# 10MHzRefOsc_3V0.net
KiCad netlist of a schematic drawn in EAGLE
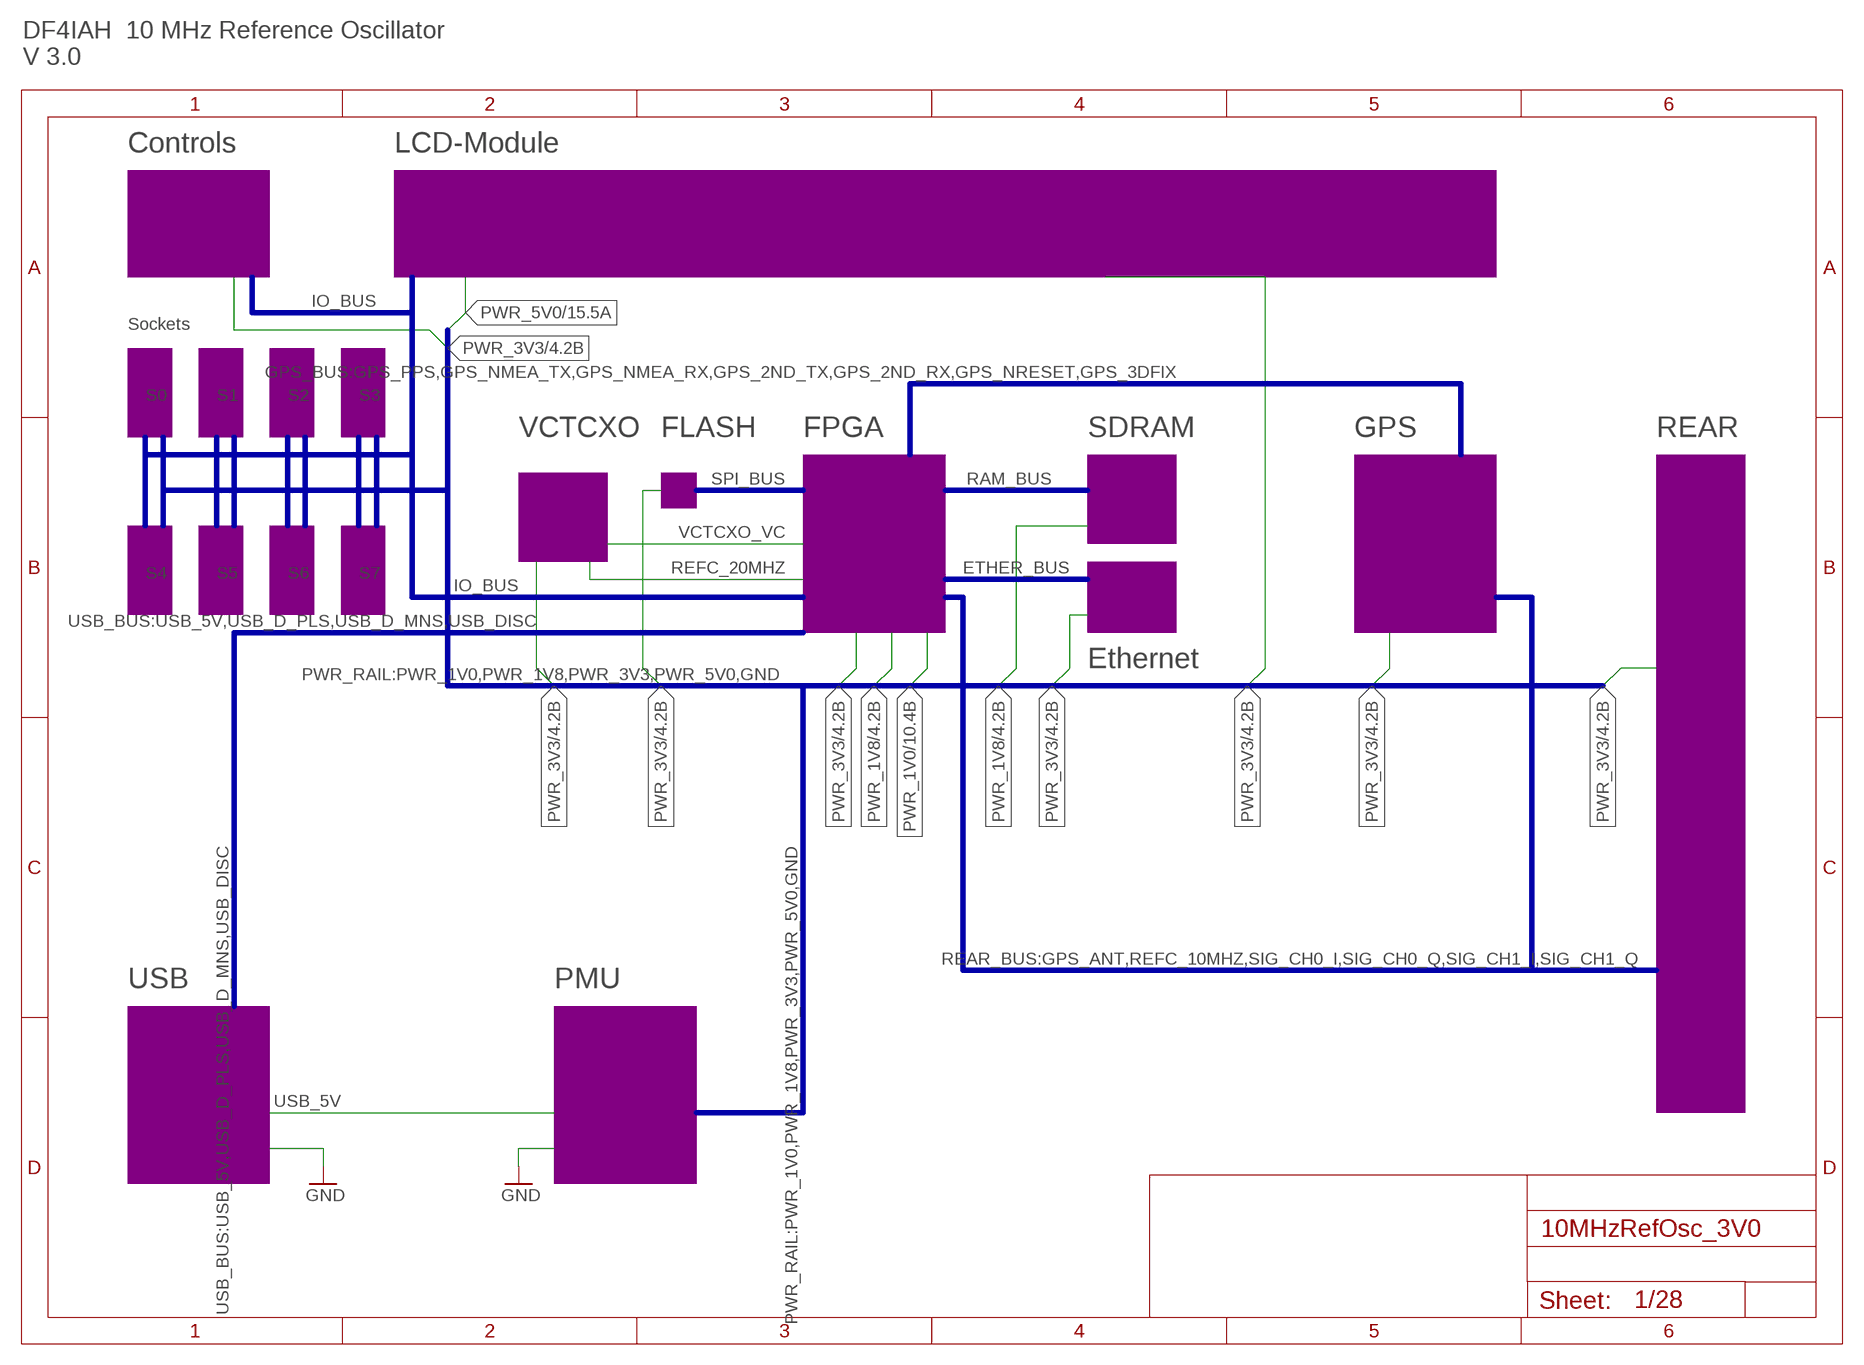
[diagram p0: schematic, sheet 1]
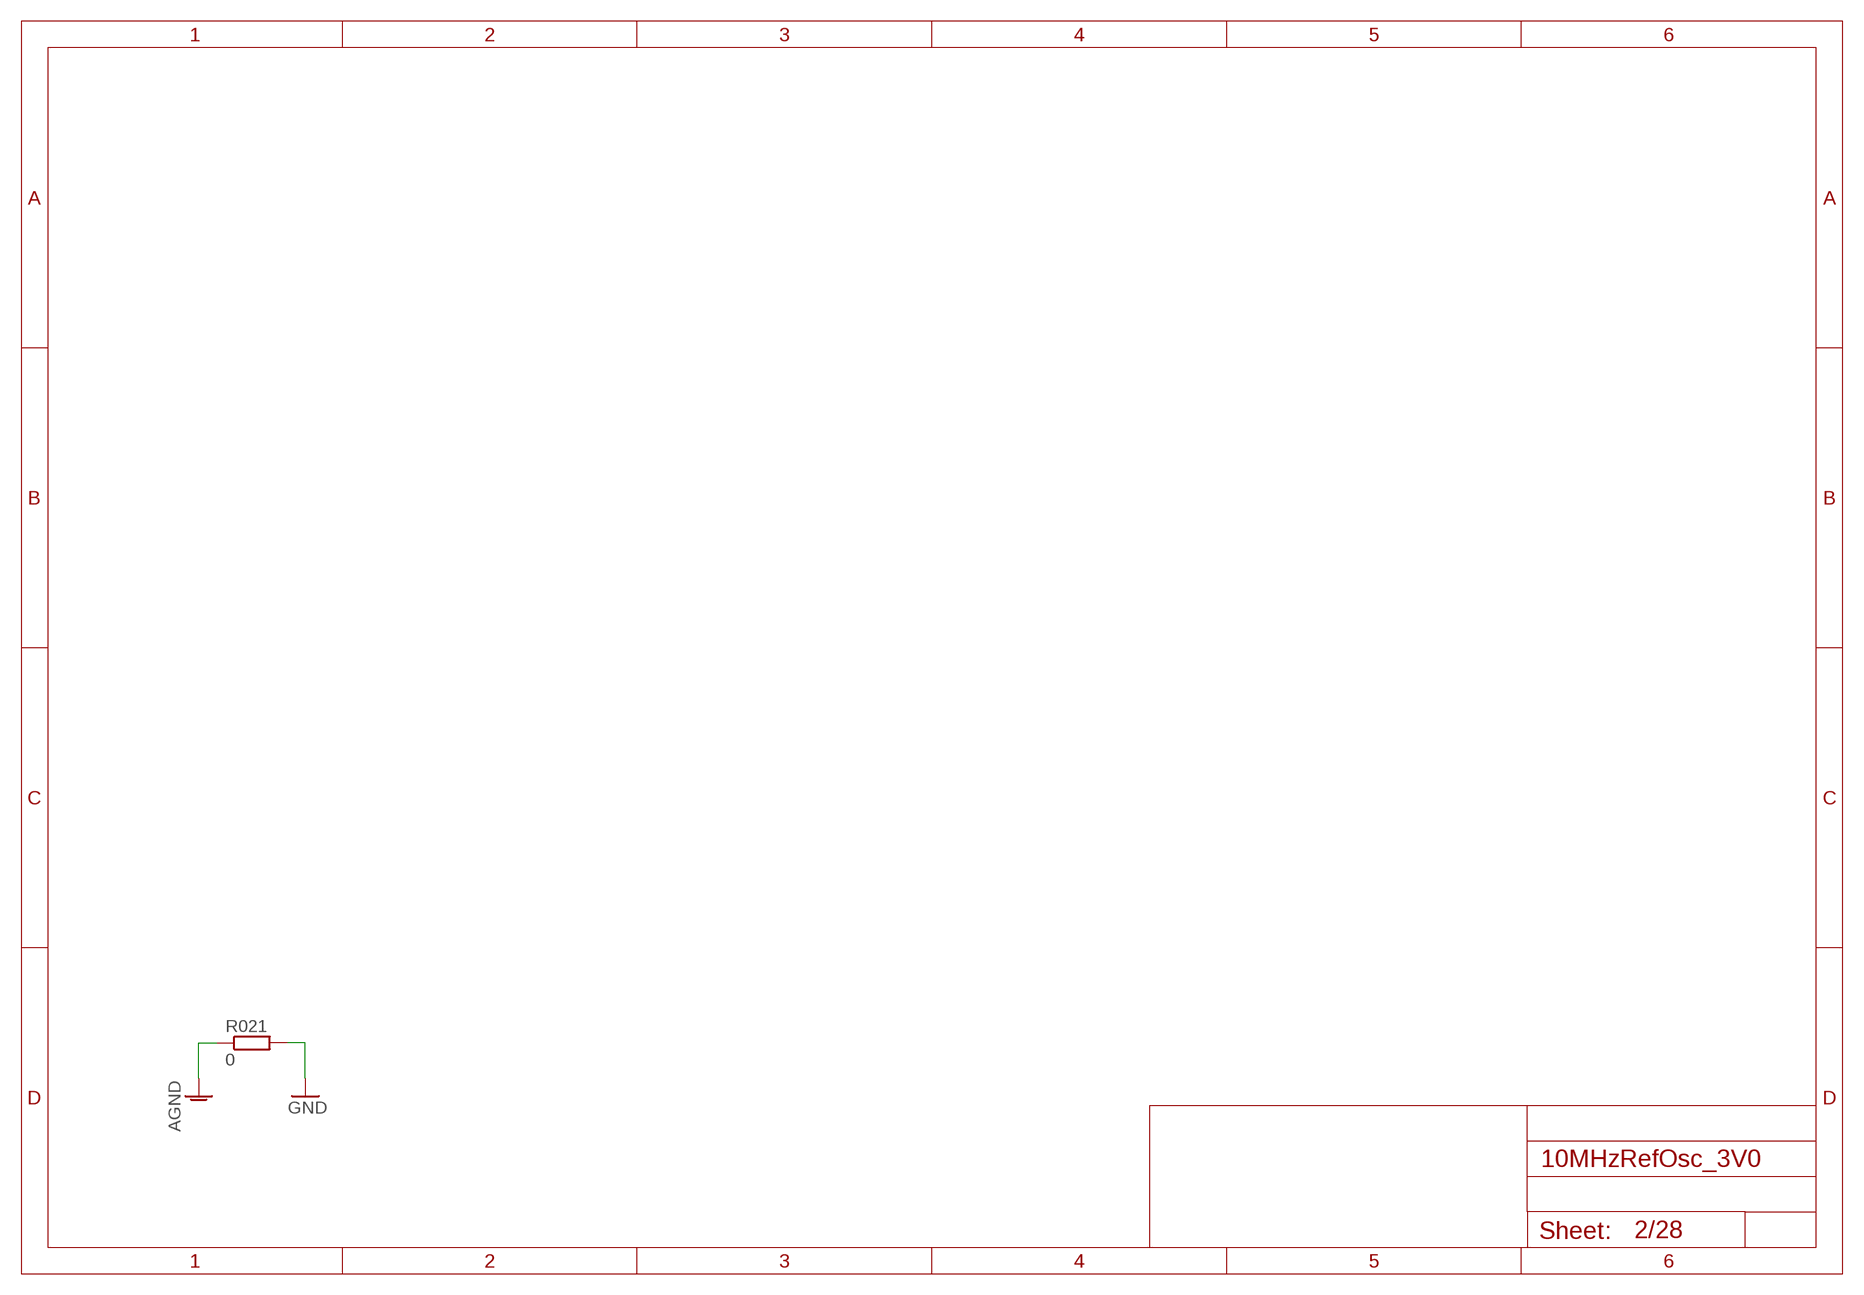
[diagram p1: schematic, sheet 2]
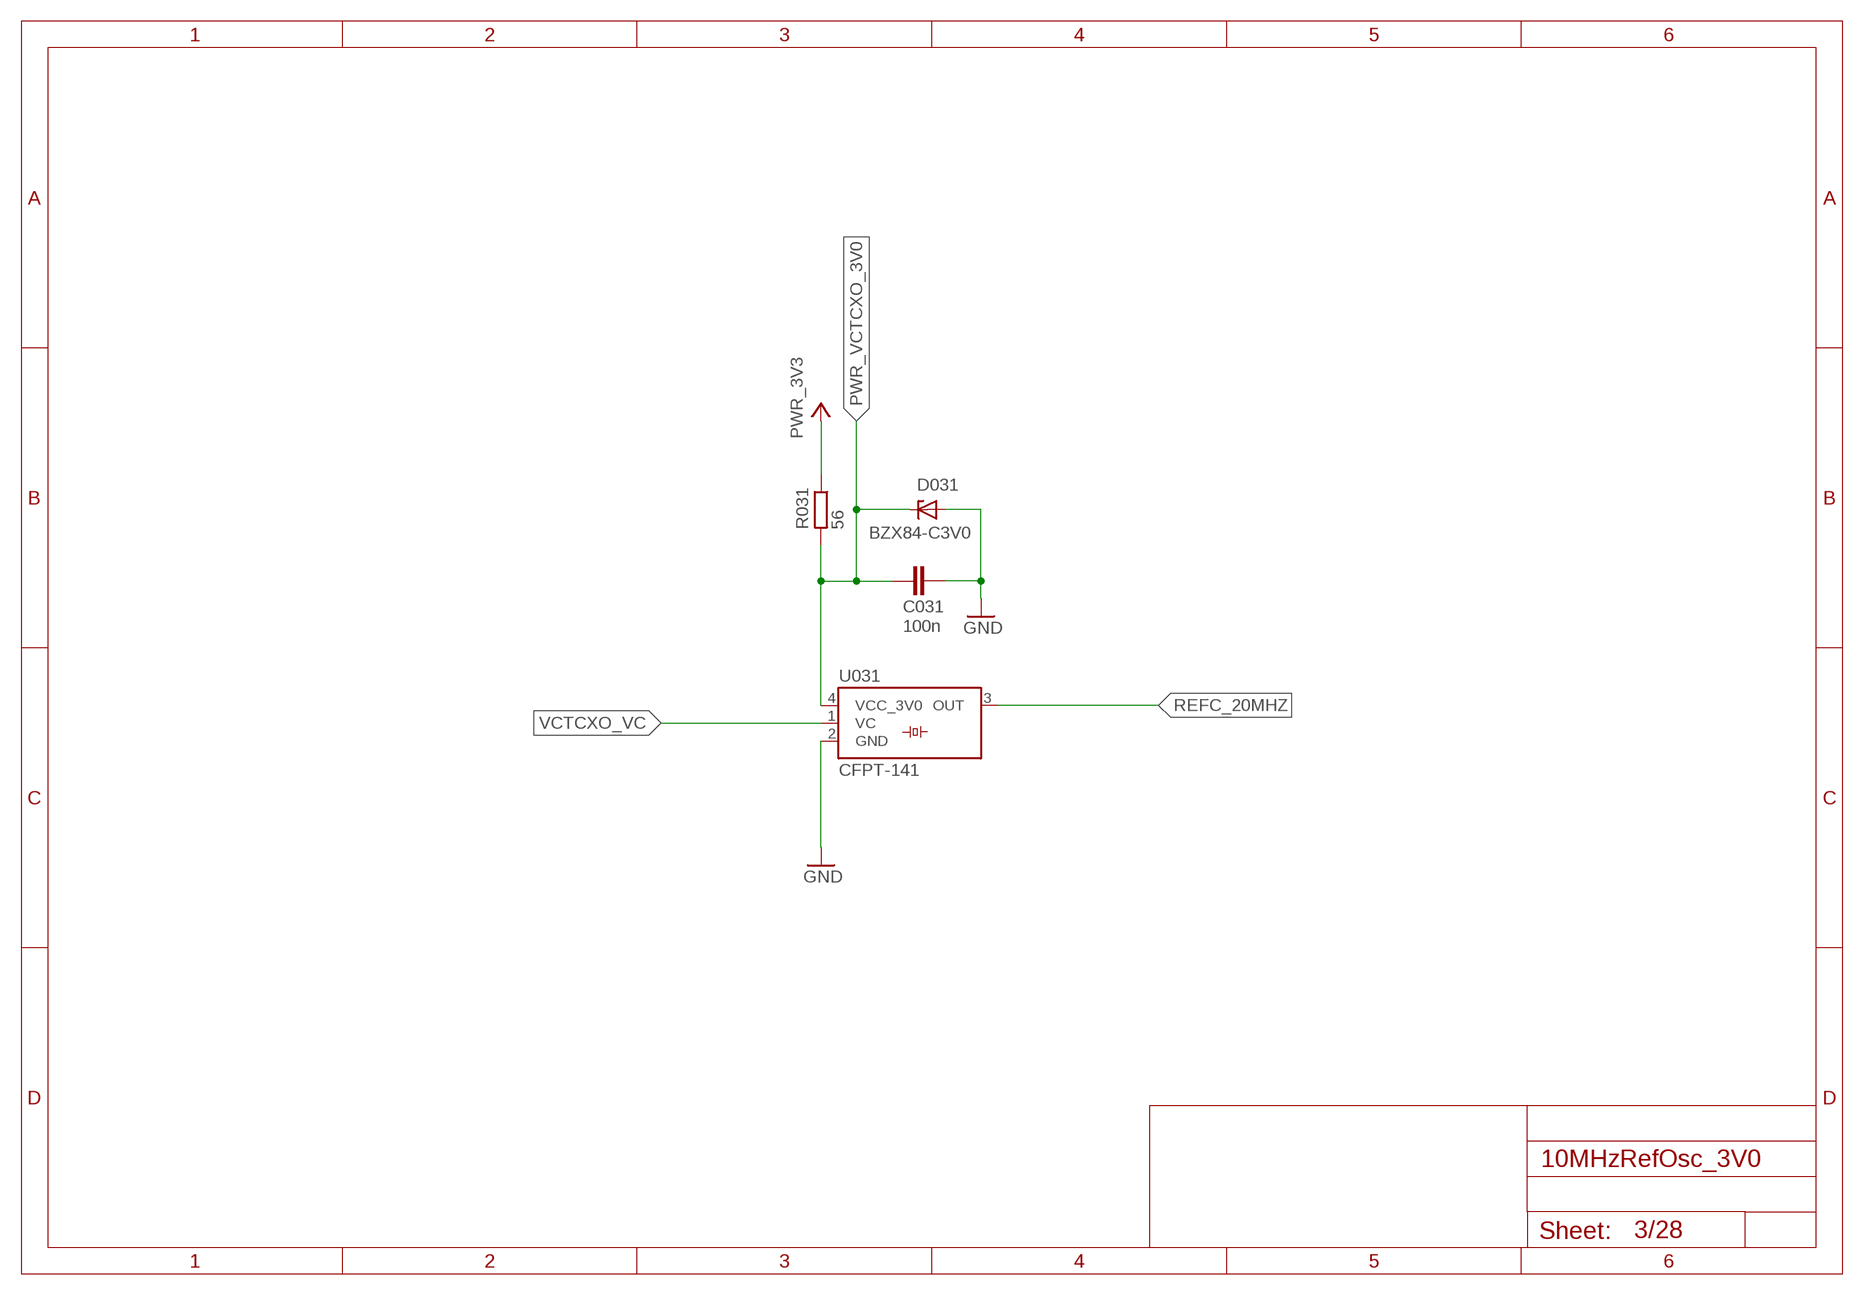
[diagram p2: schematic, sheet 3]
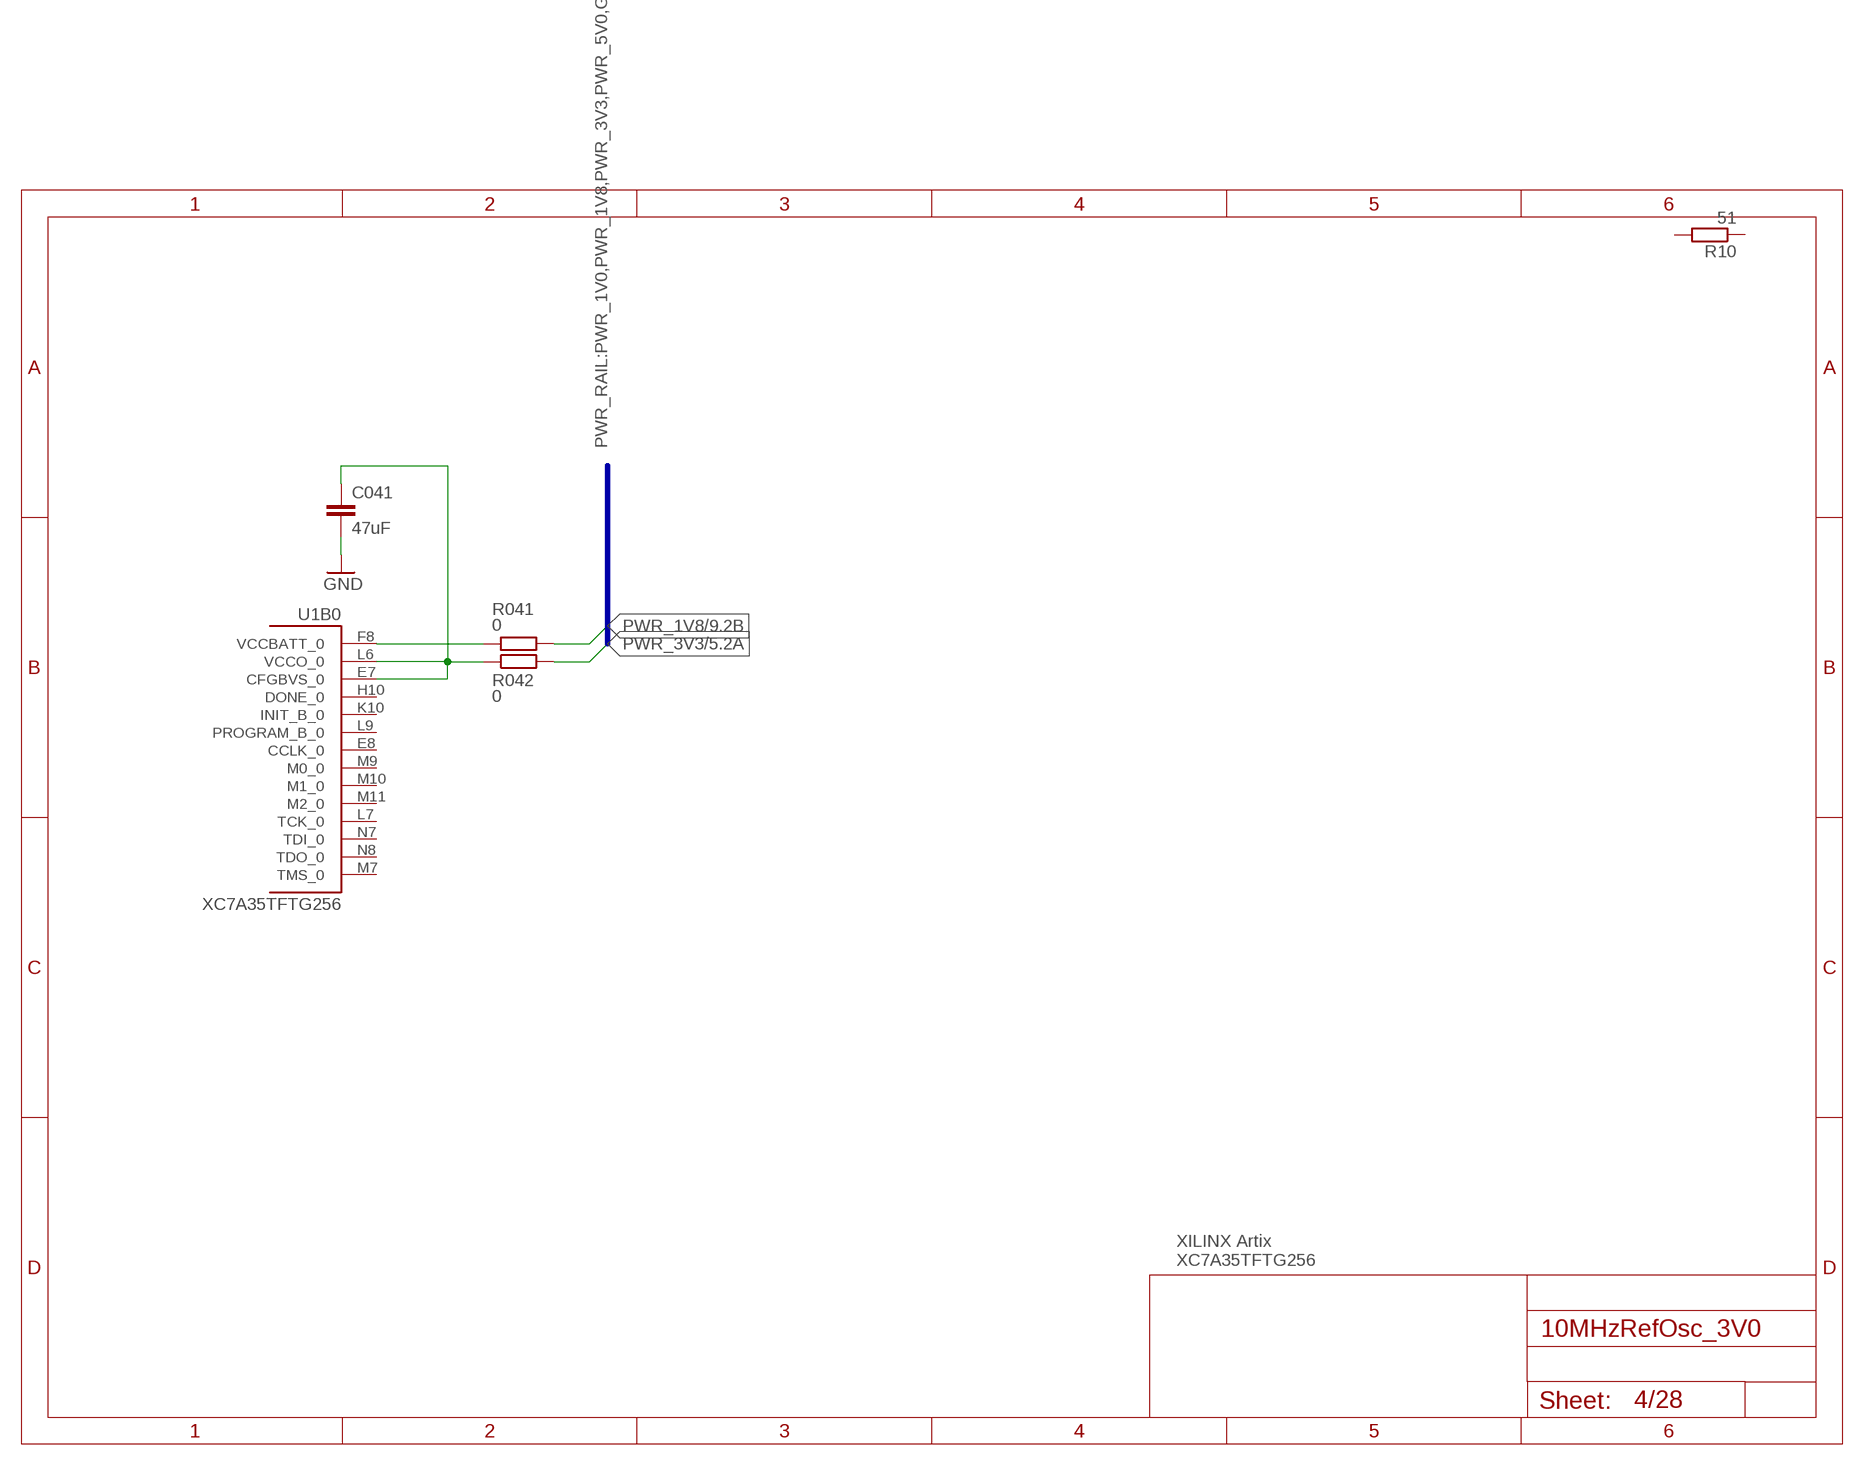
[diagram p3: schematic, sheet 4]
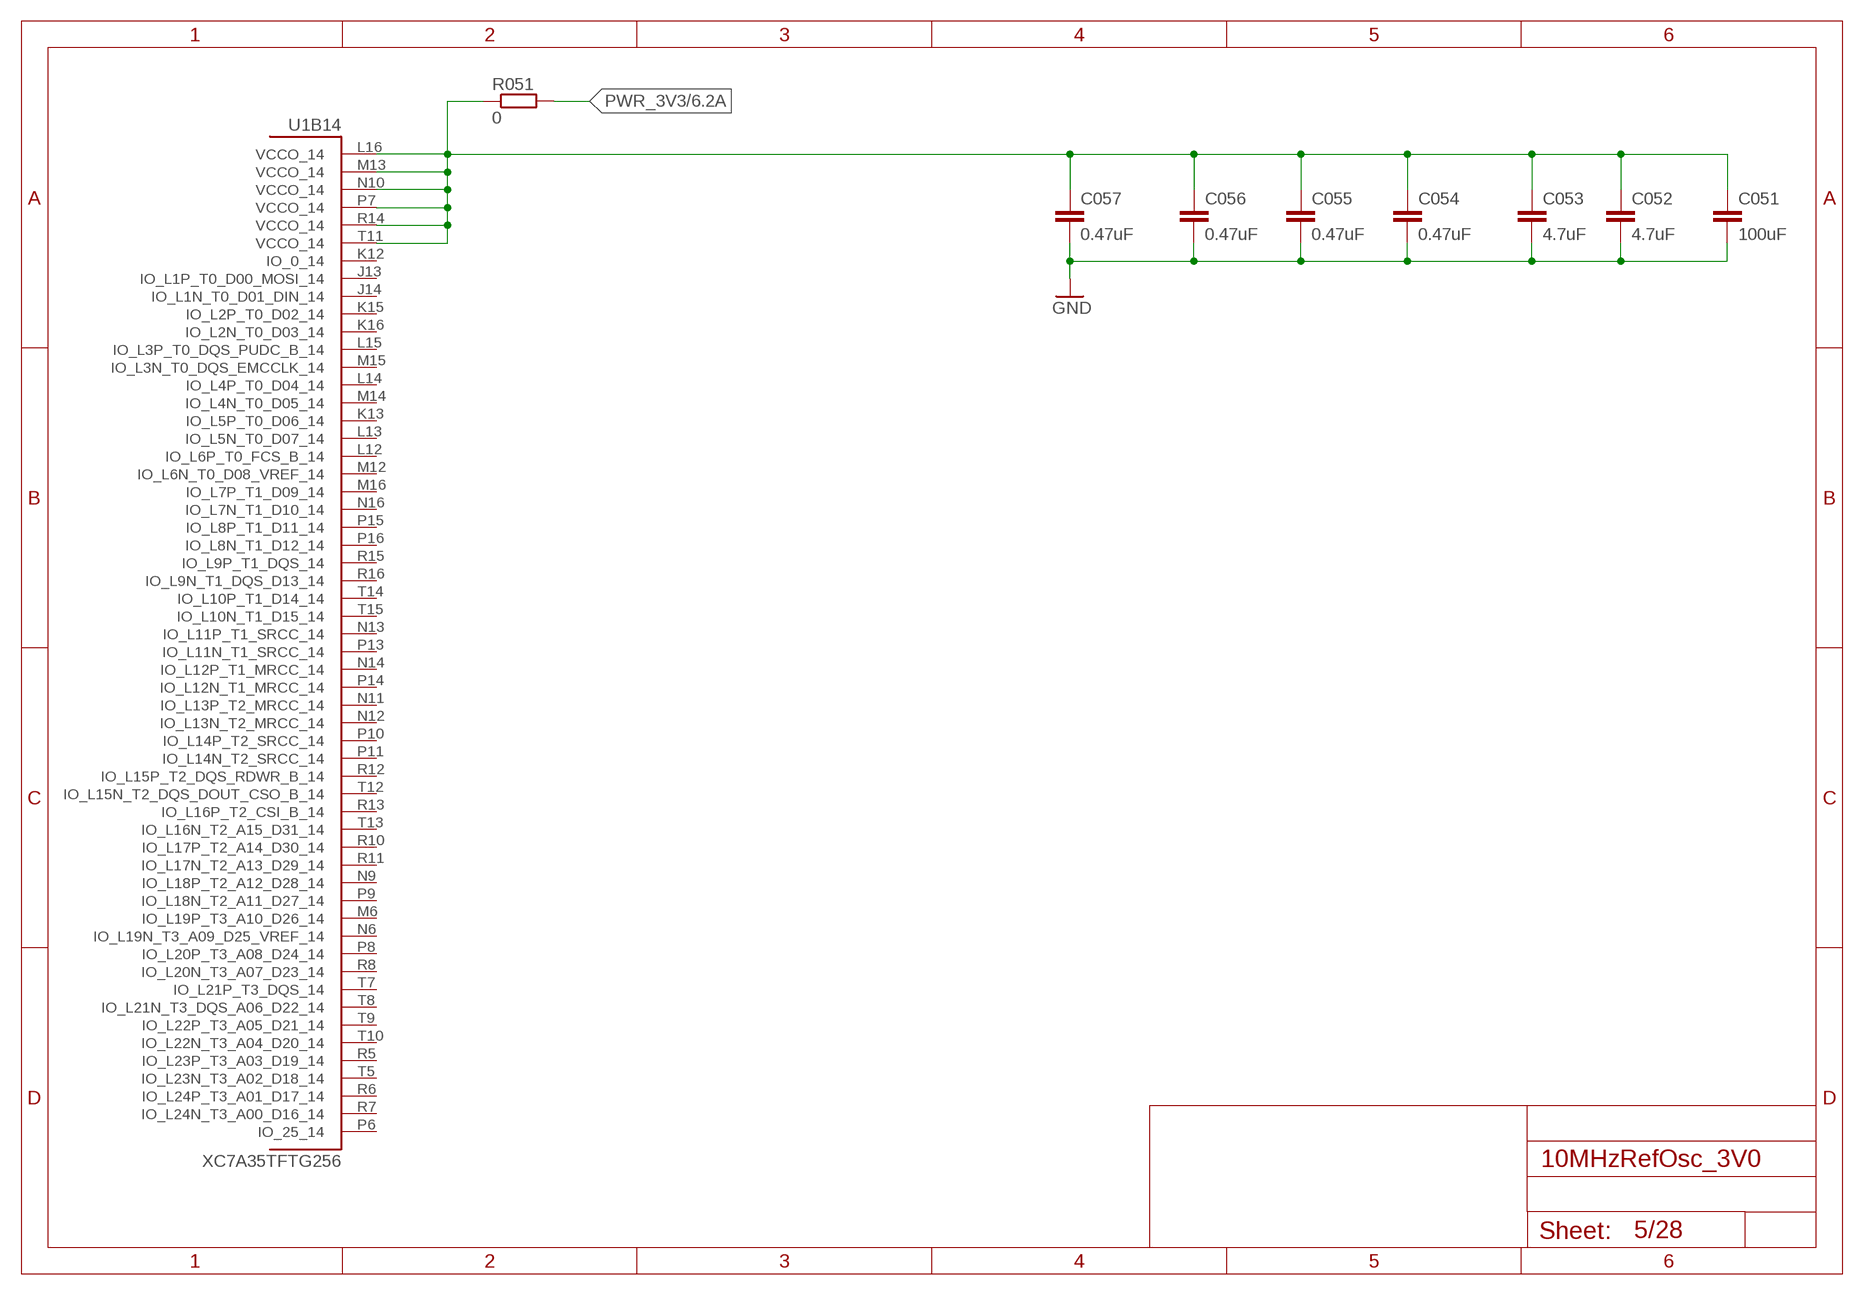
[diagram p4: schematic, sheet 5]
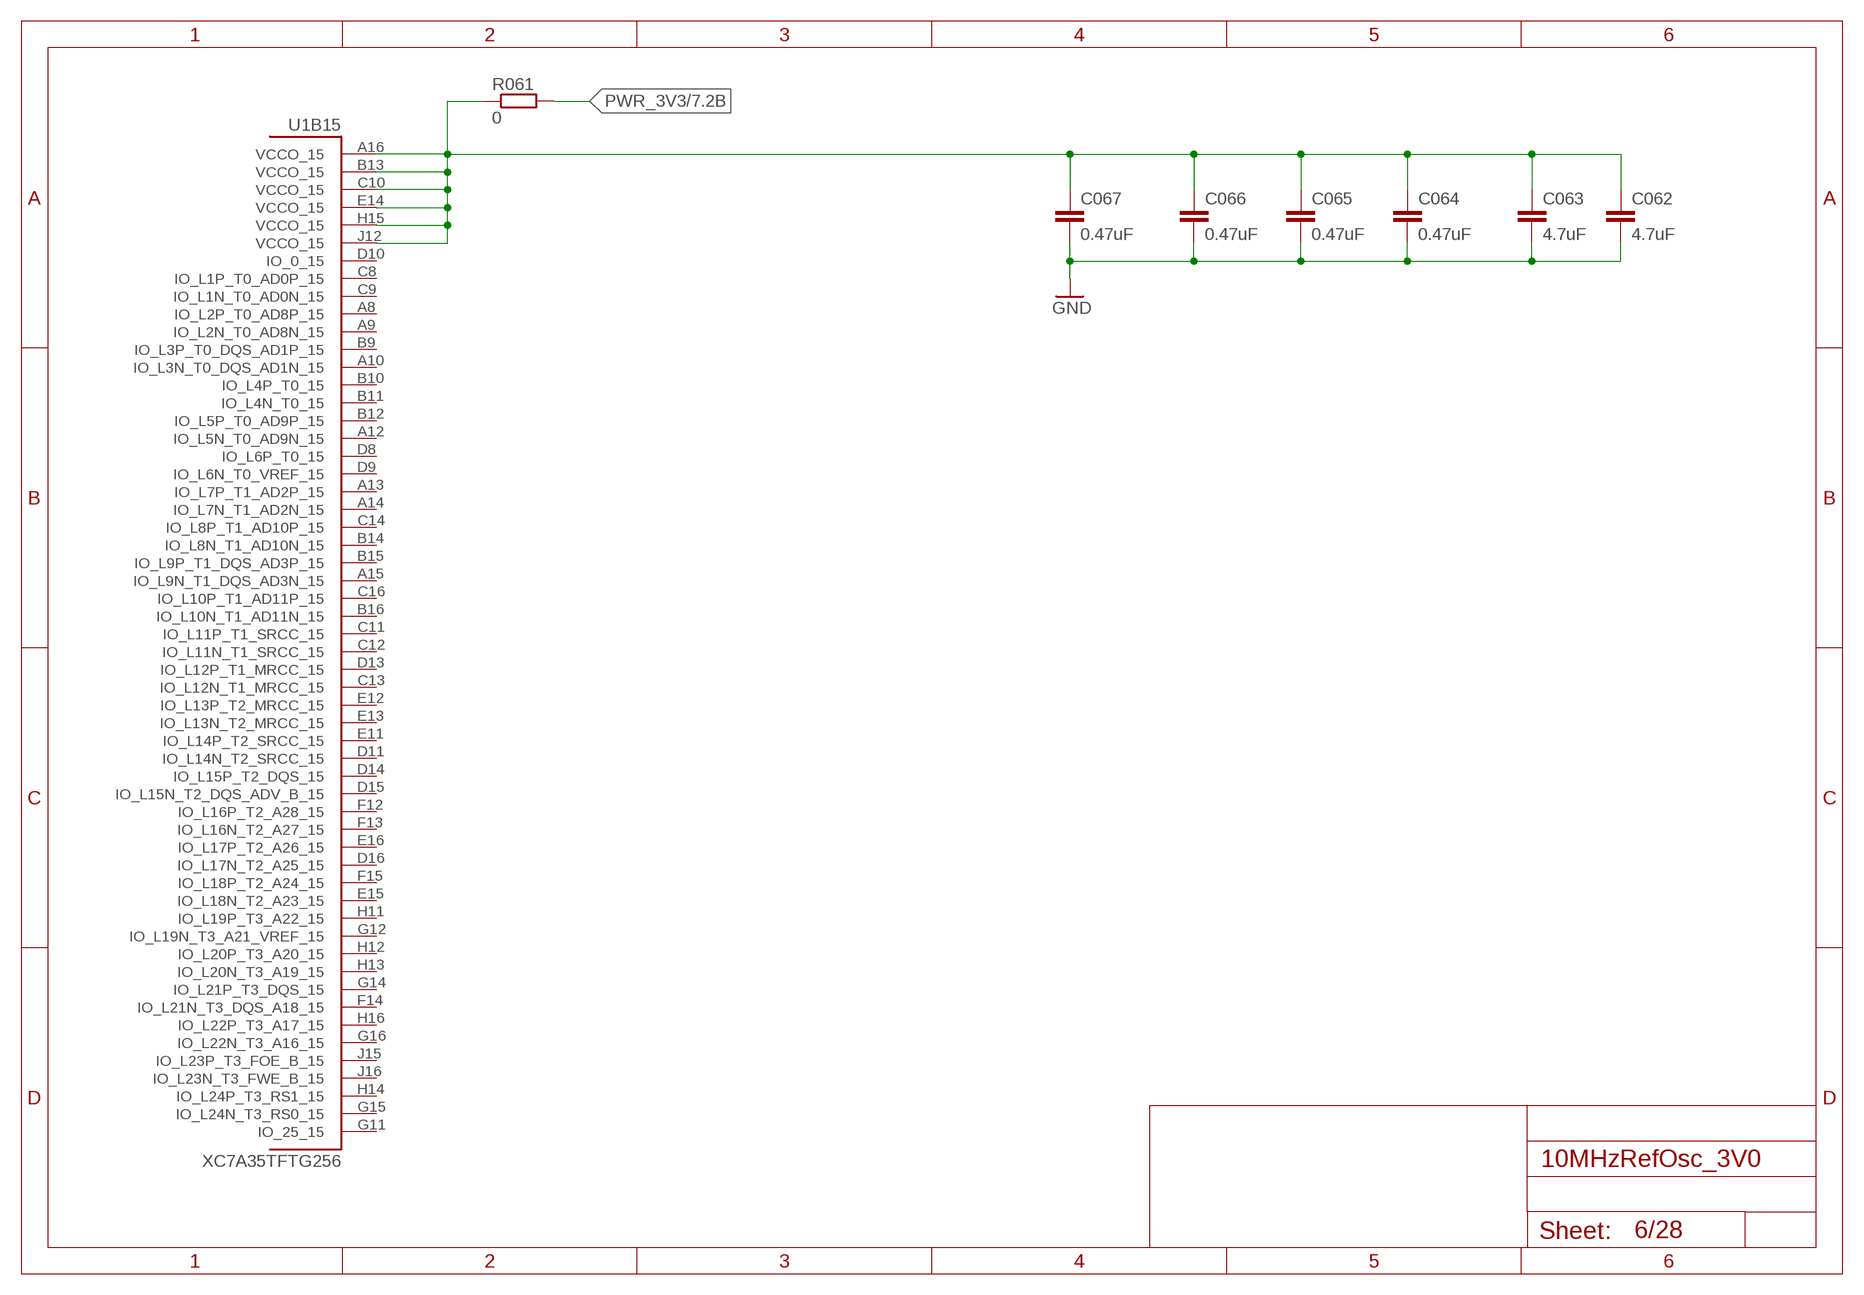
[diagram p5: schematic, sheet 6]
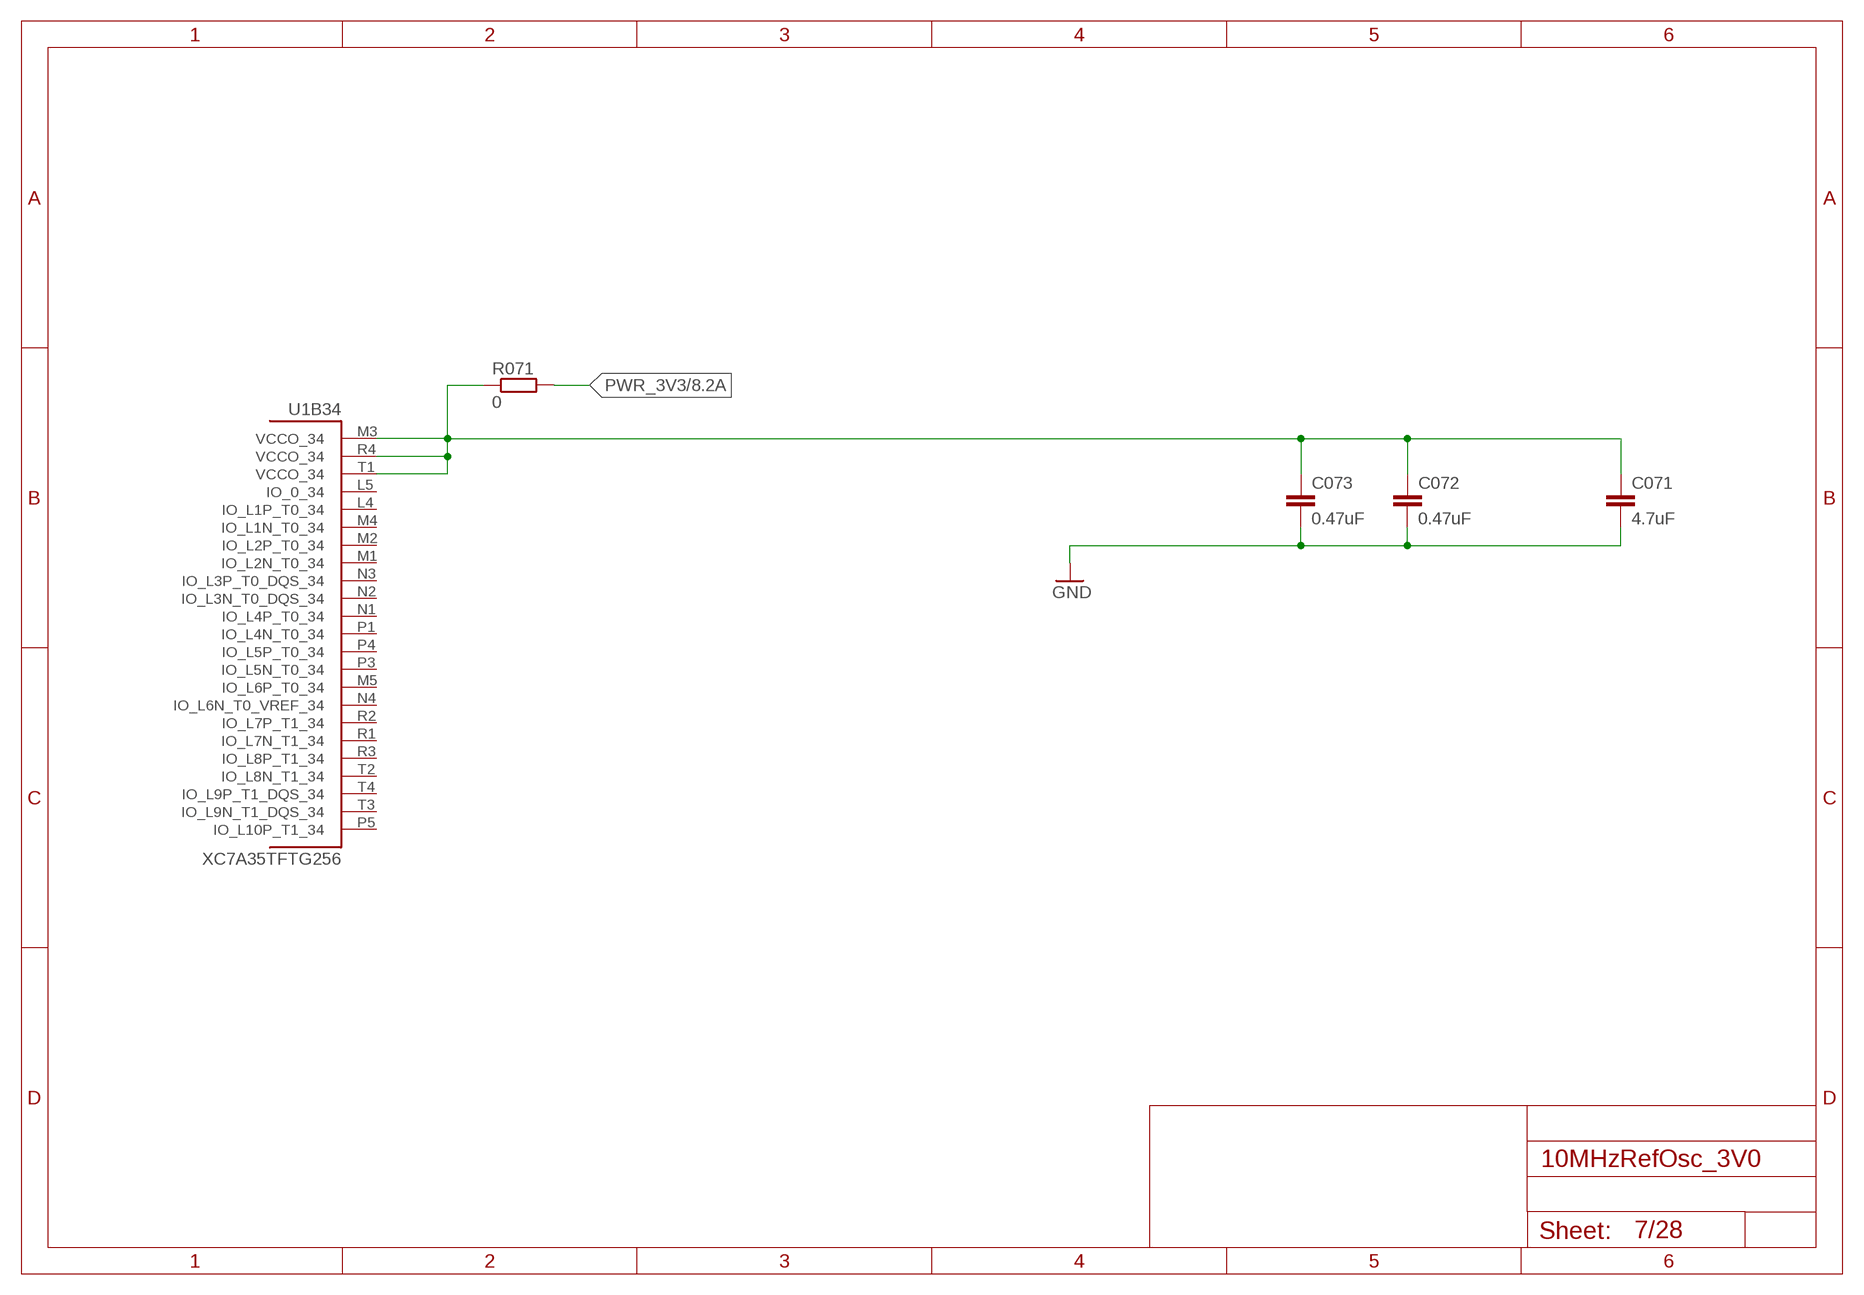
[diagram p6: schematic, sheet 7]
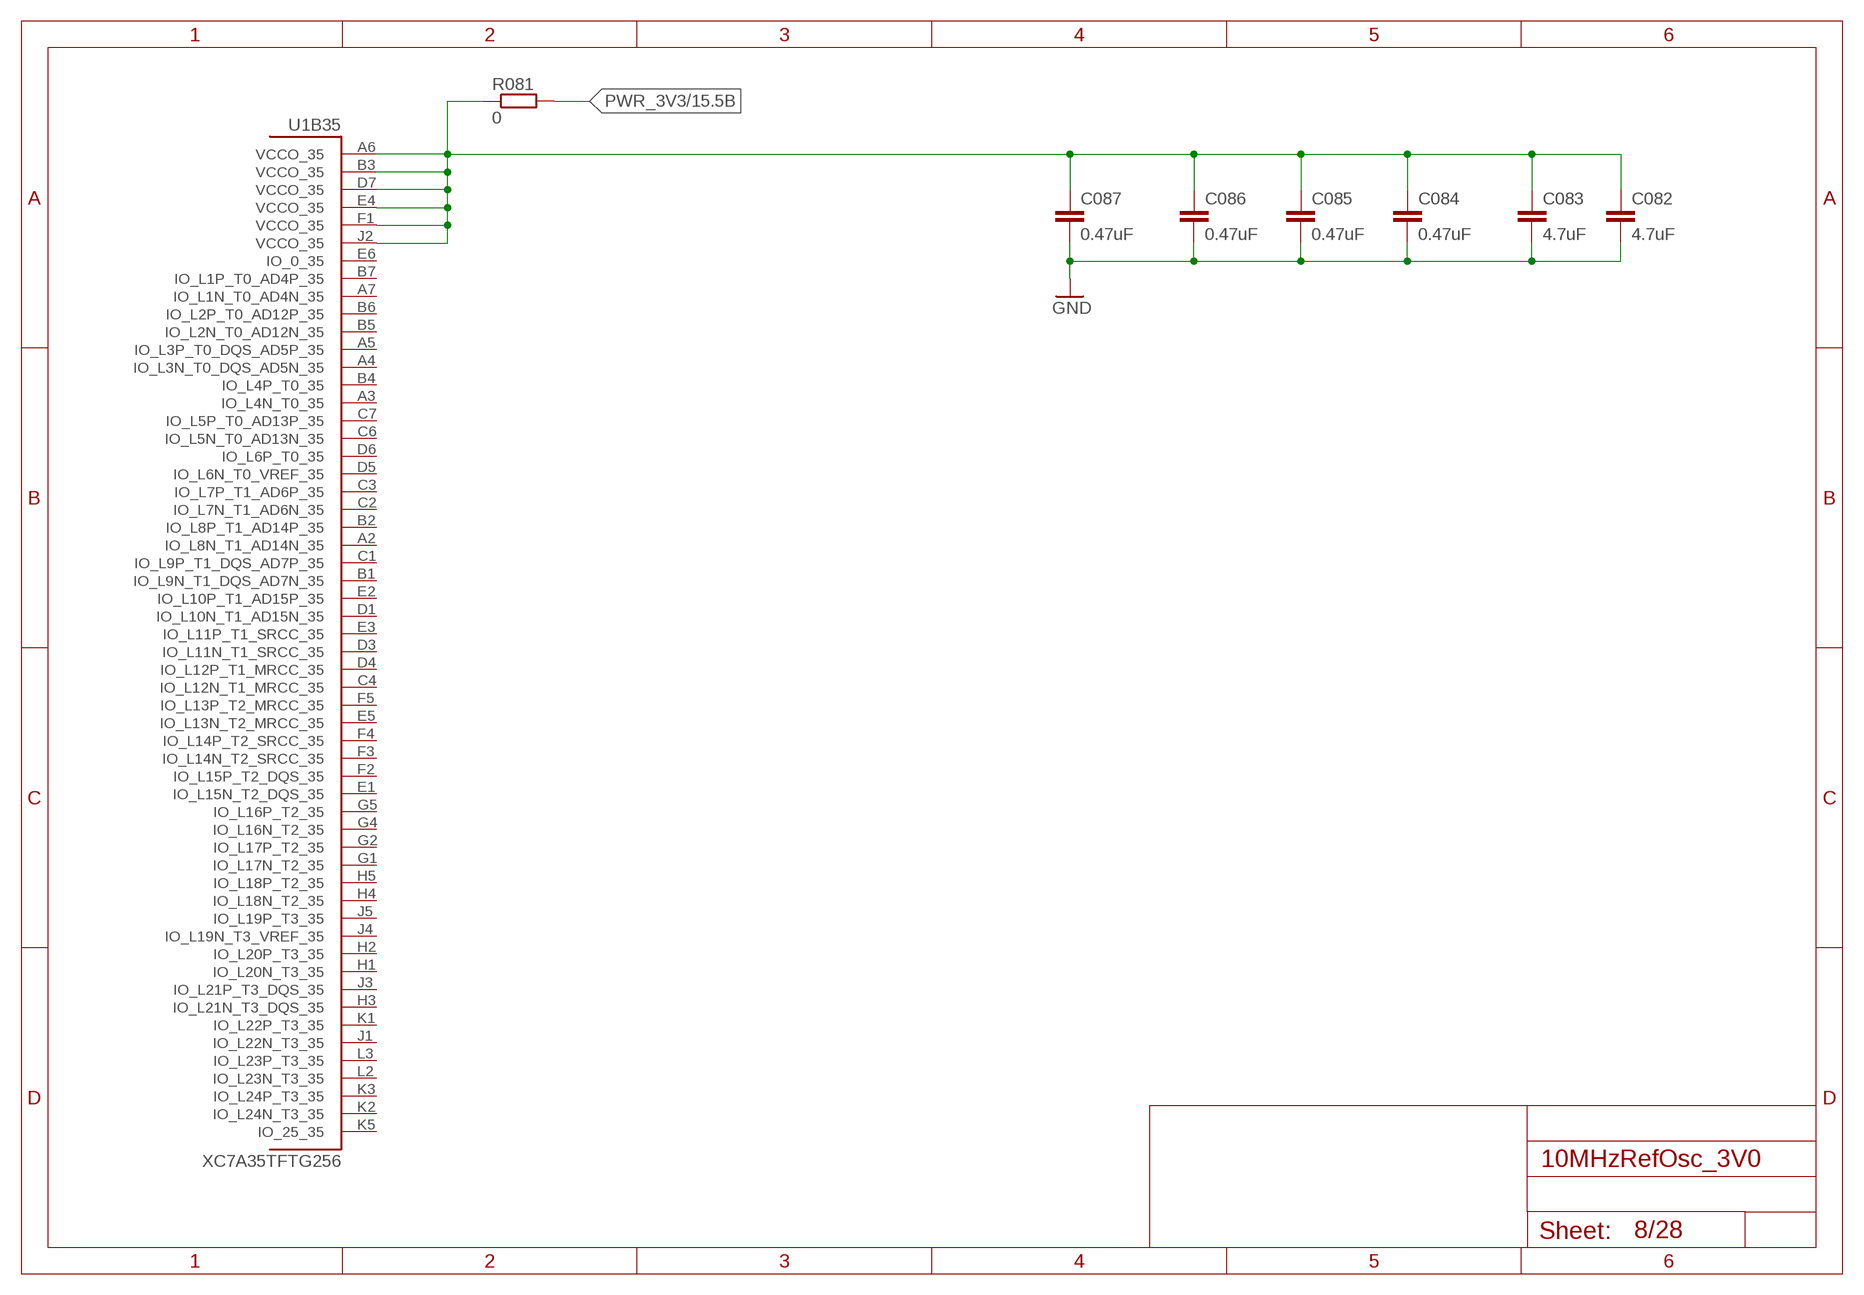
[diagram p7: schematic, sheet 8]
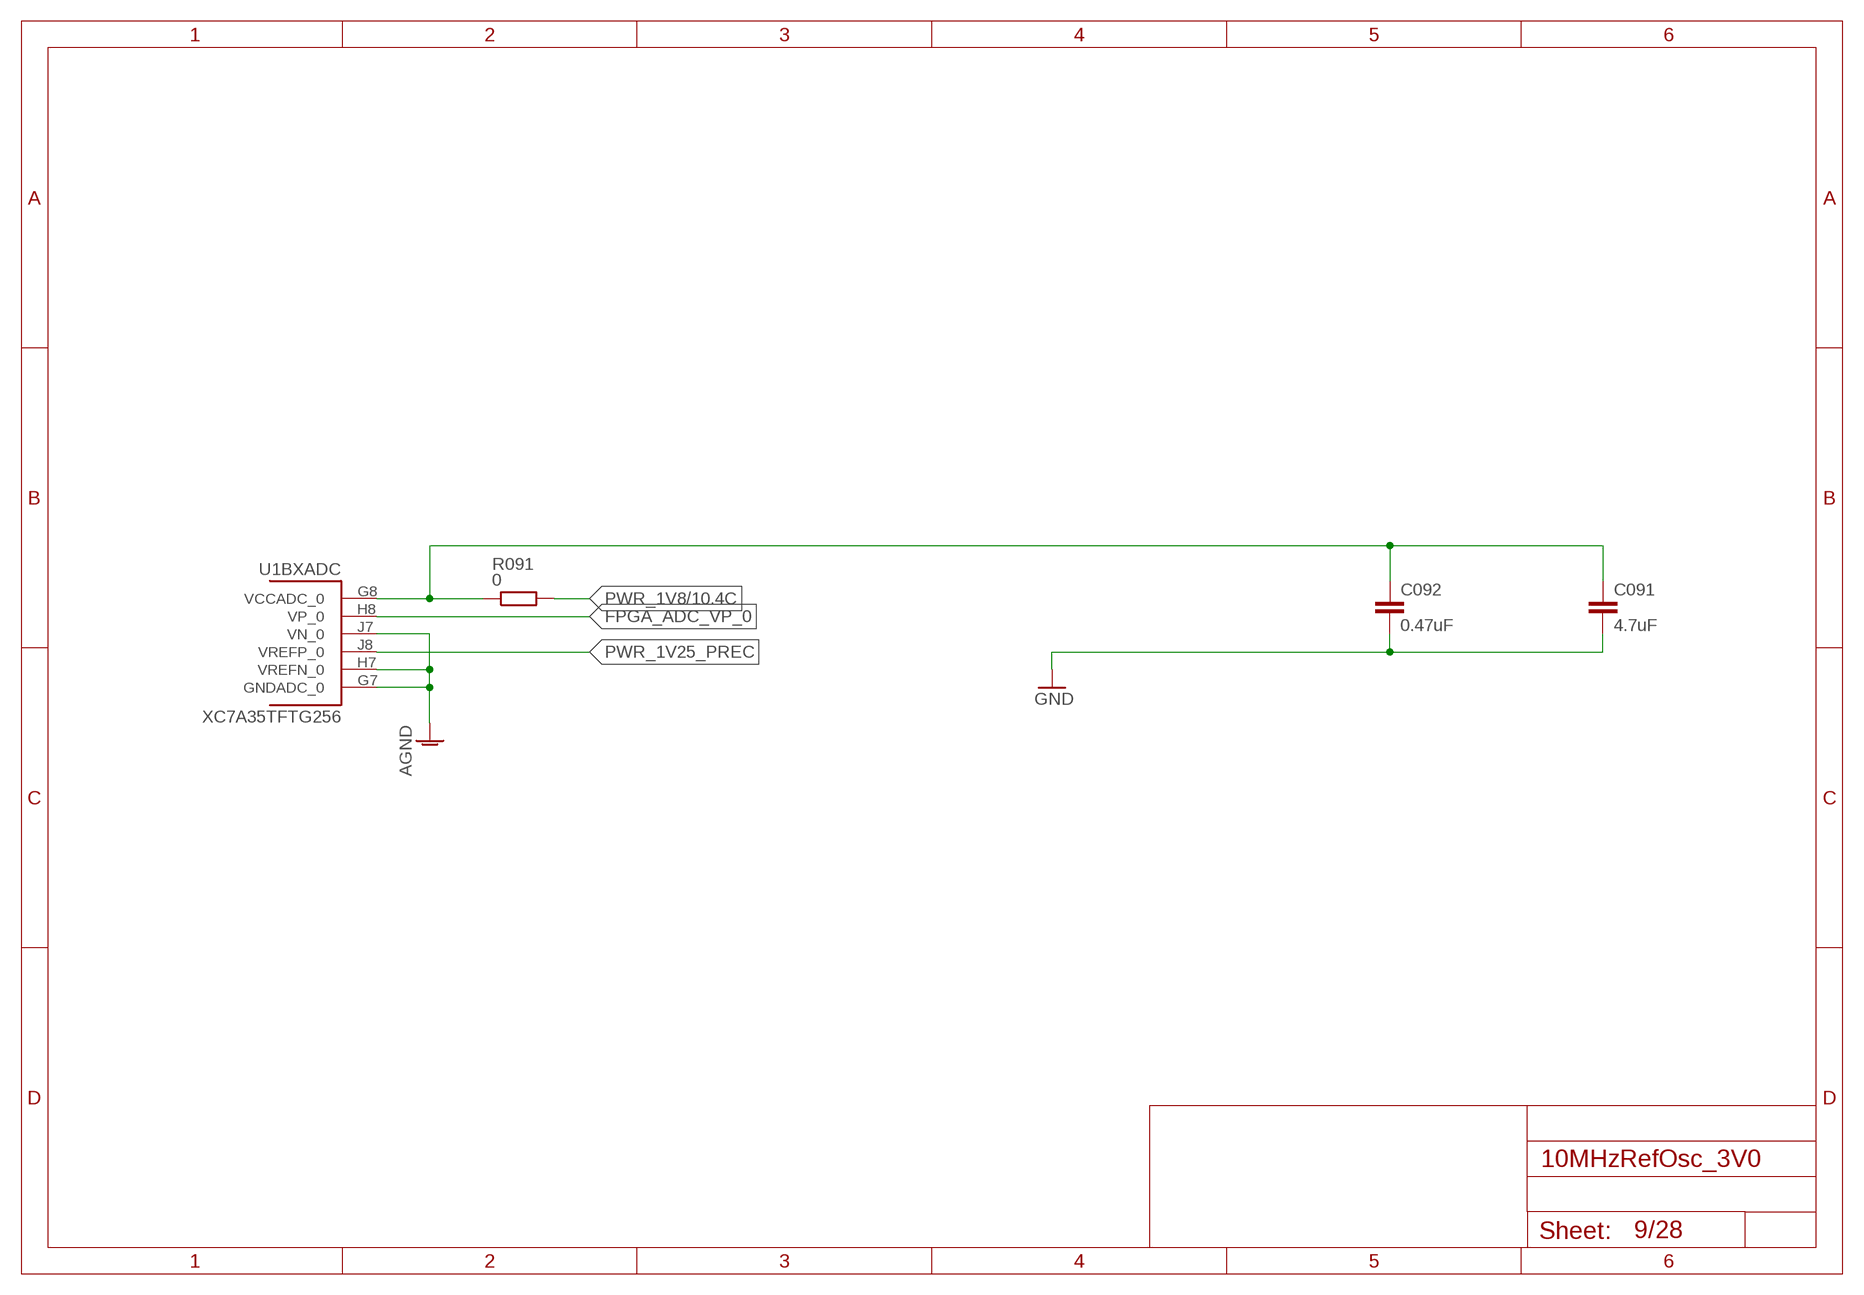
[diagram p8: schematic, sheet 9]
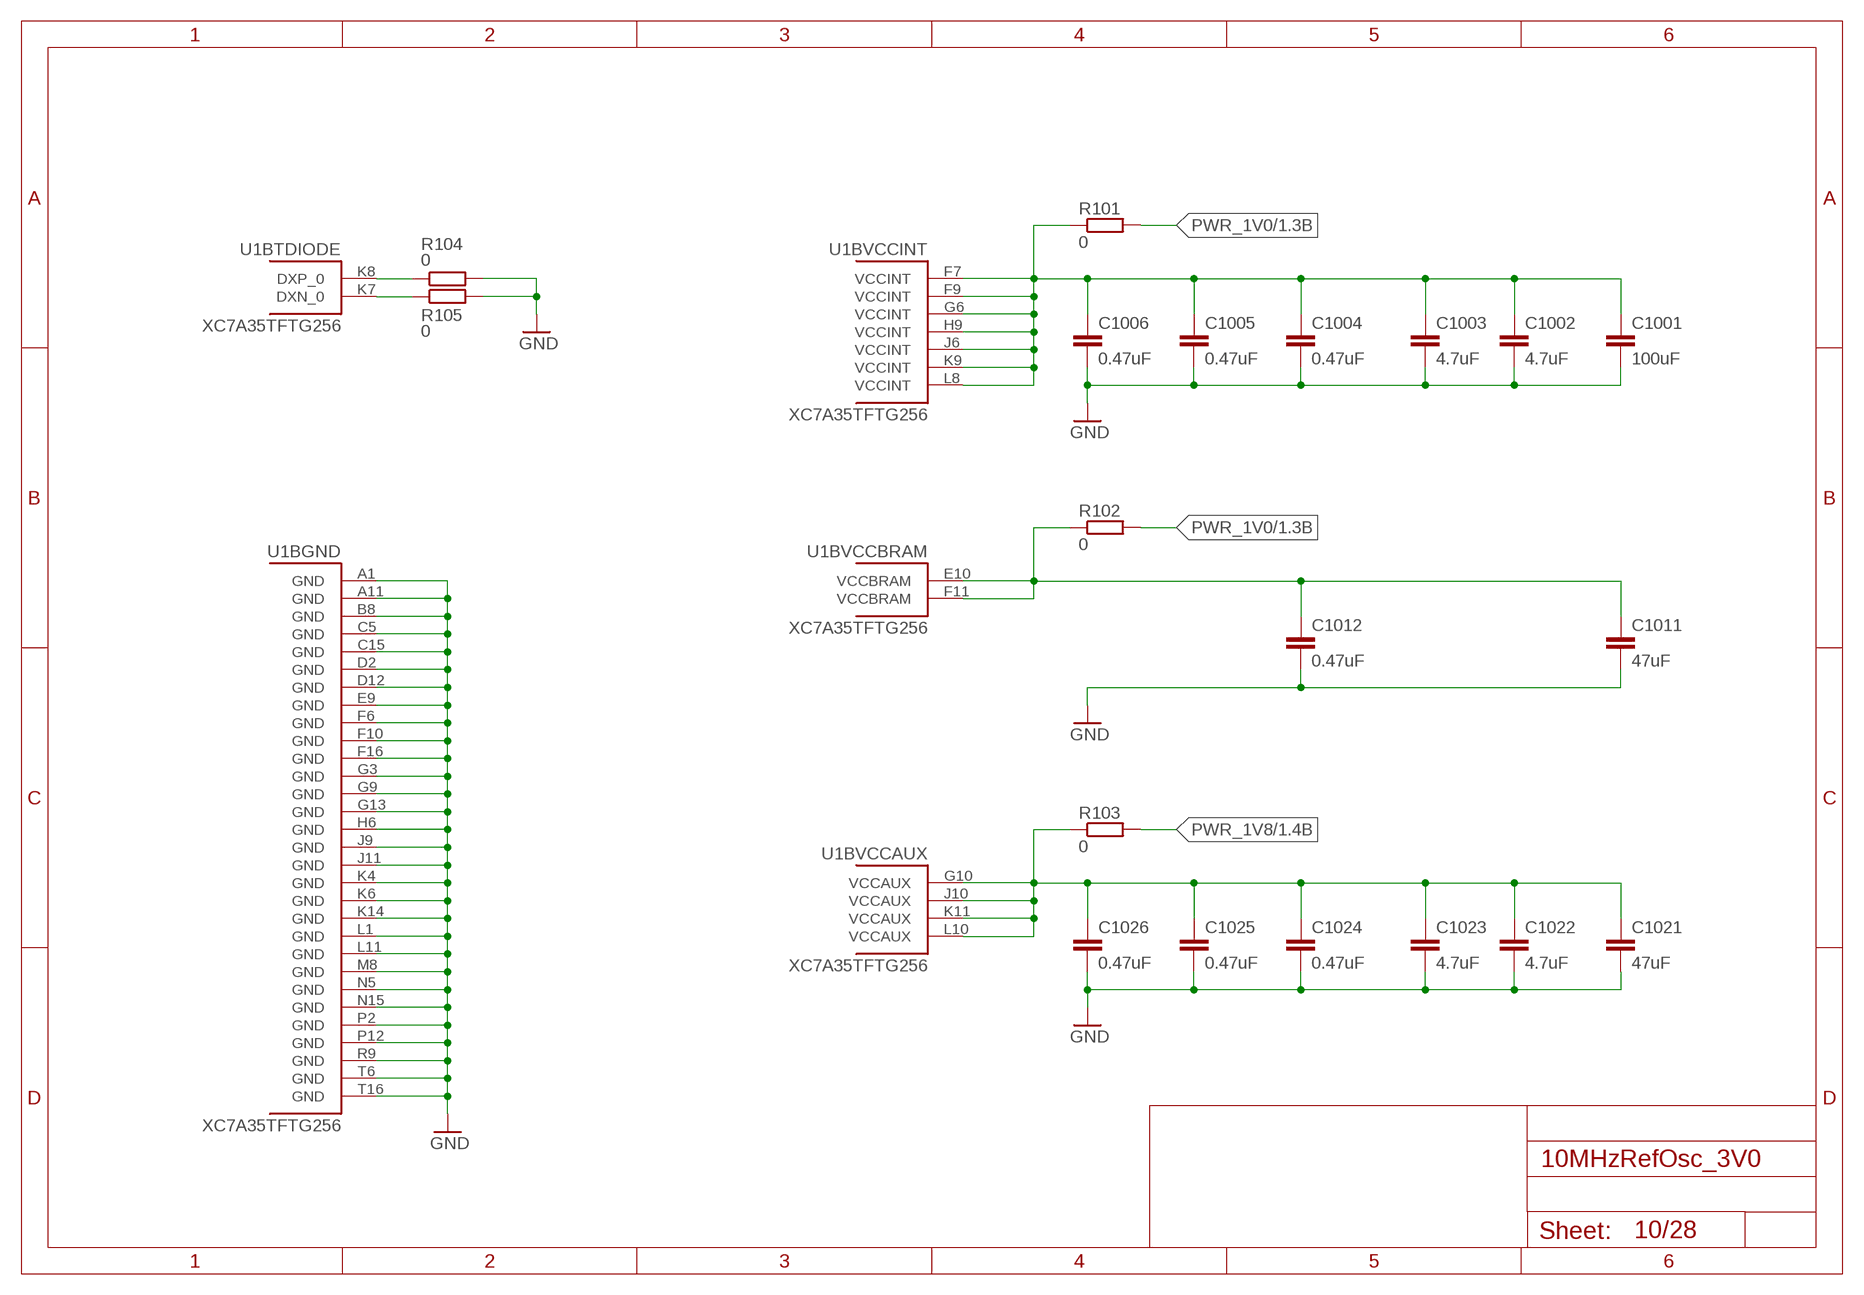
[diagram p9: schematic, sheet 10]
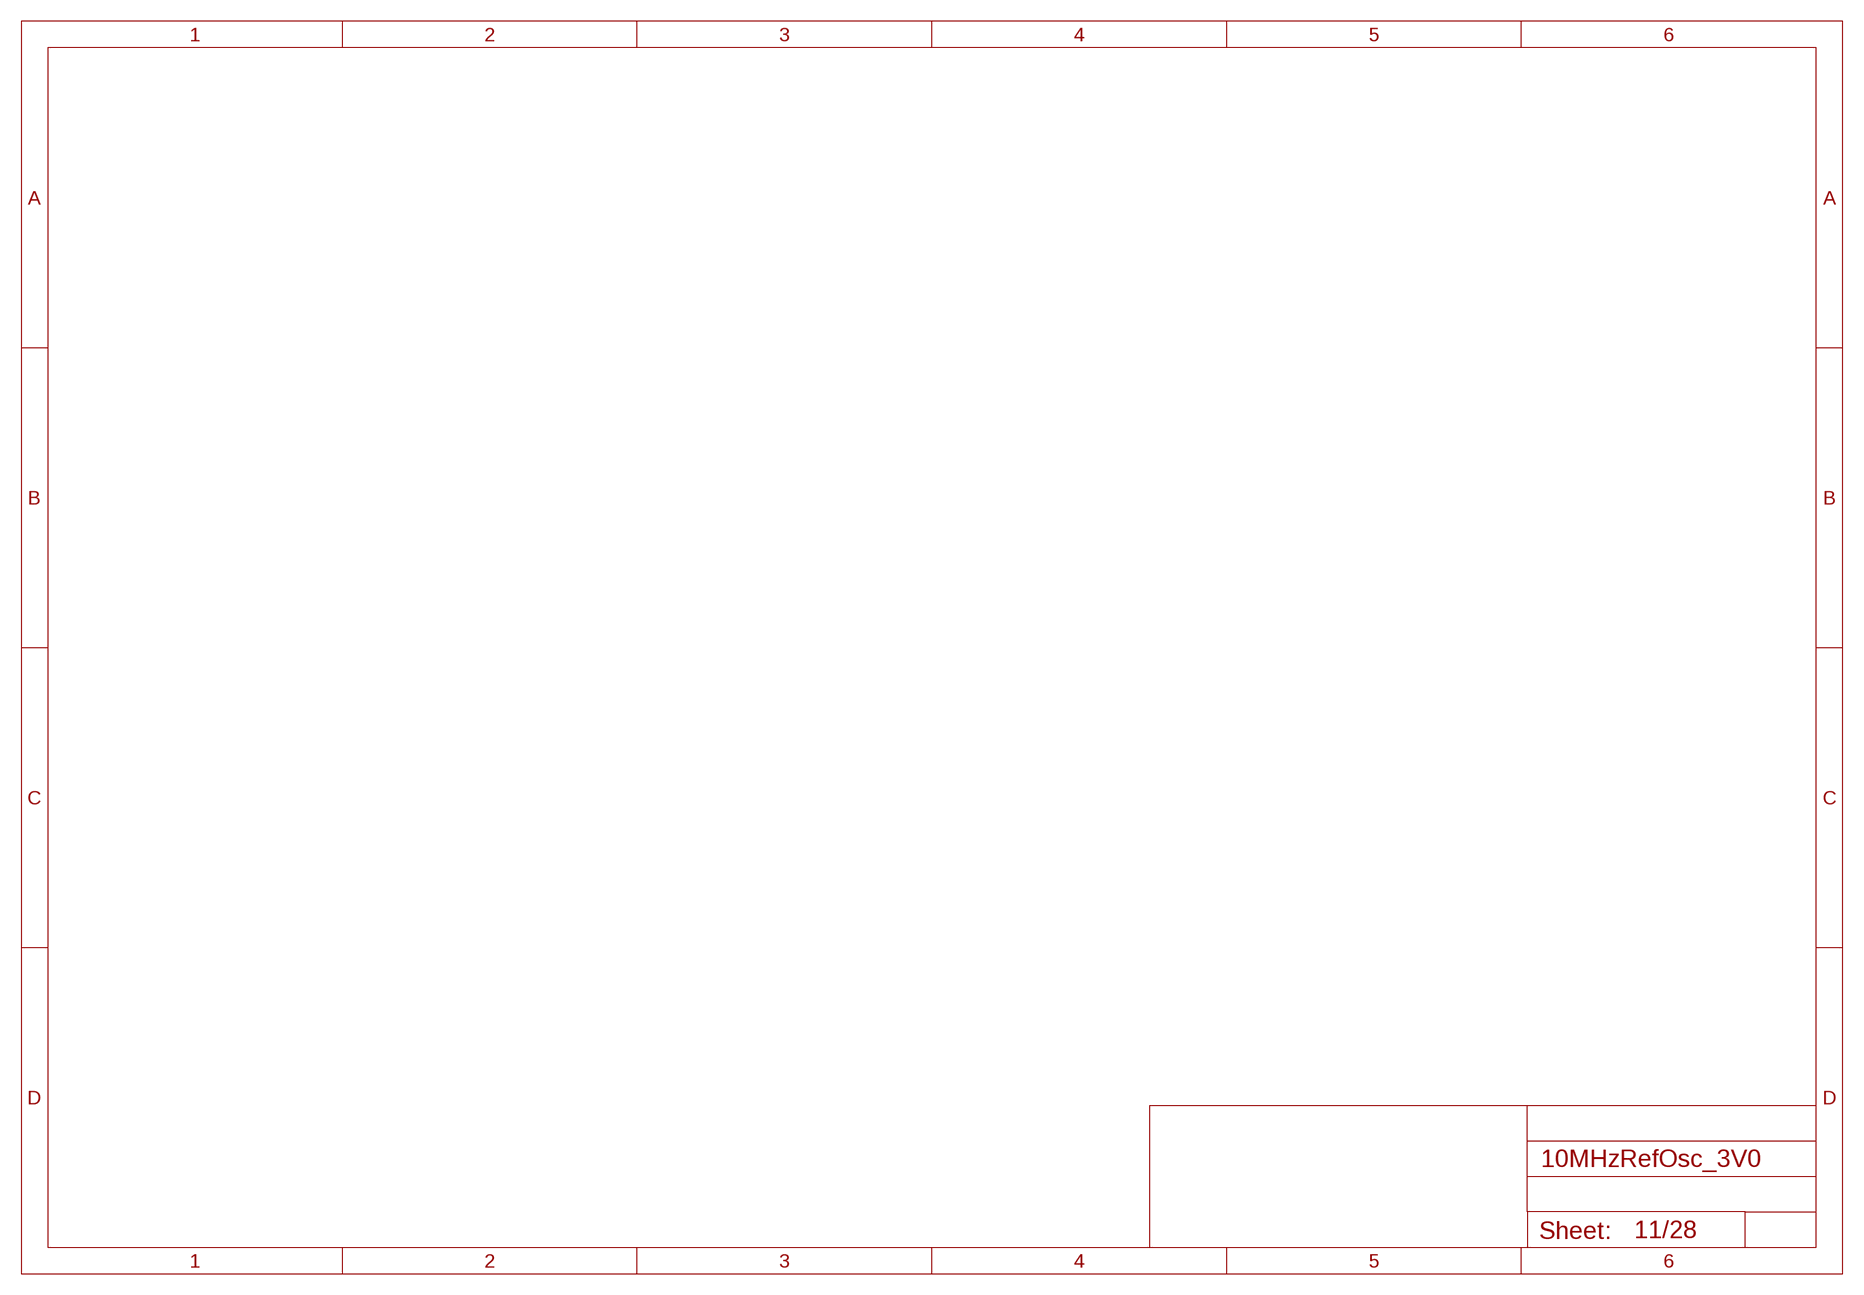
[diagram p10: schematic, sheet 11]
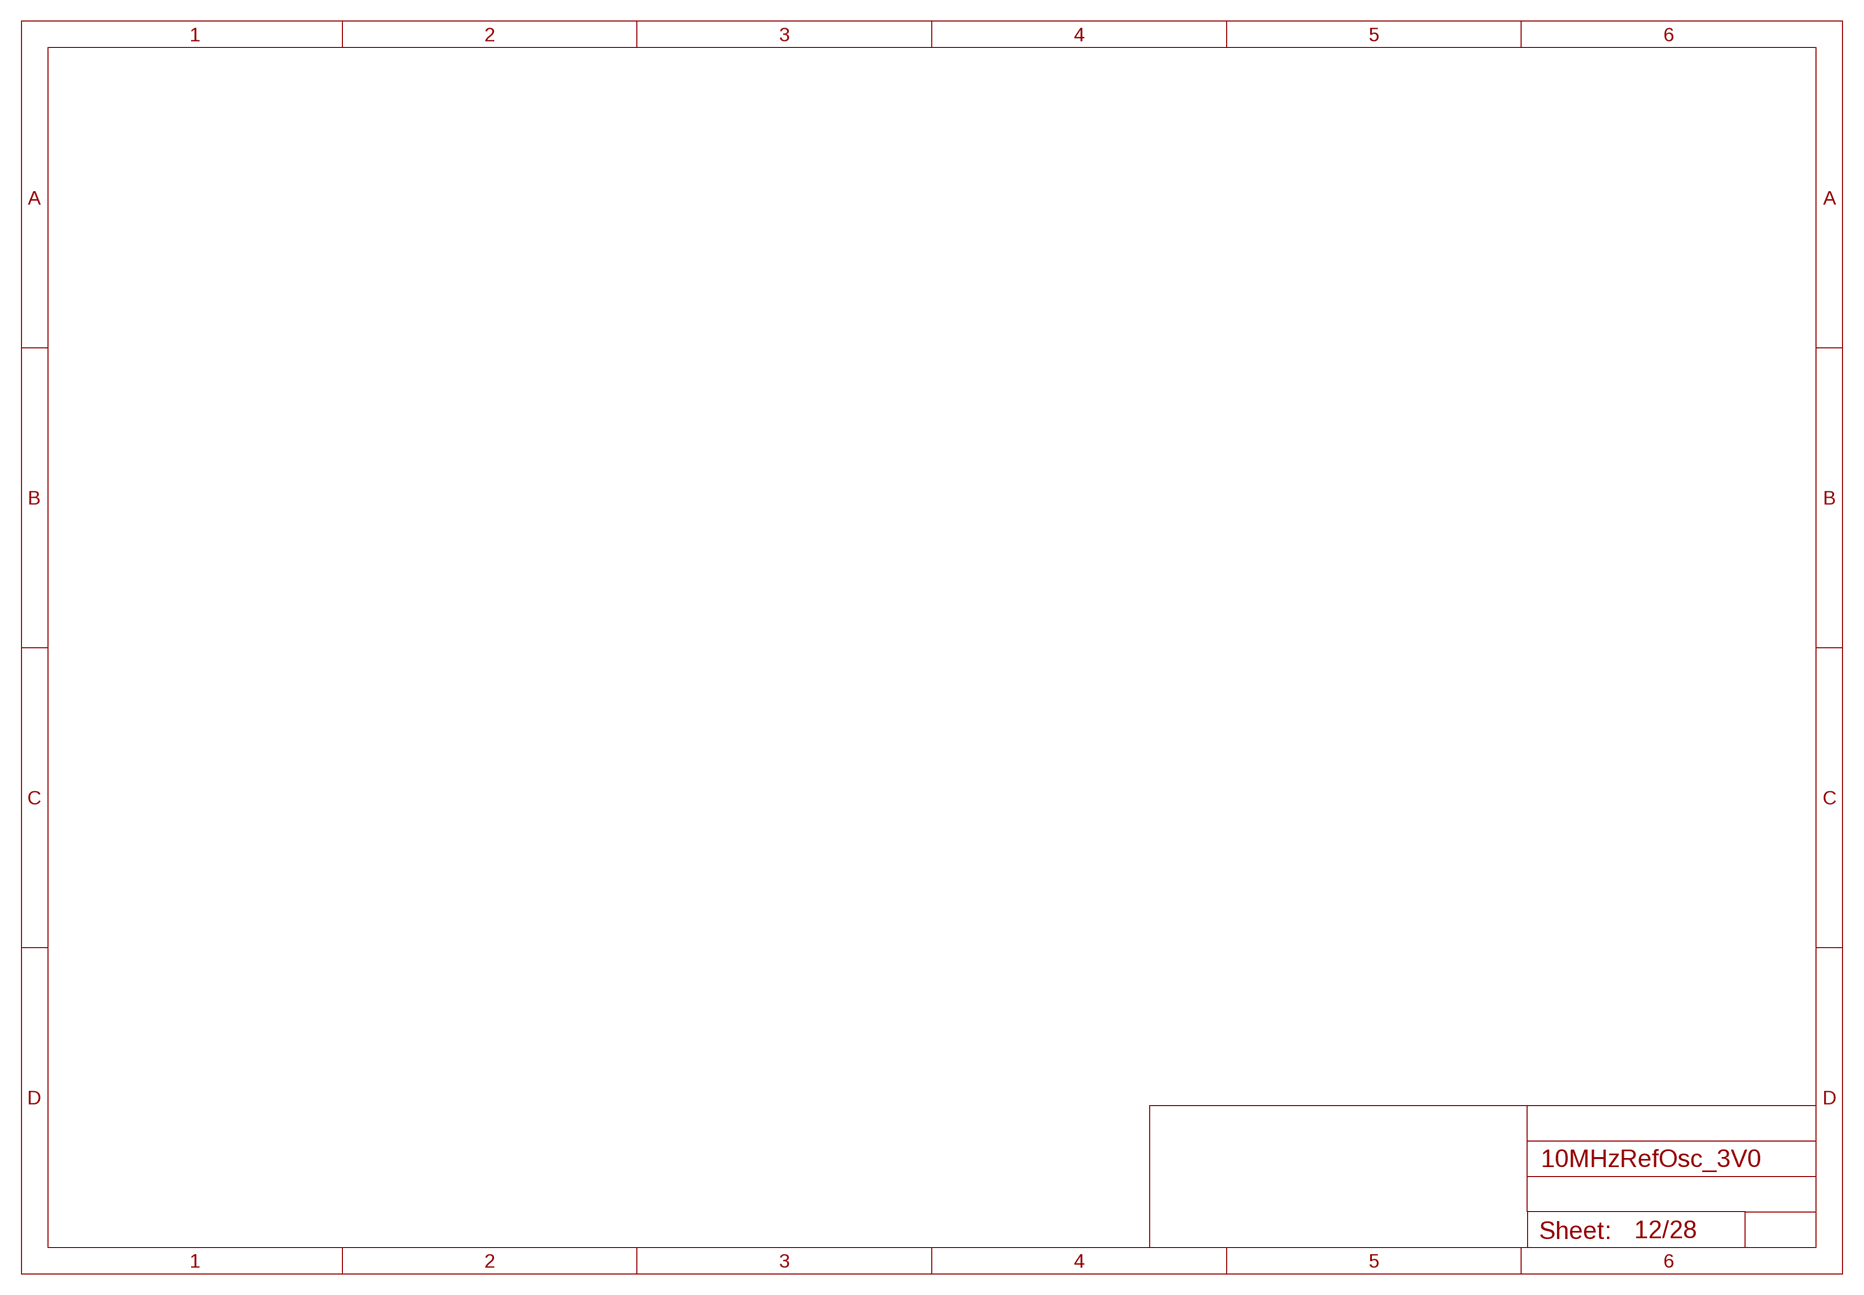
[diagram p11: schematic, sheet 12]
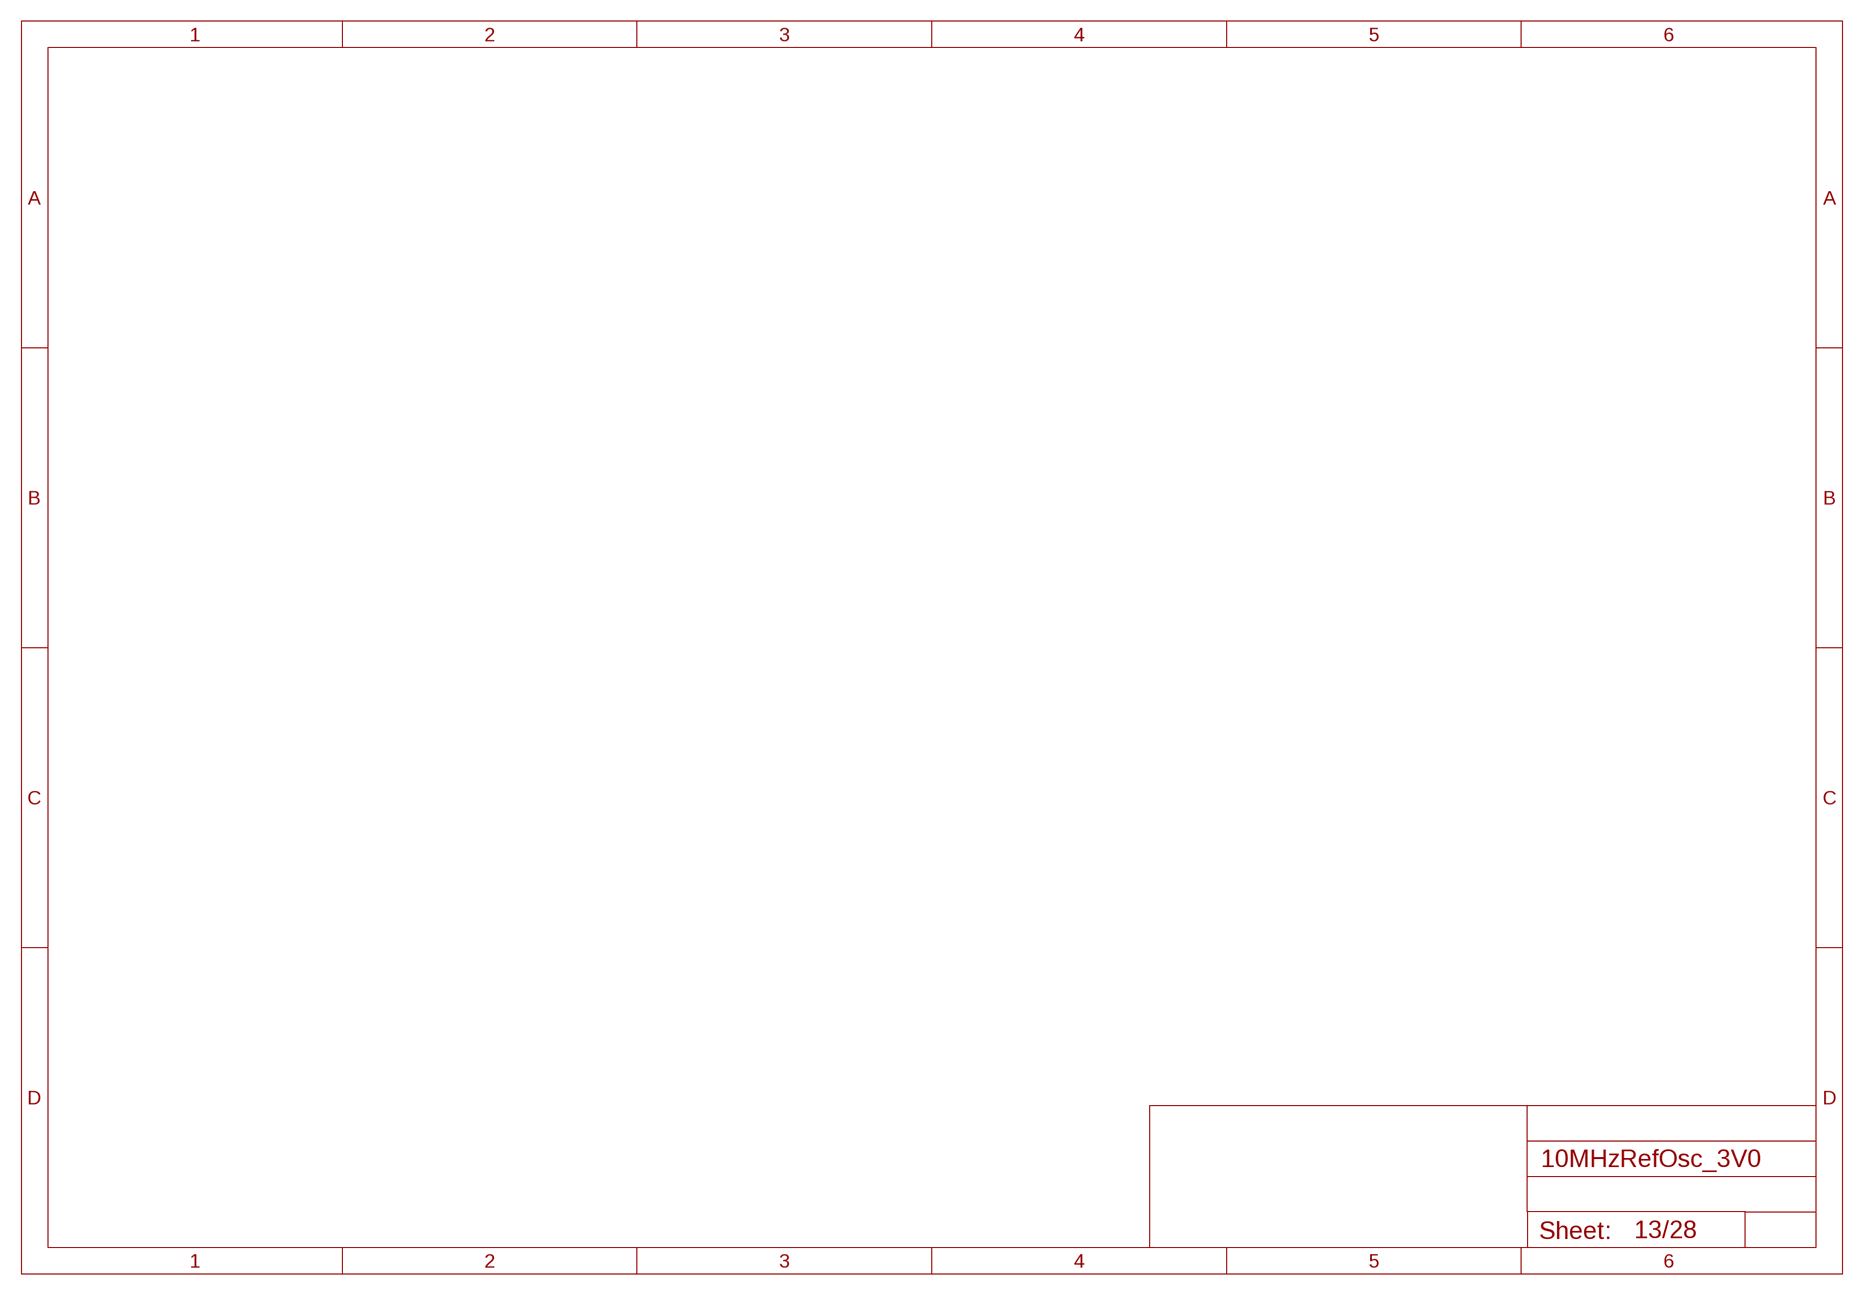
[diagram p12: schematic, sheet 13]
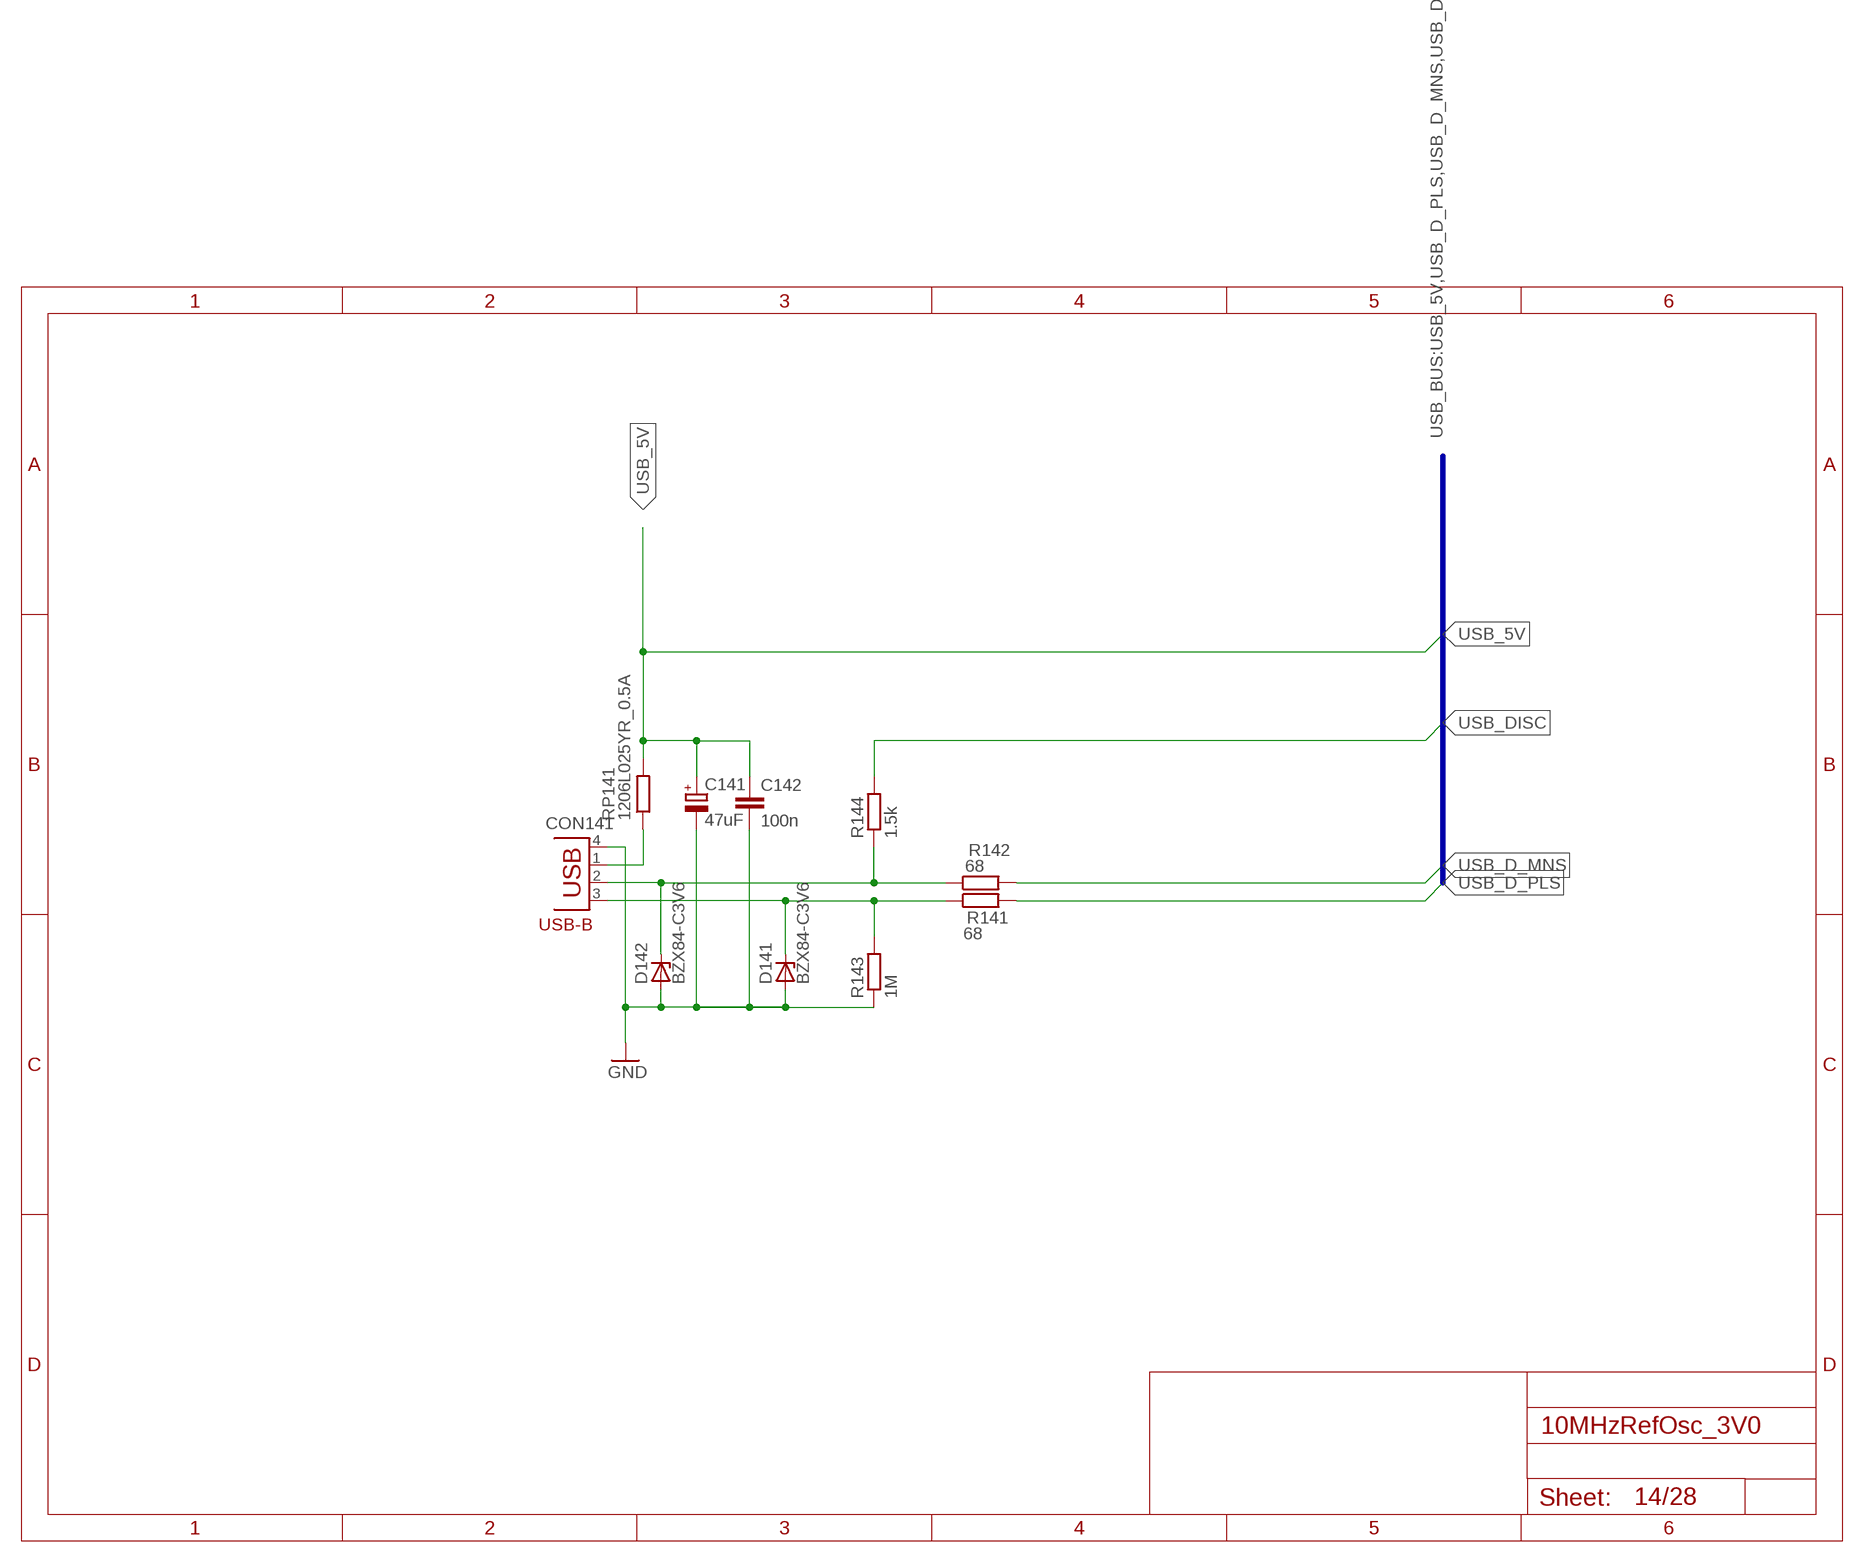
[diagram p13: schematic, sheet 14]
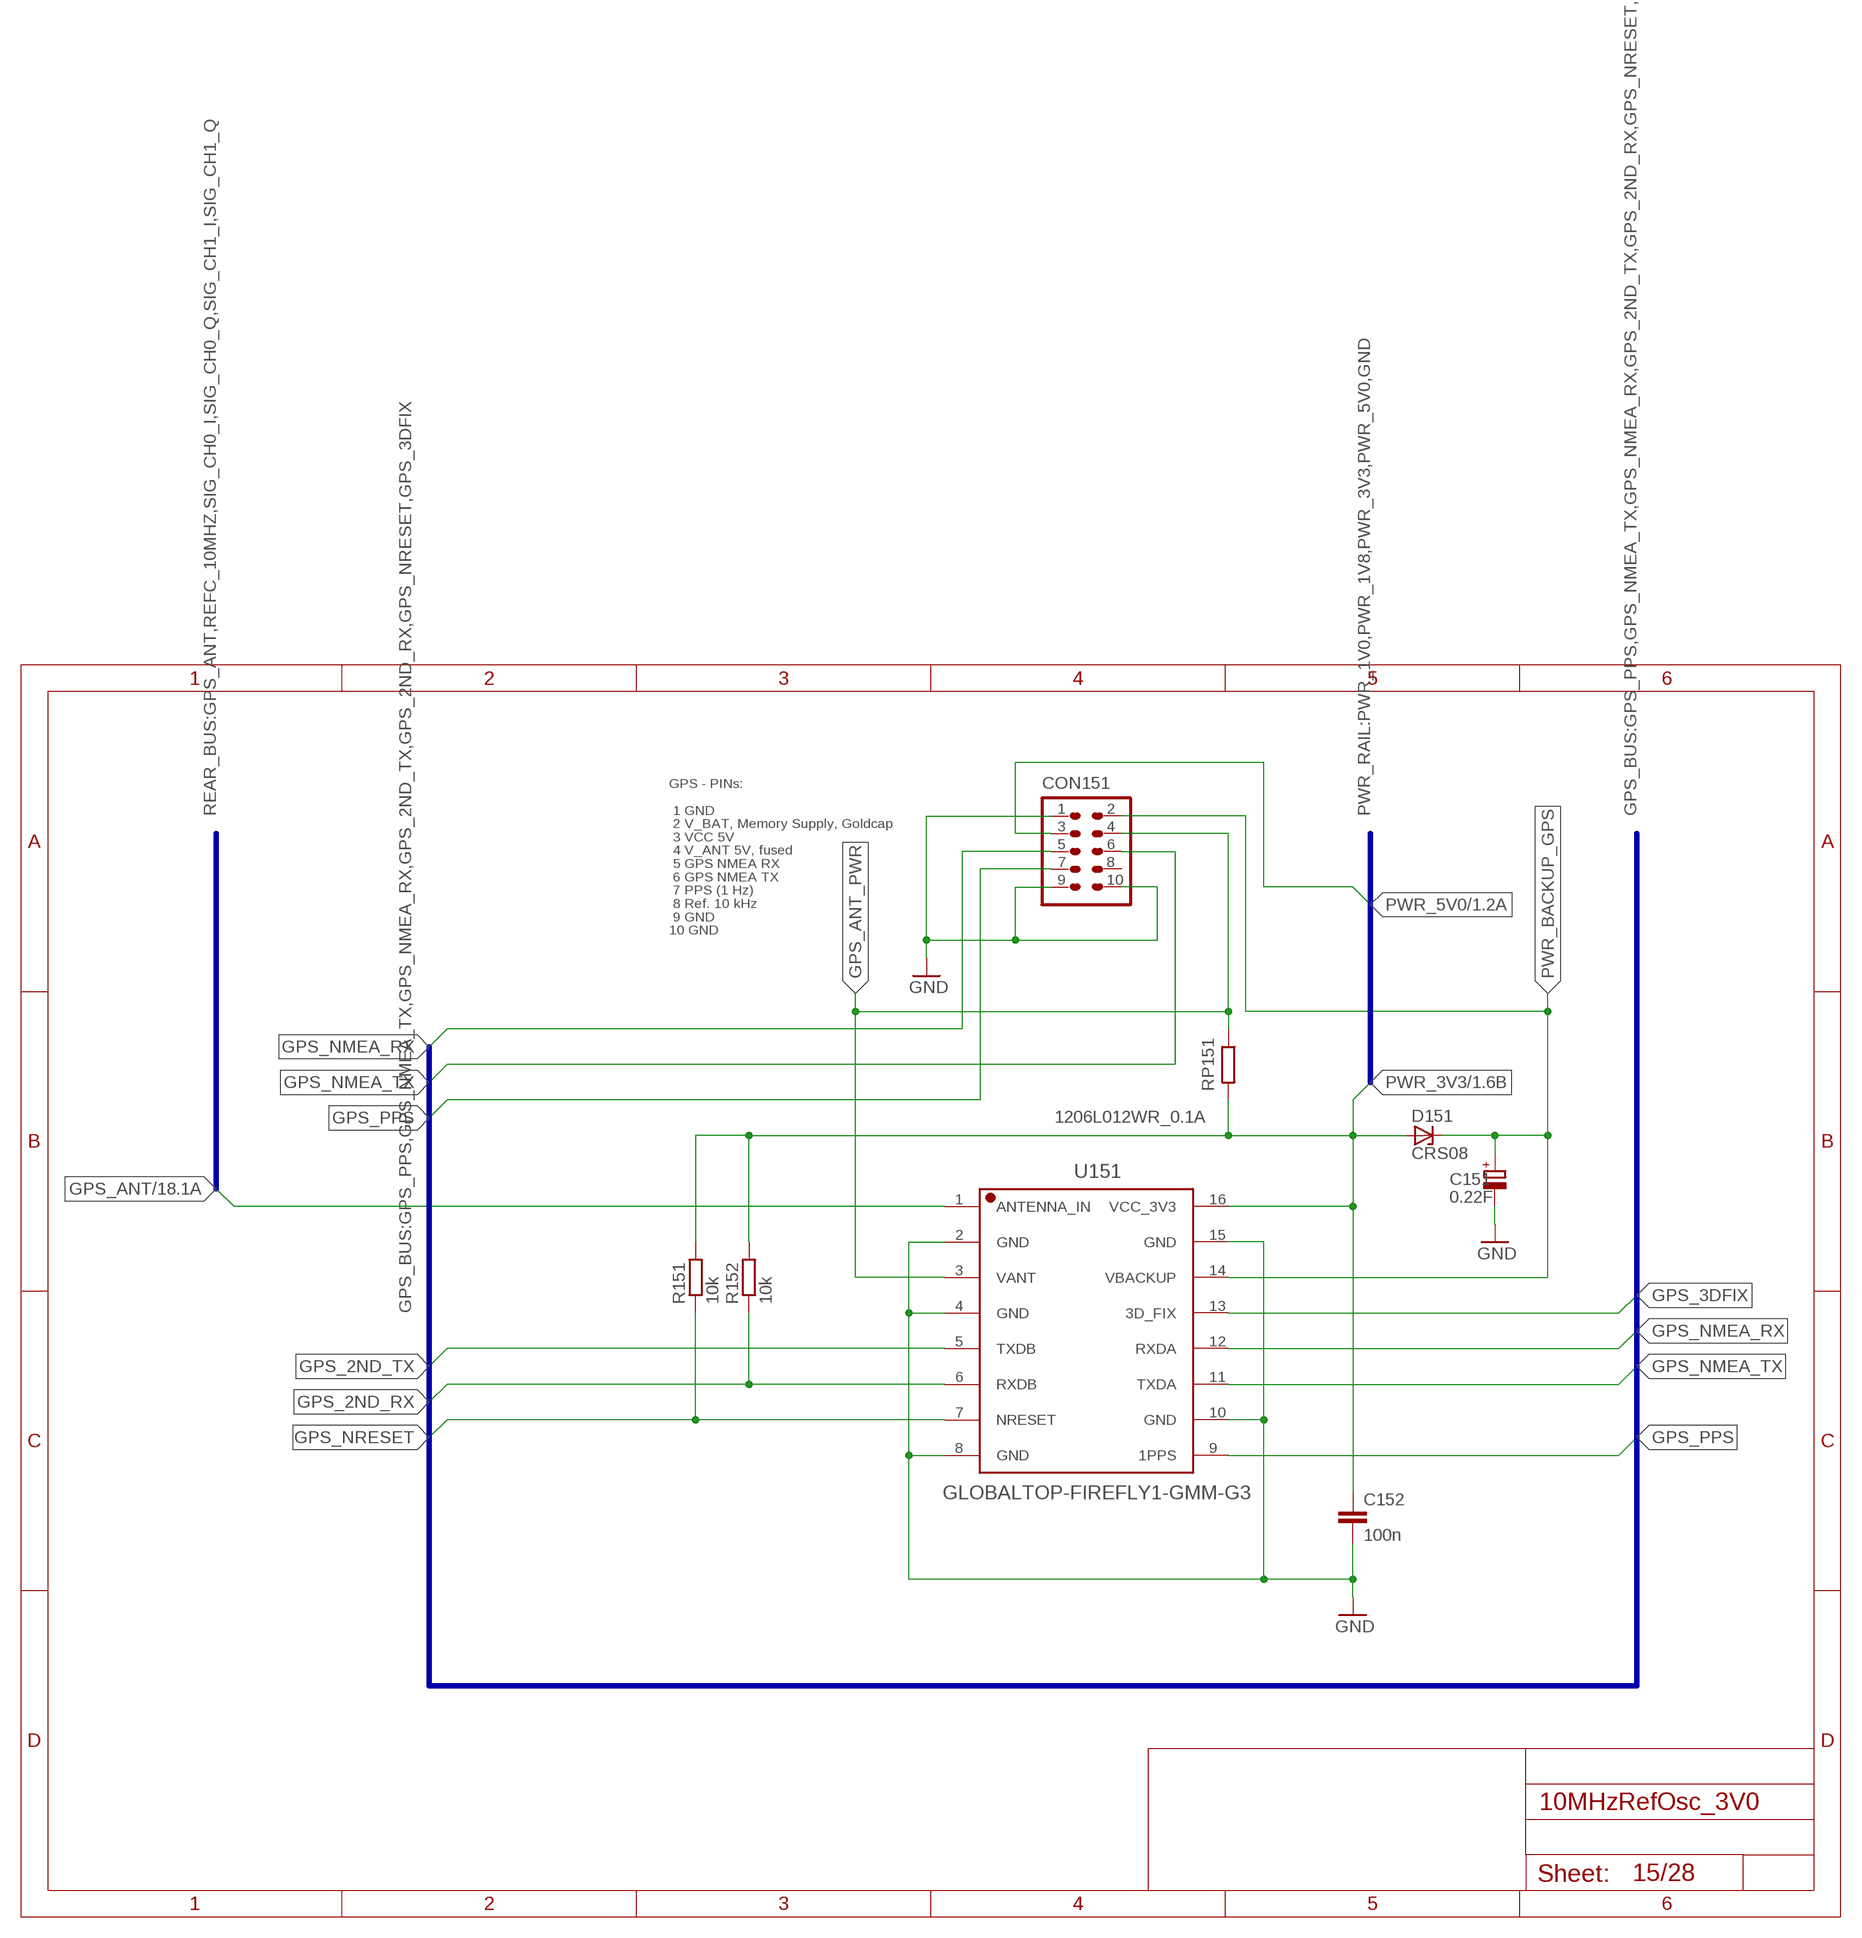
[diagram p14: schematic, sheet 15]
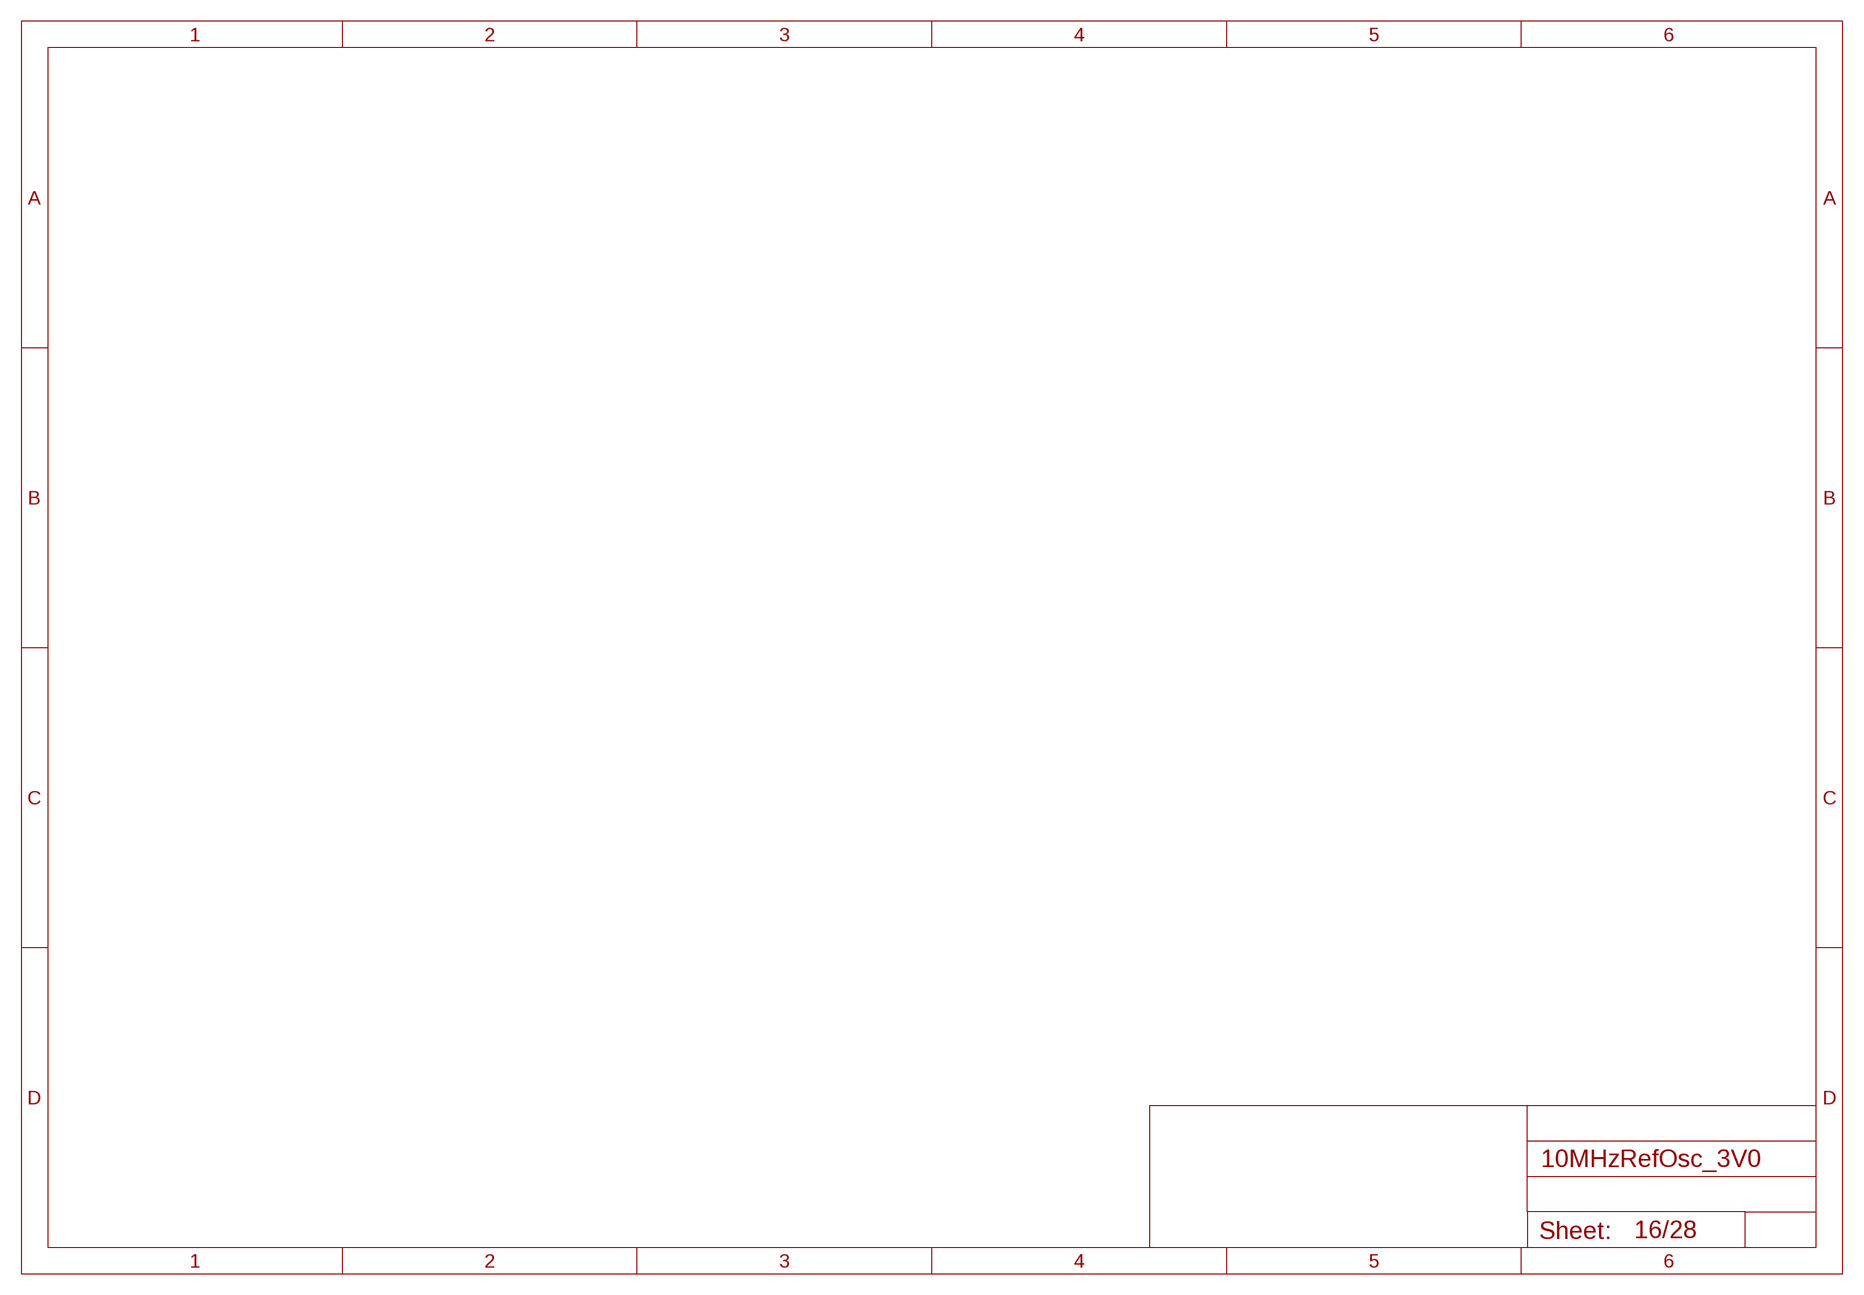
[diagram p15: schematic, sheet 16]
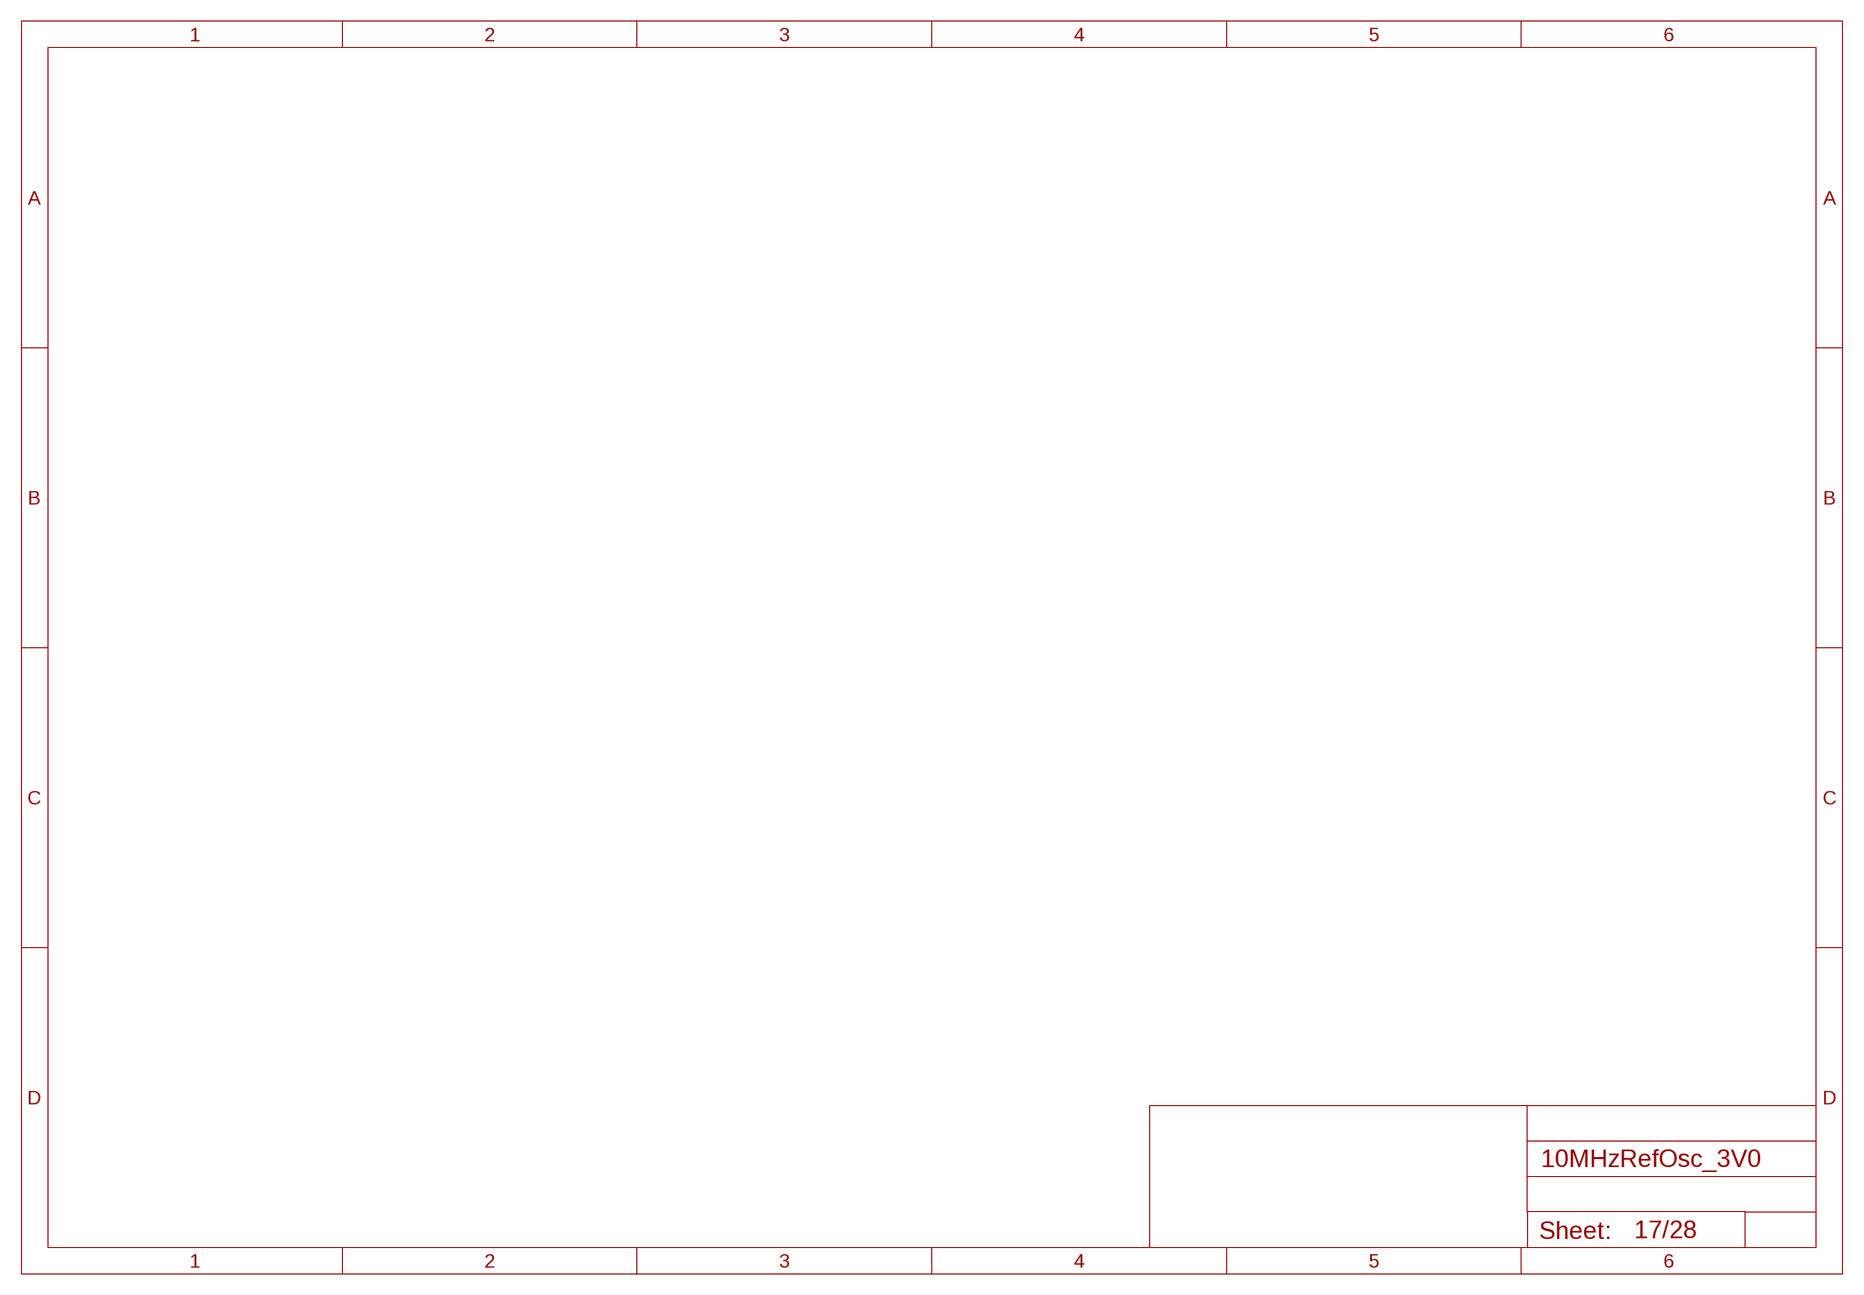
[diagram p16: schematic, sheet 17]
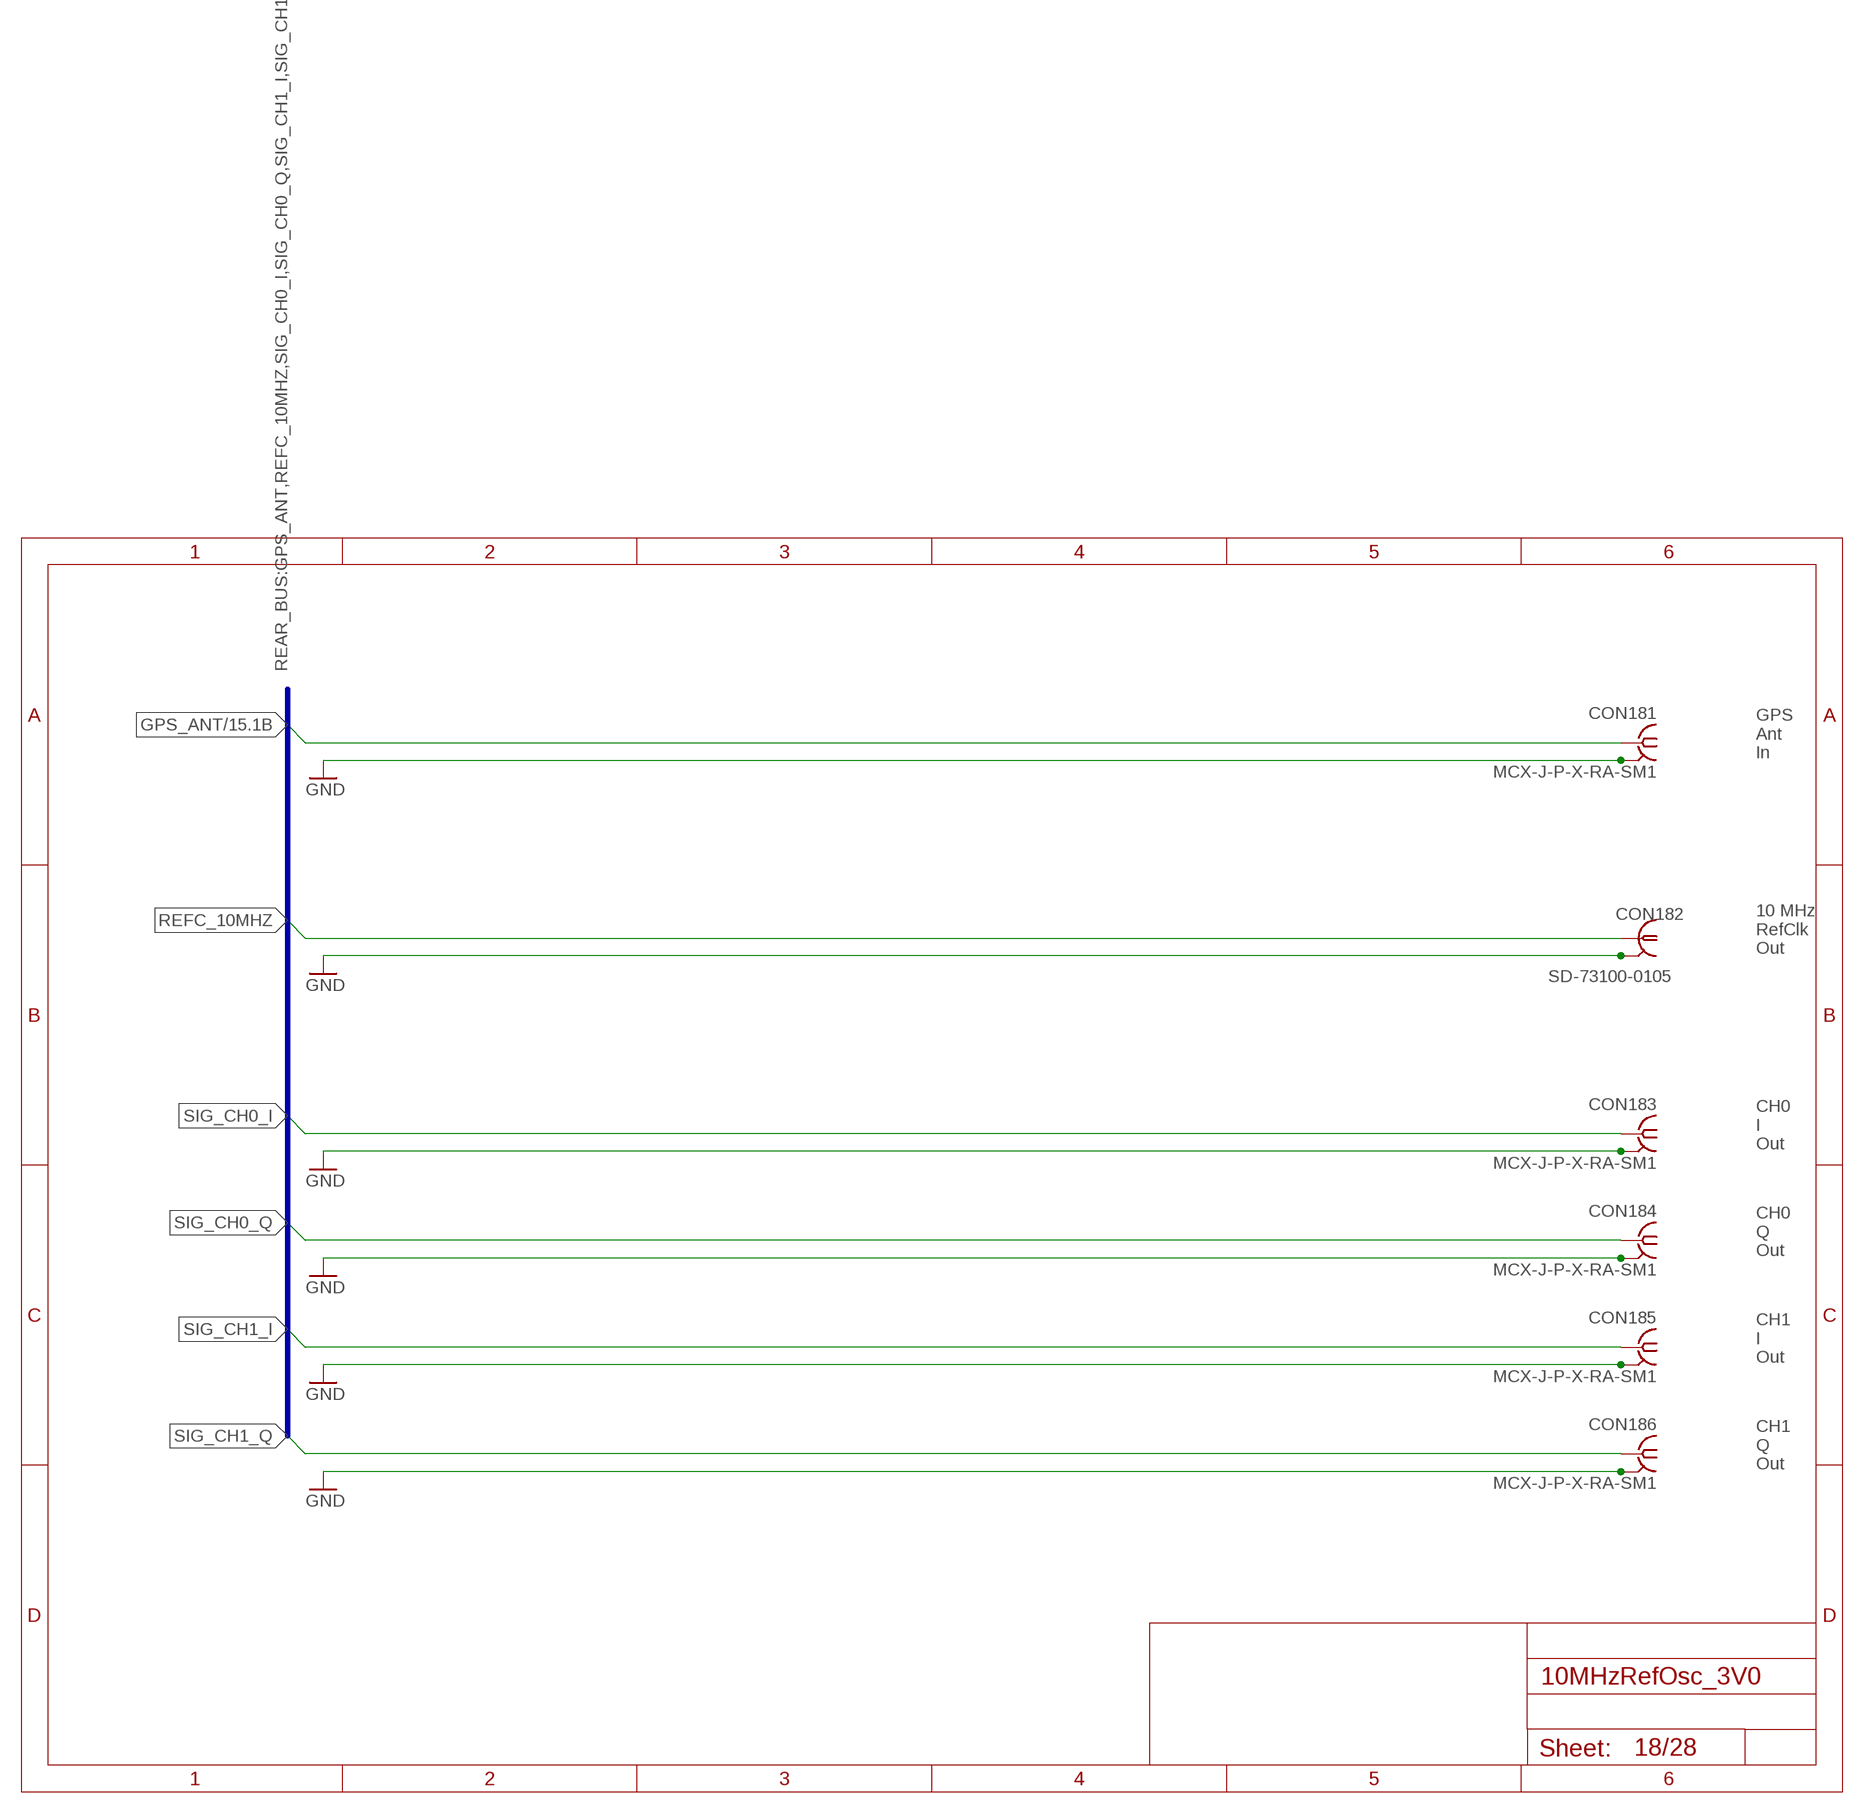
[diagram p17: schematic, sheet 18]
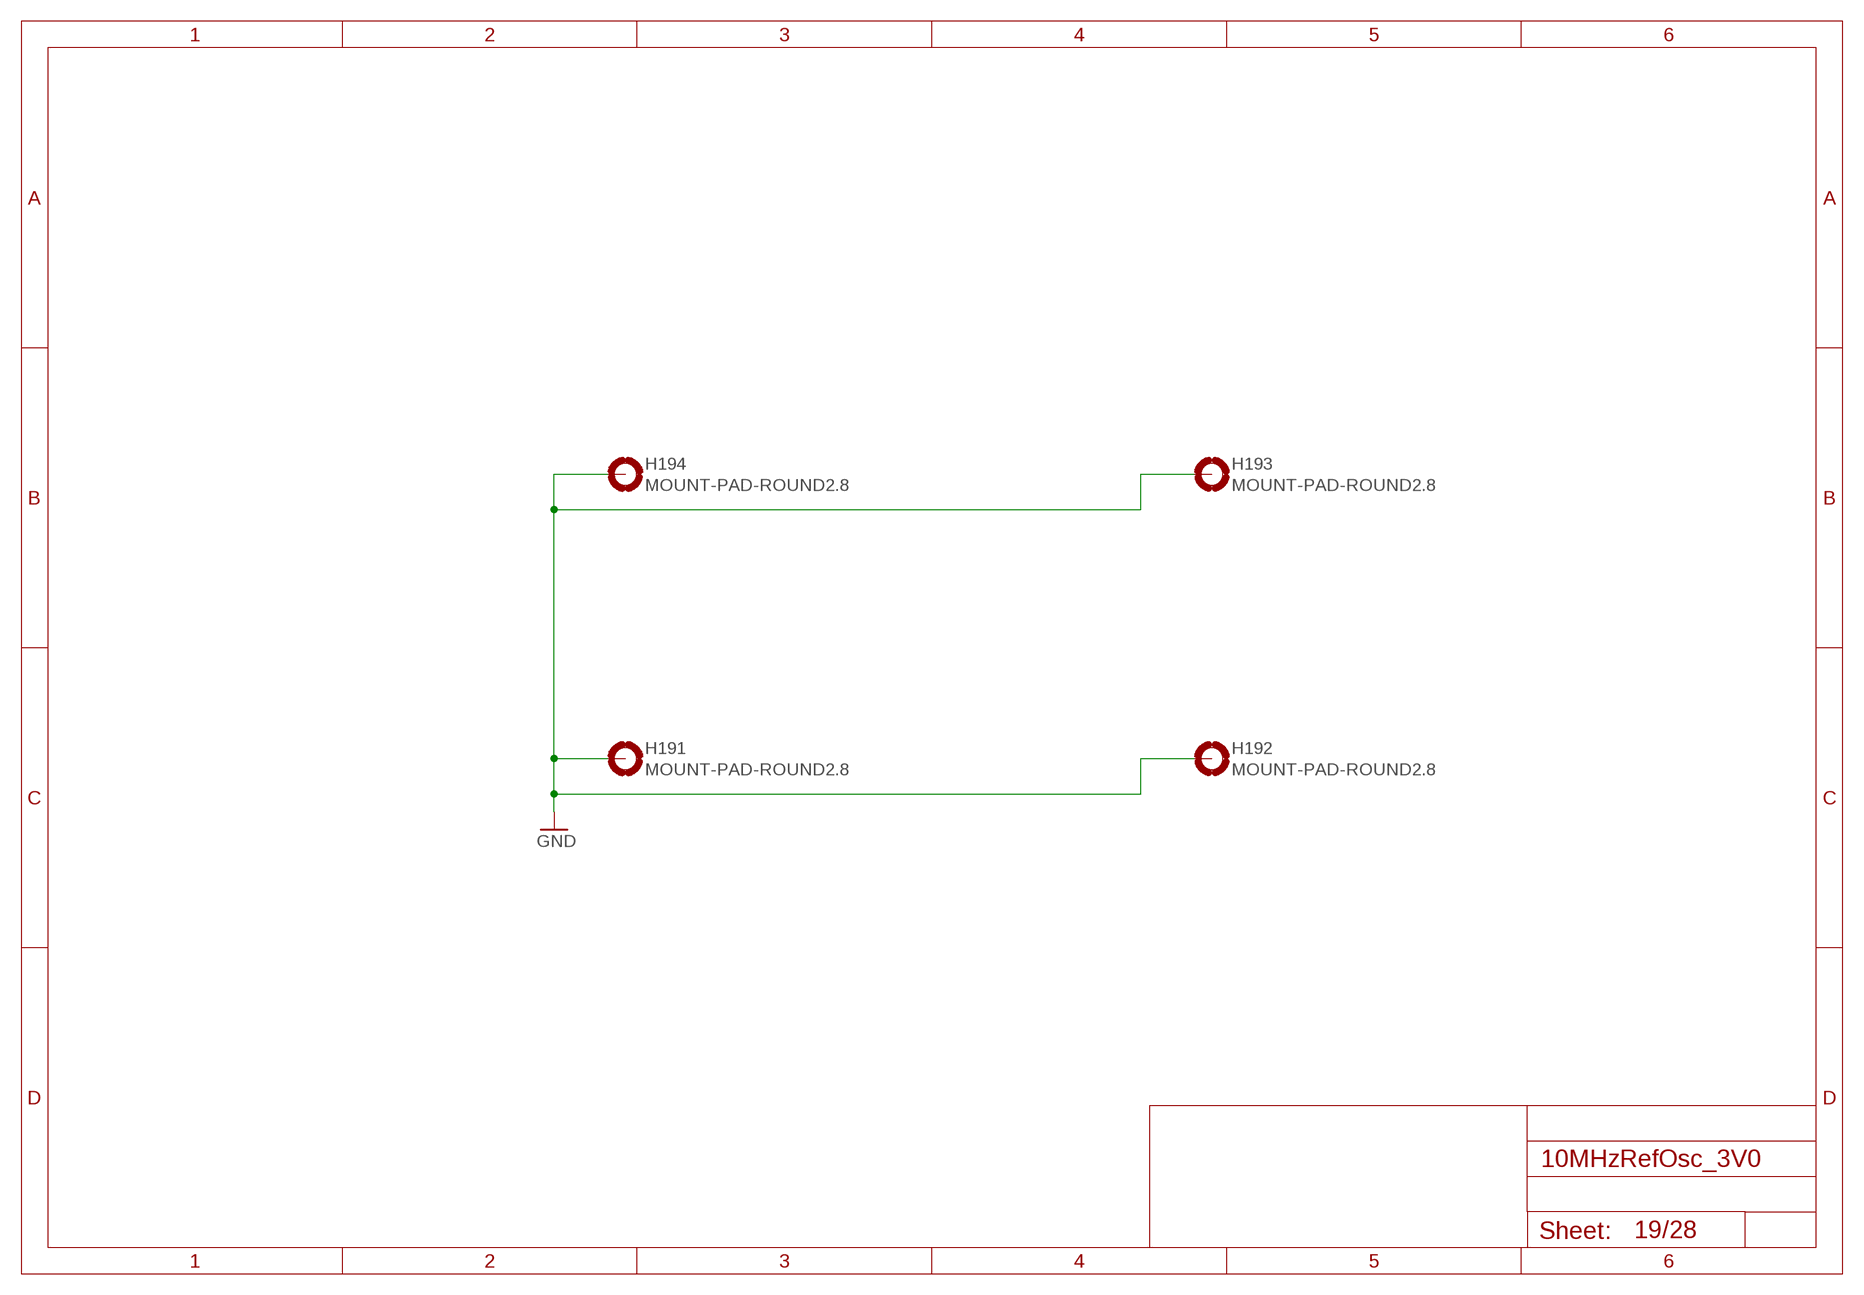
[diagram p18: schematic, sheet 19]
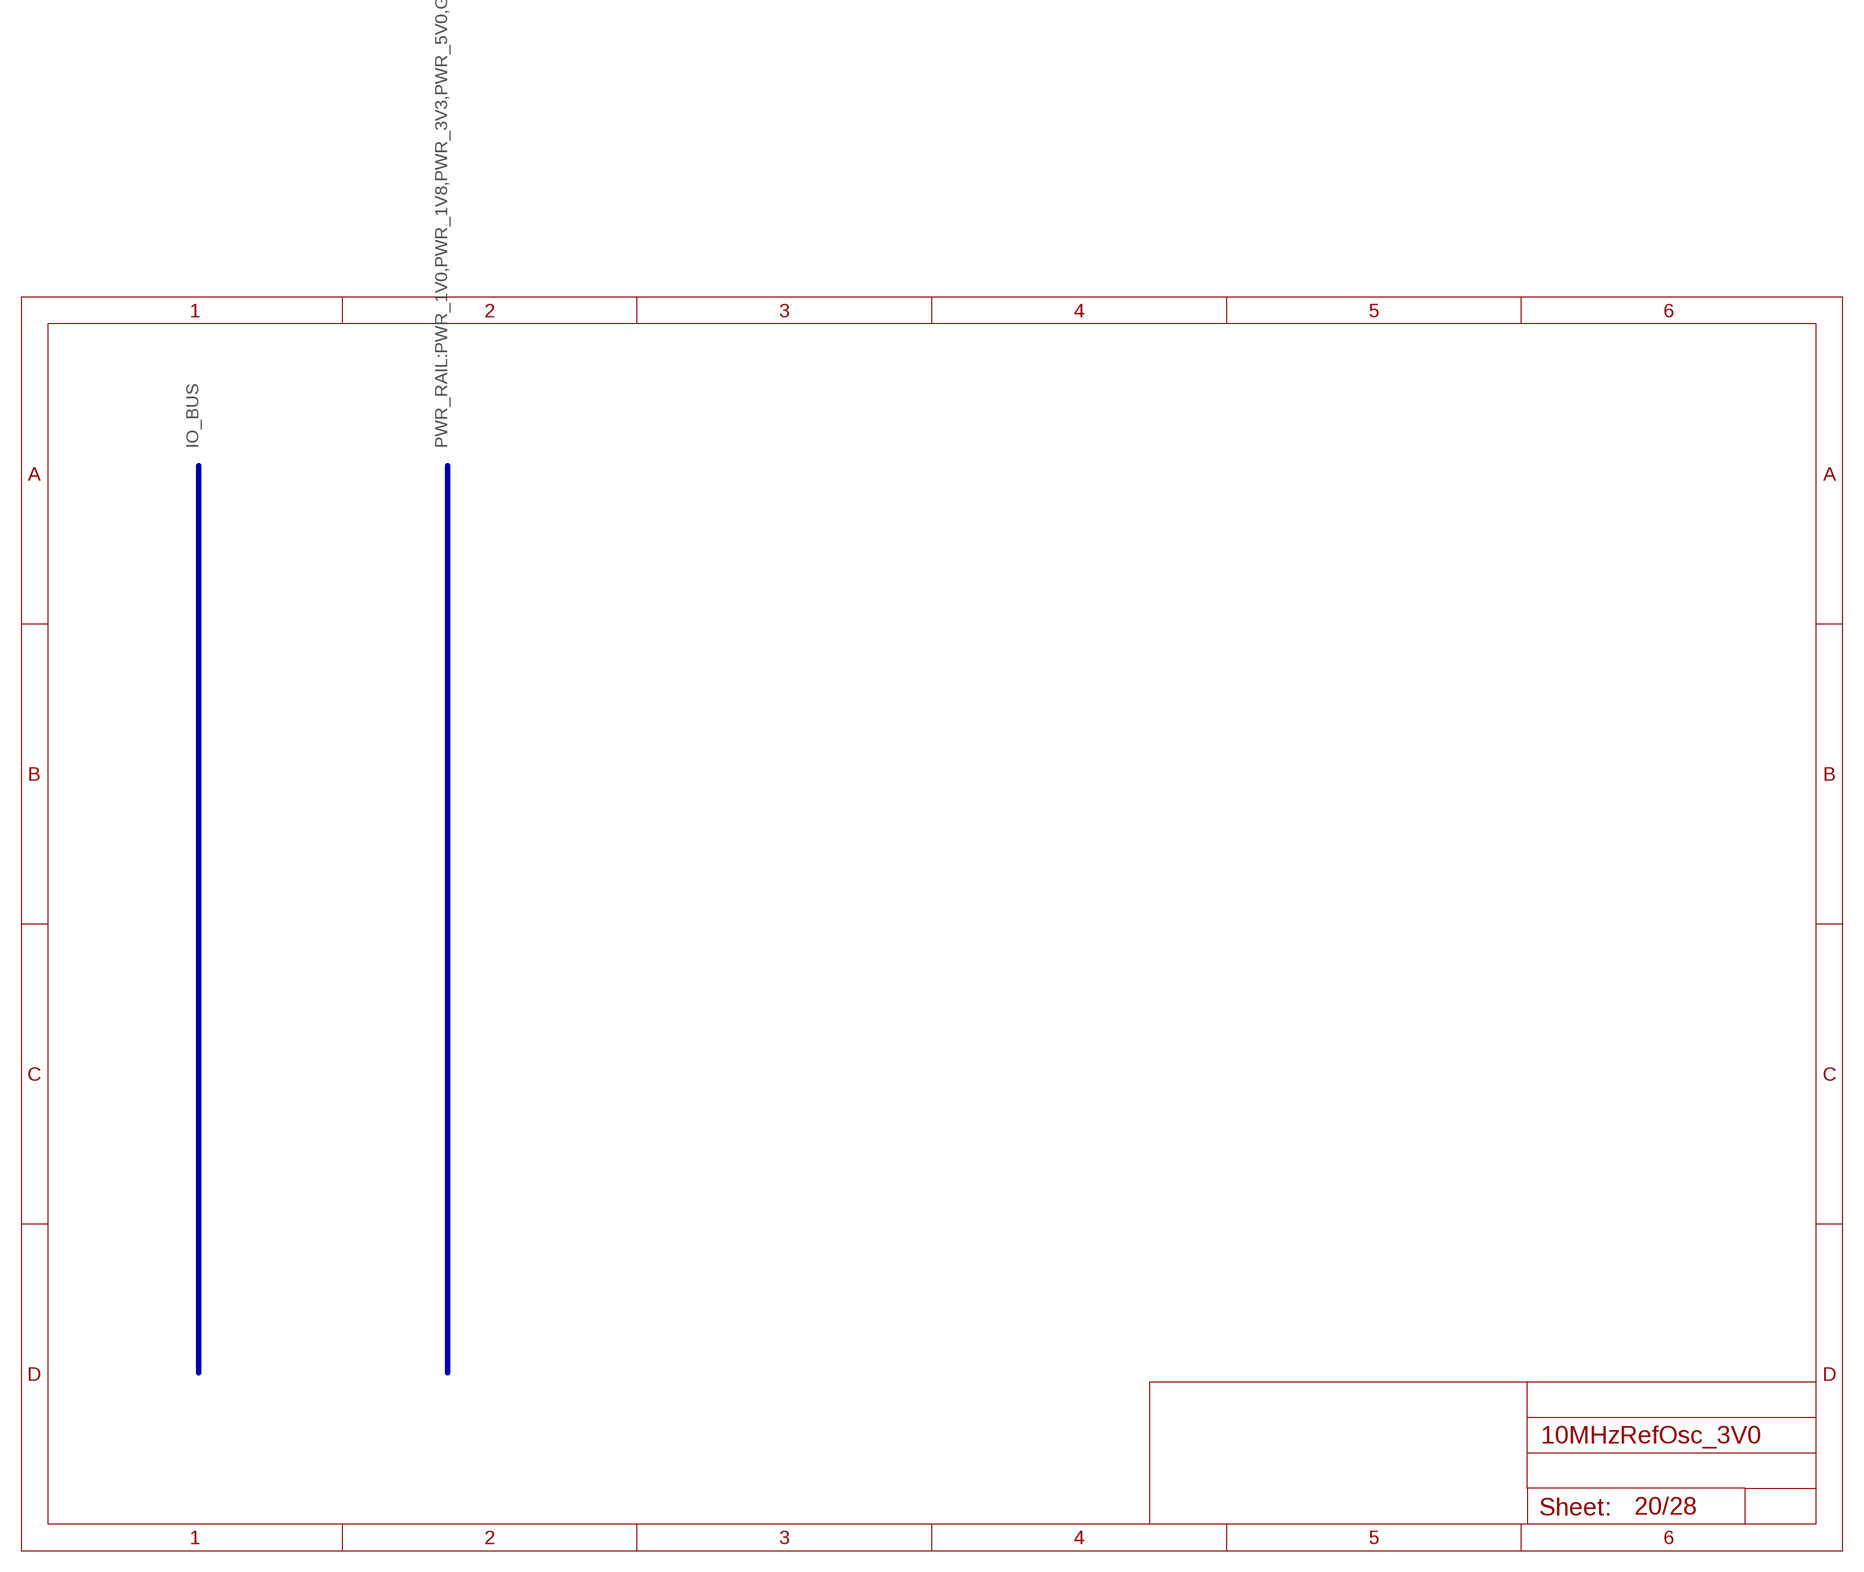
[diagram p19: schematic, sheet 20]
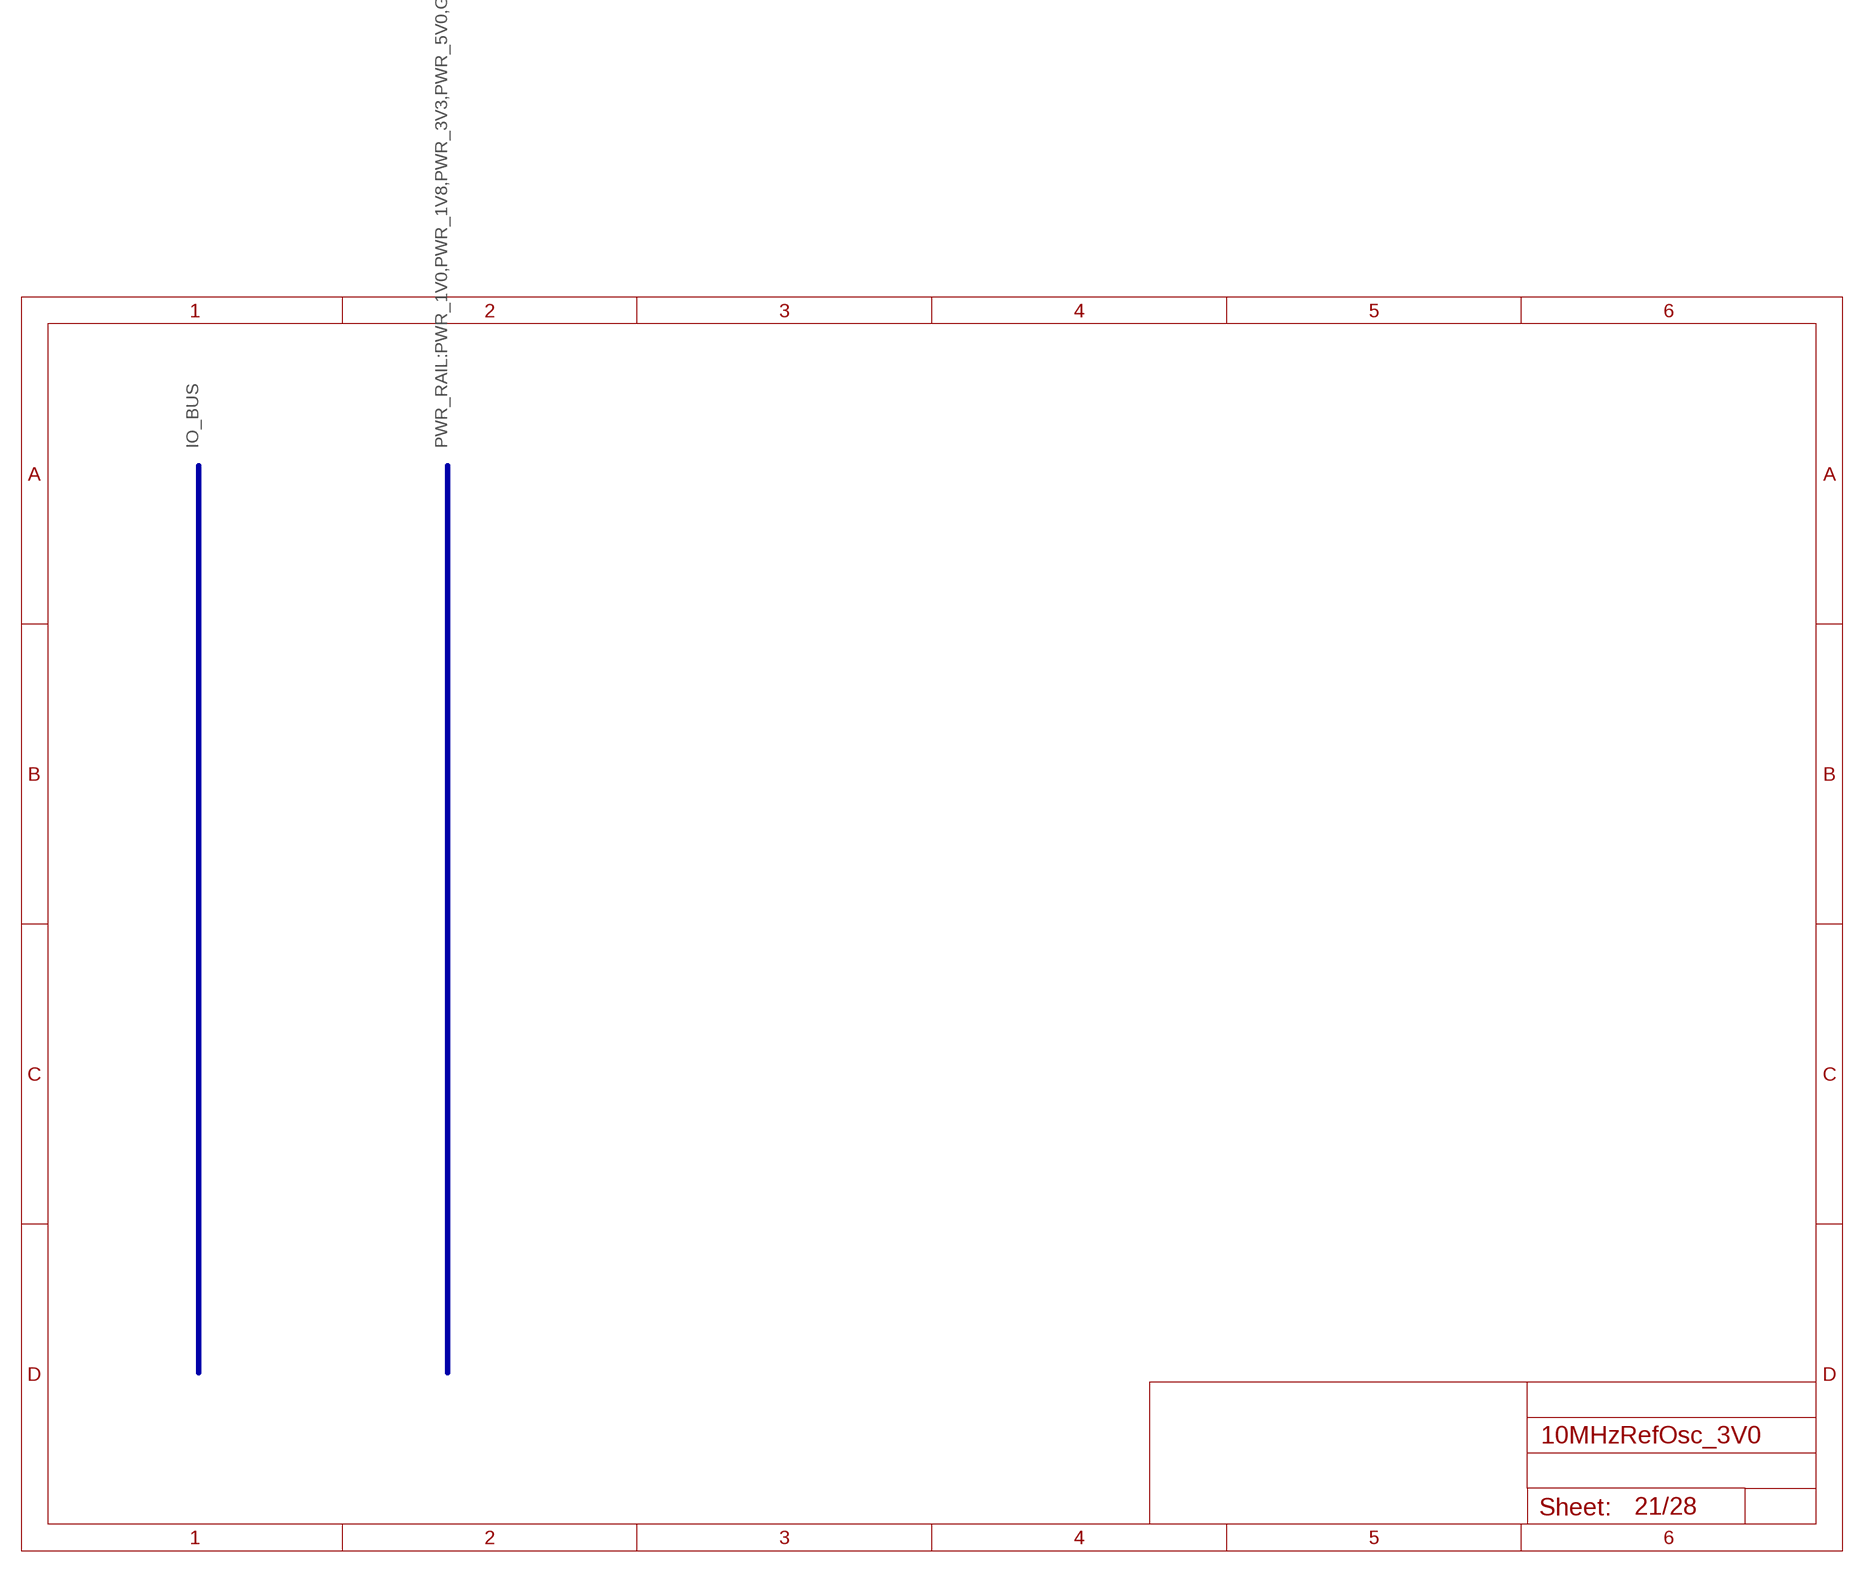
[diagram p20: schematic, sheet 21]
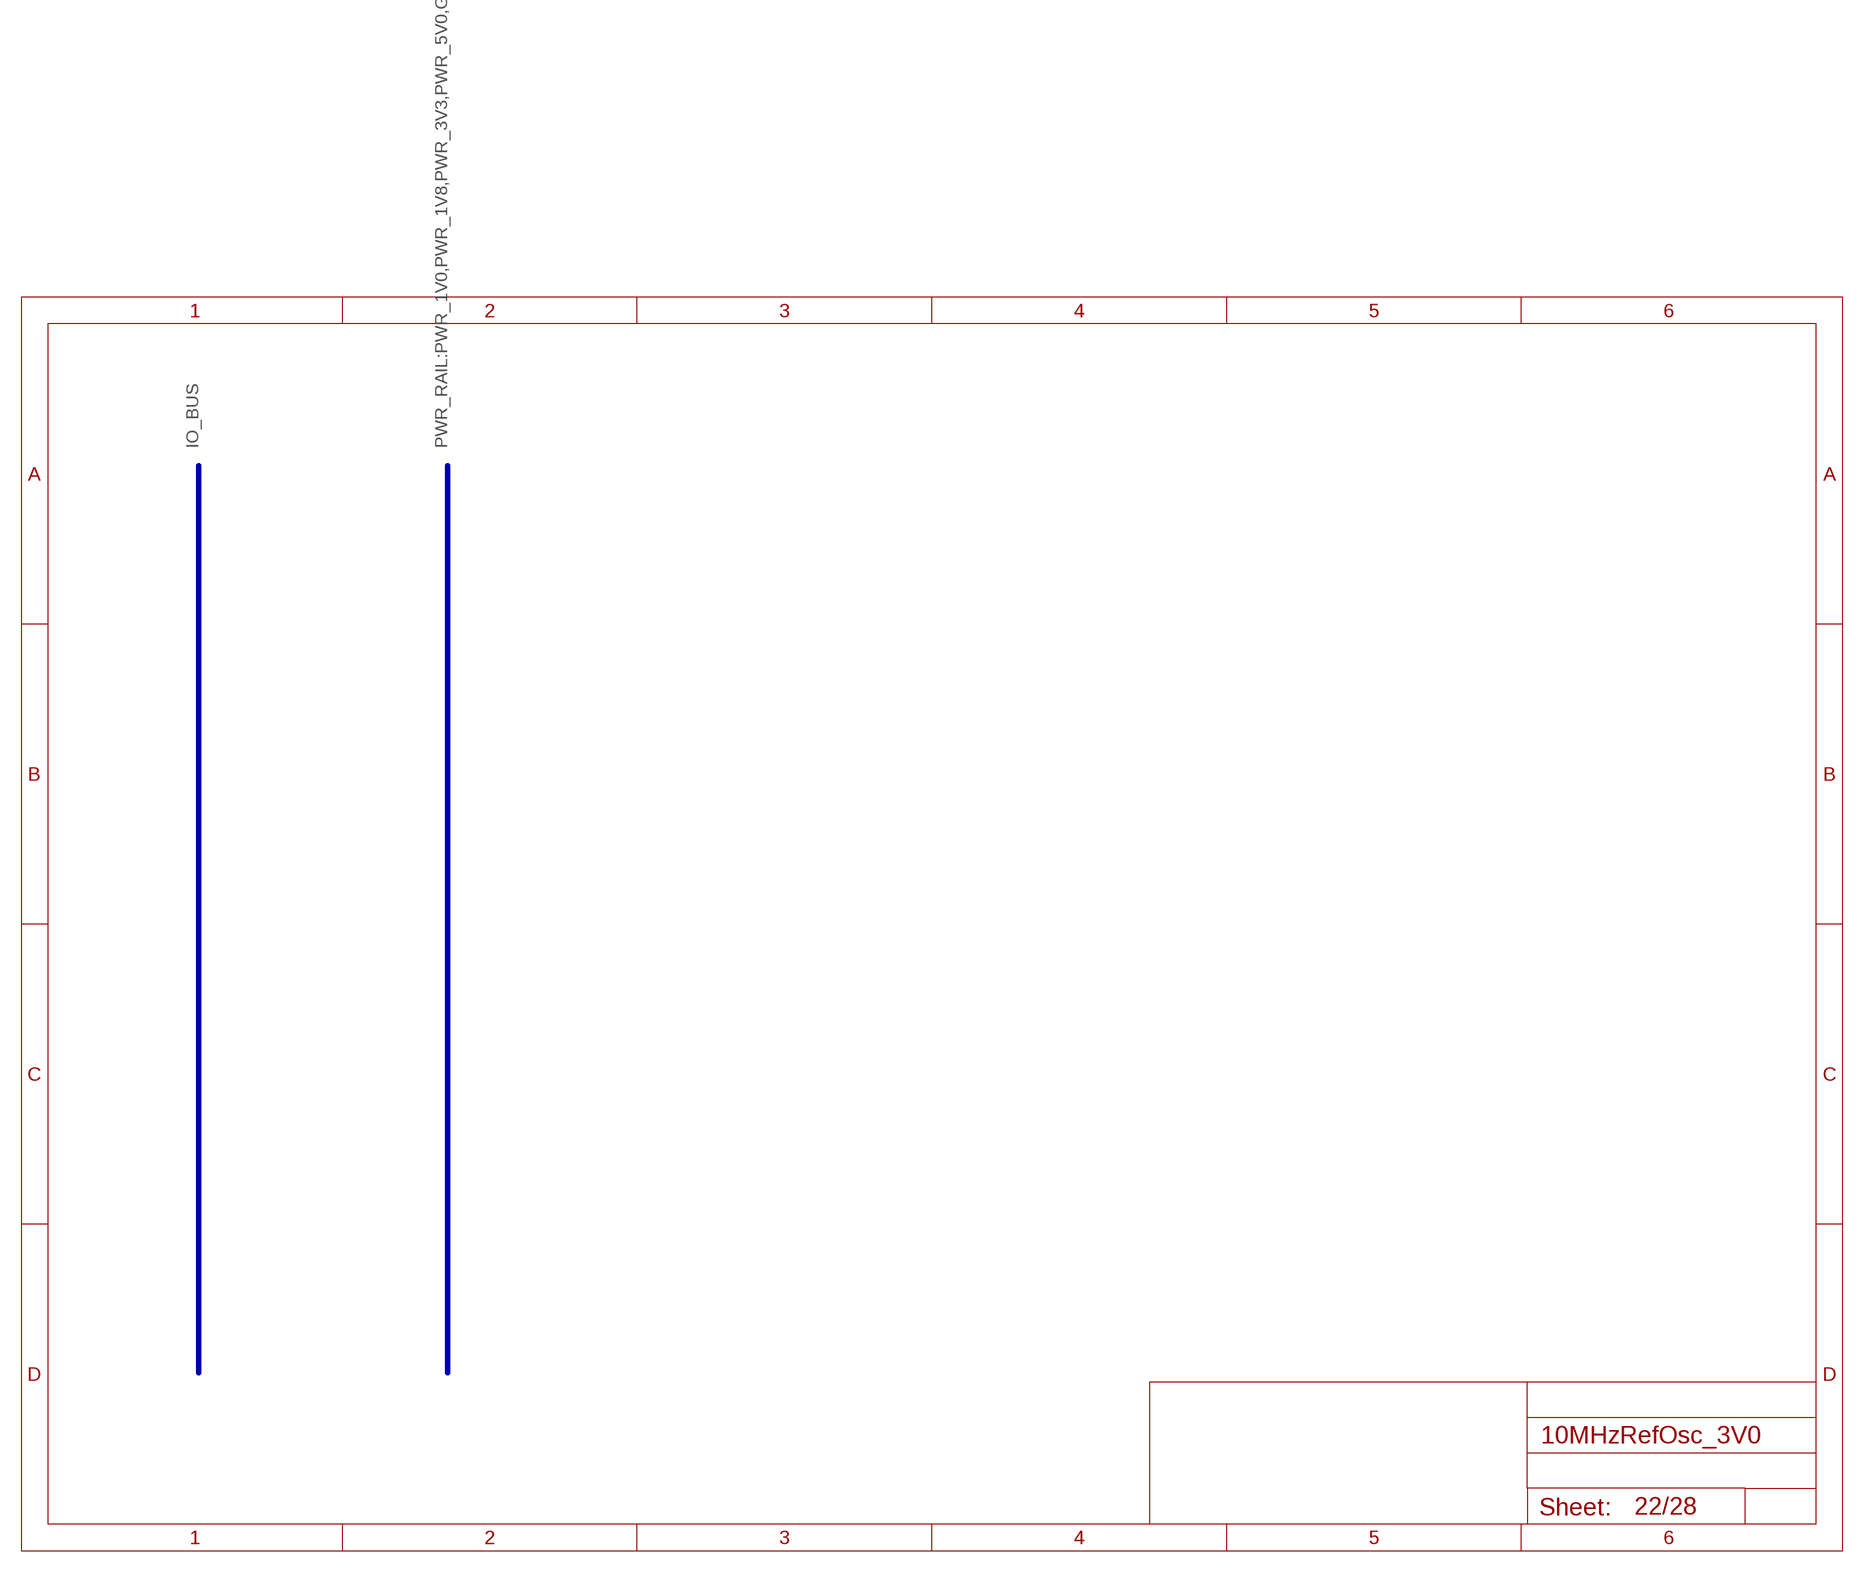
[diagram p21: schematic, sheet 22]
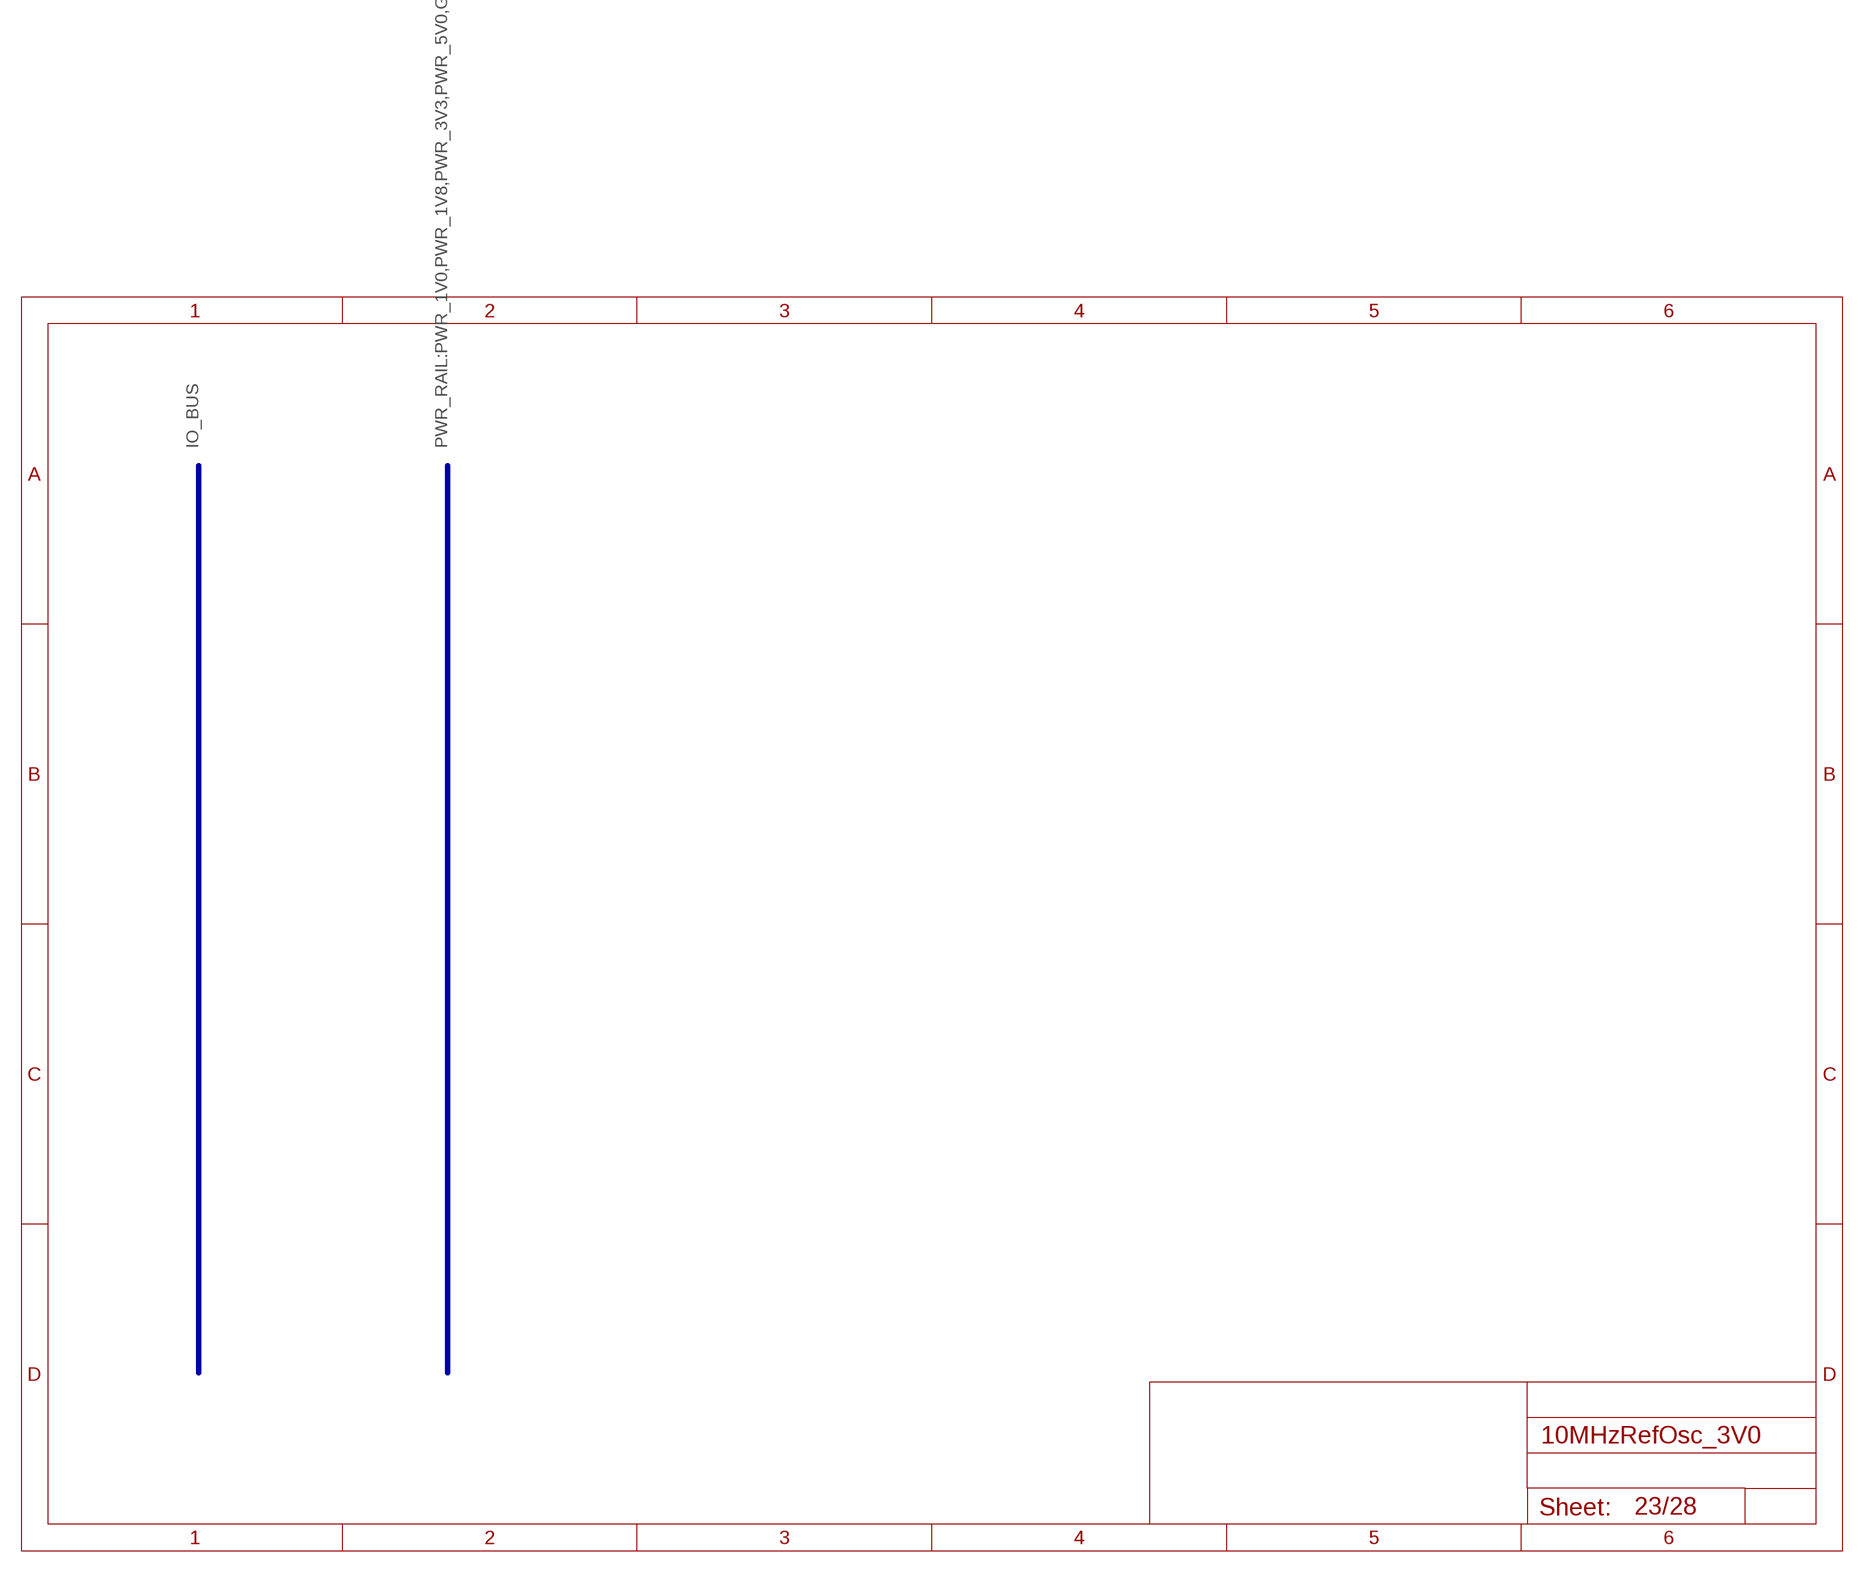
[diagram p22: schematic, sheet 23]
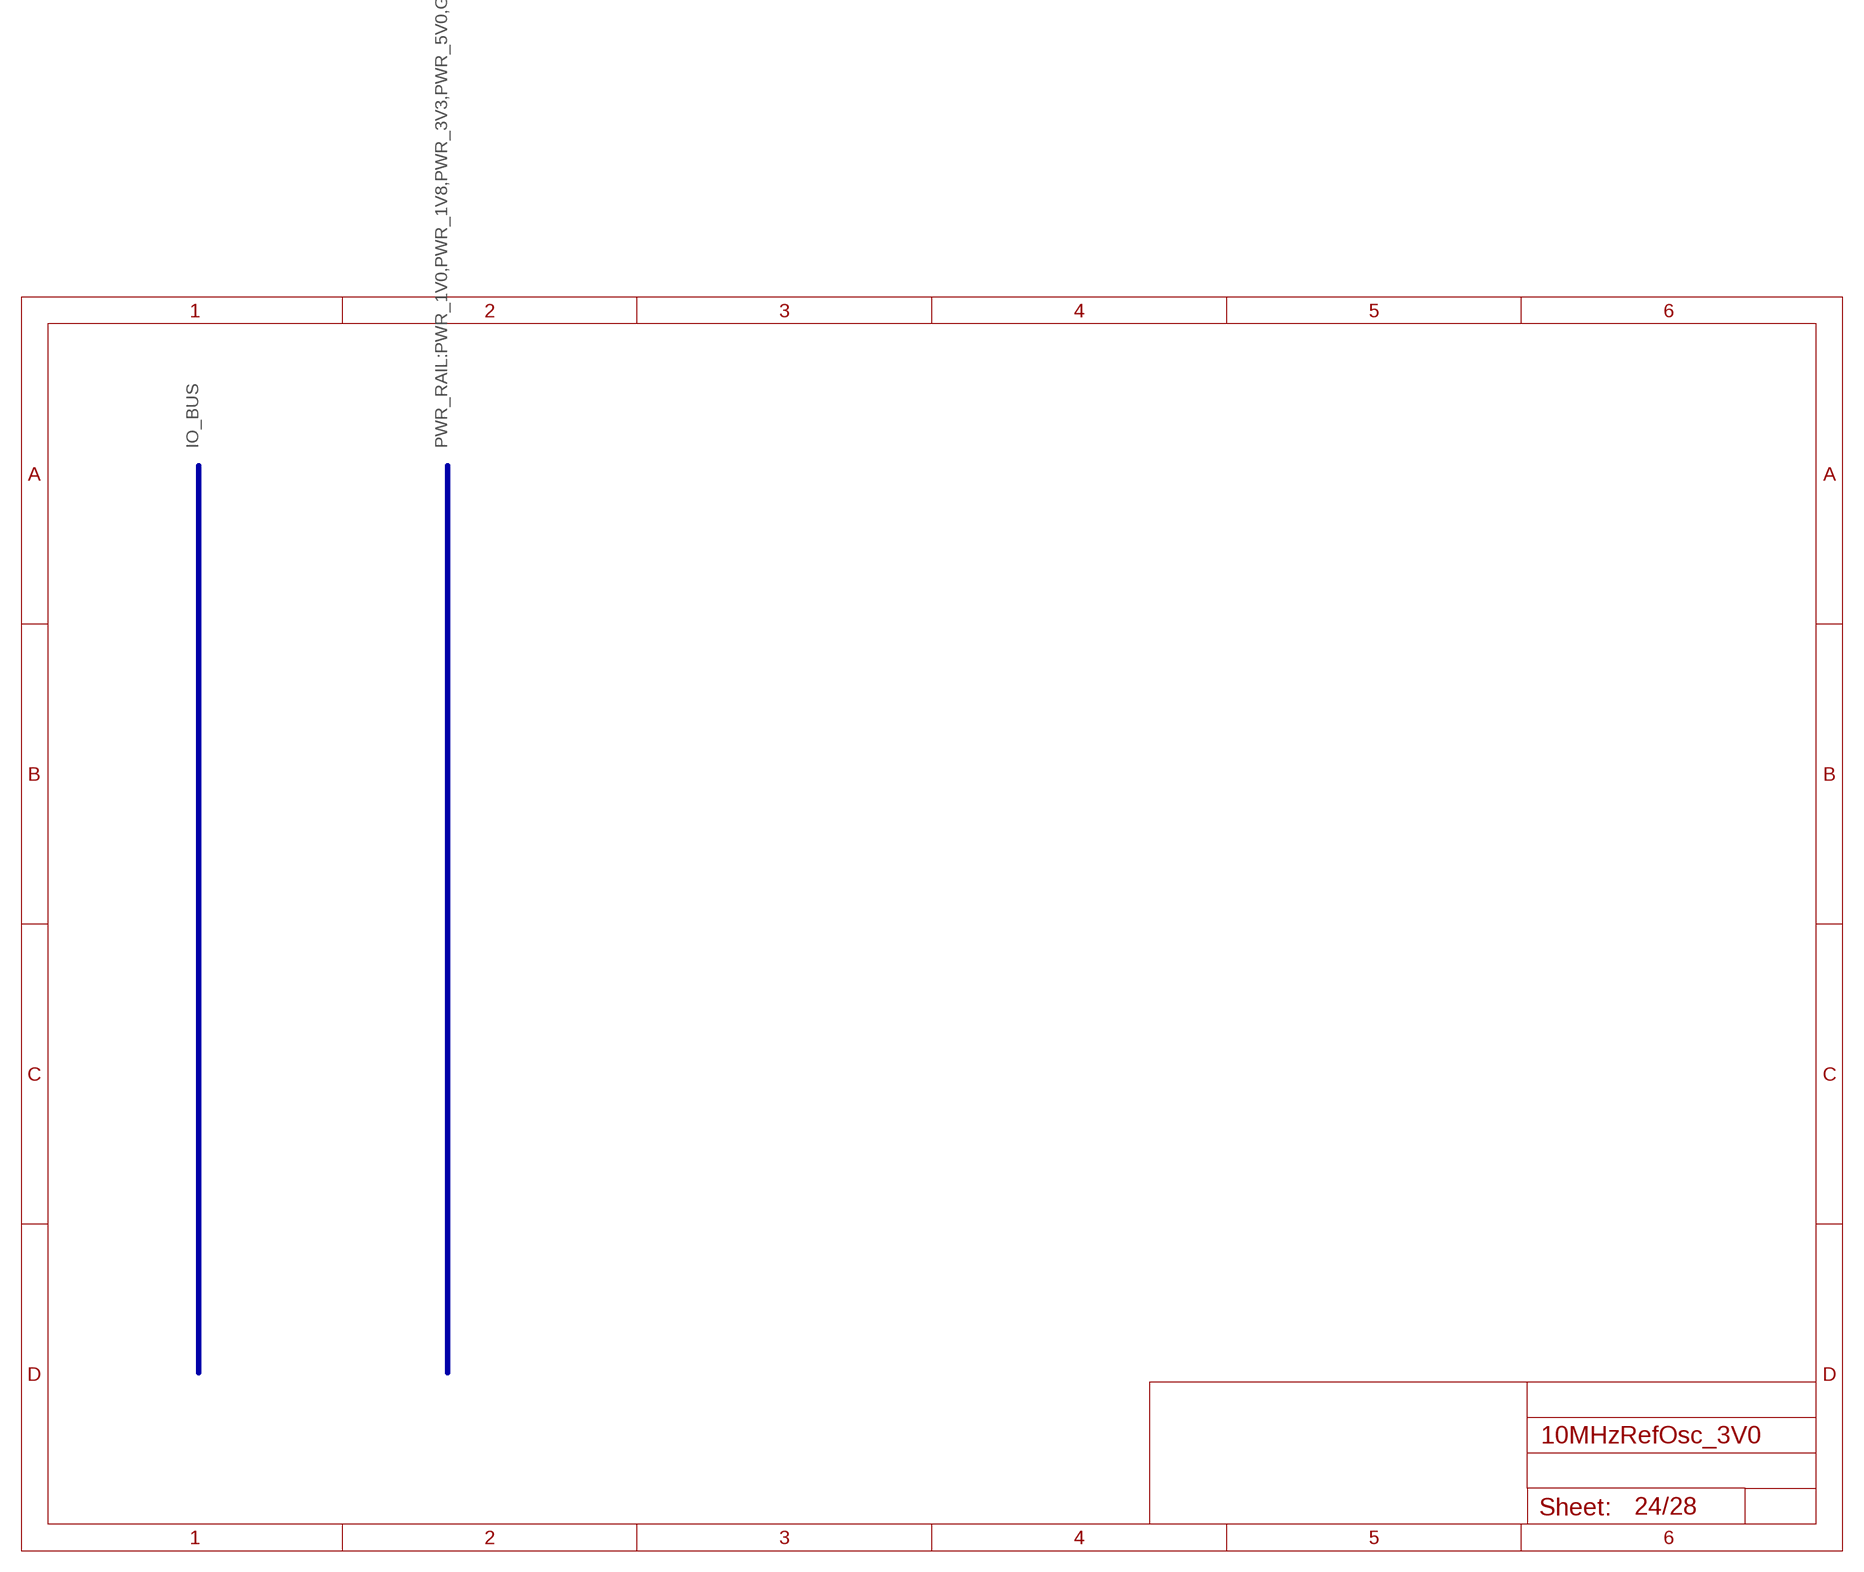
[diagram p23: schematic, sheet 24]
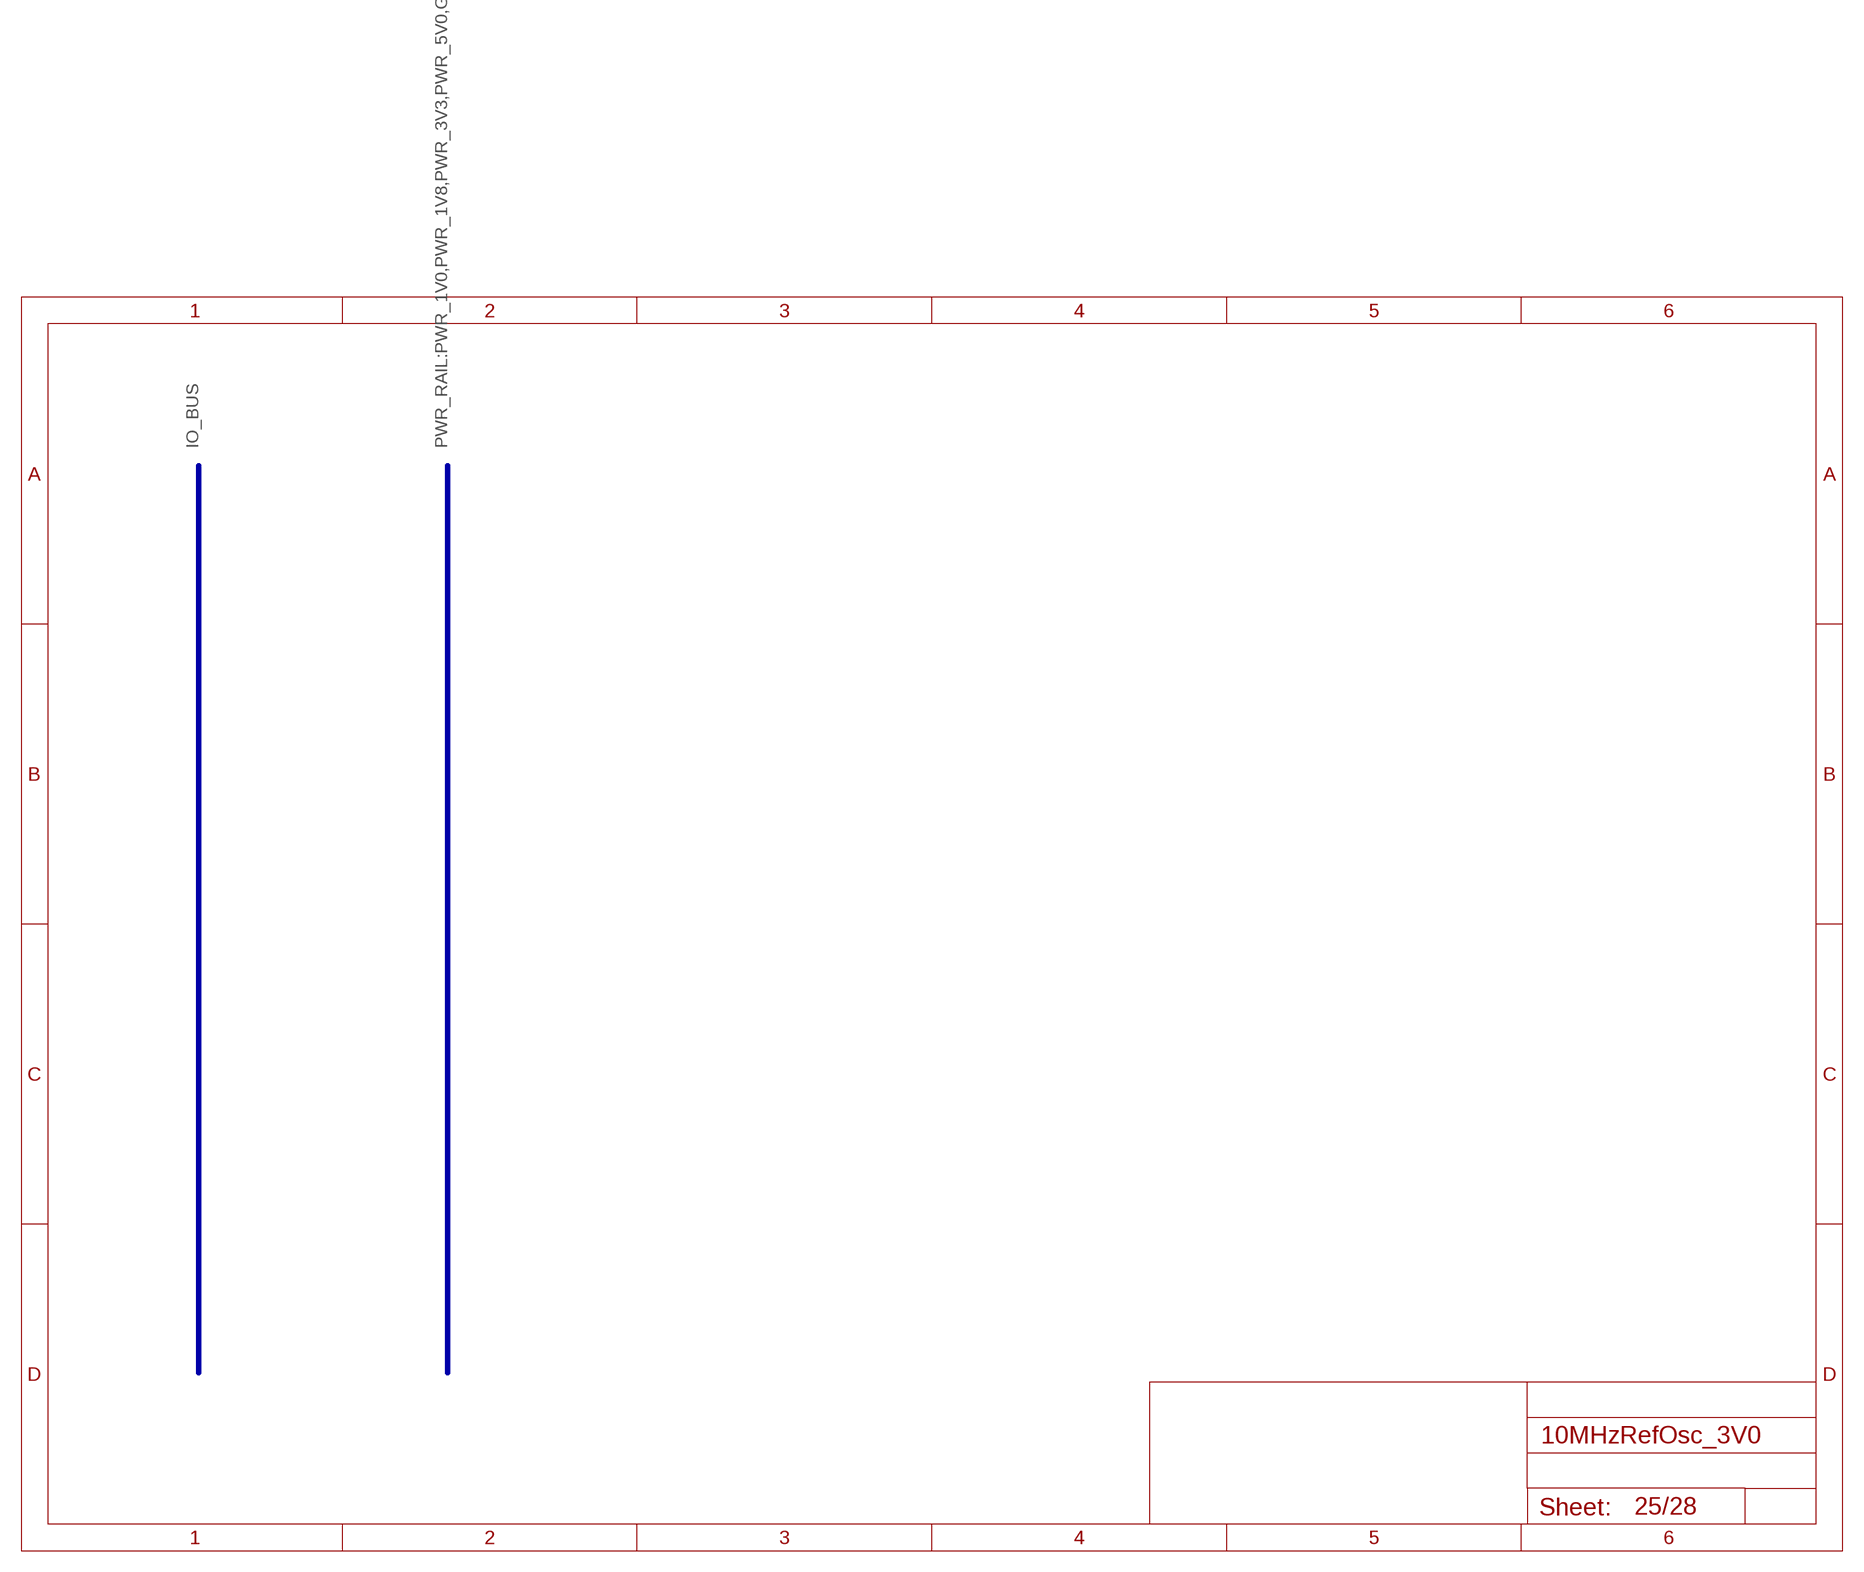
[diagram p24: schematic, sheet 25]
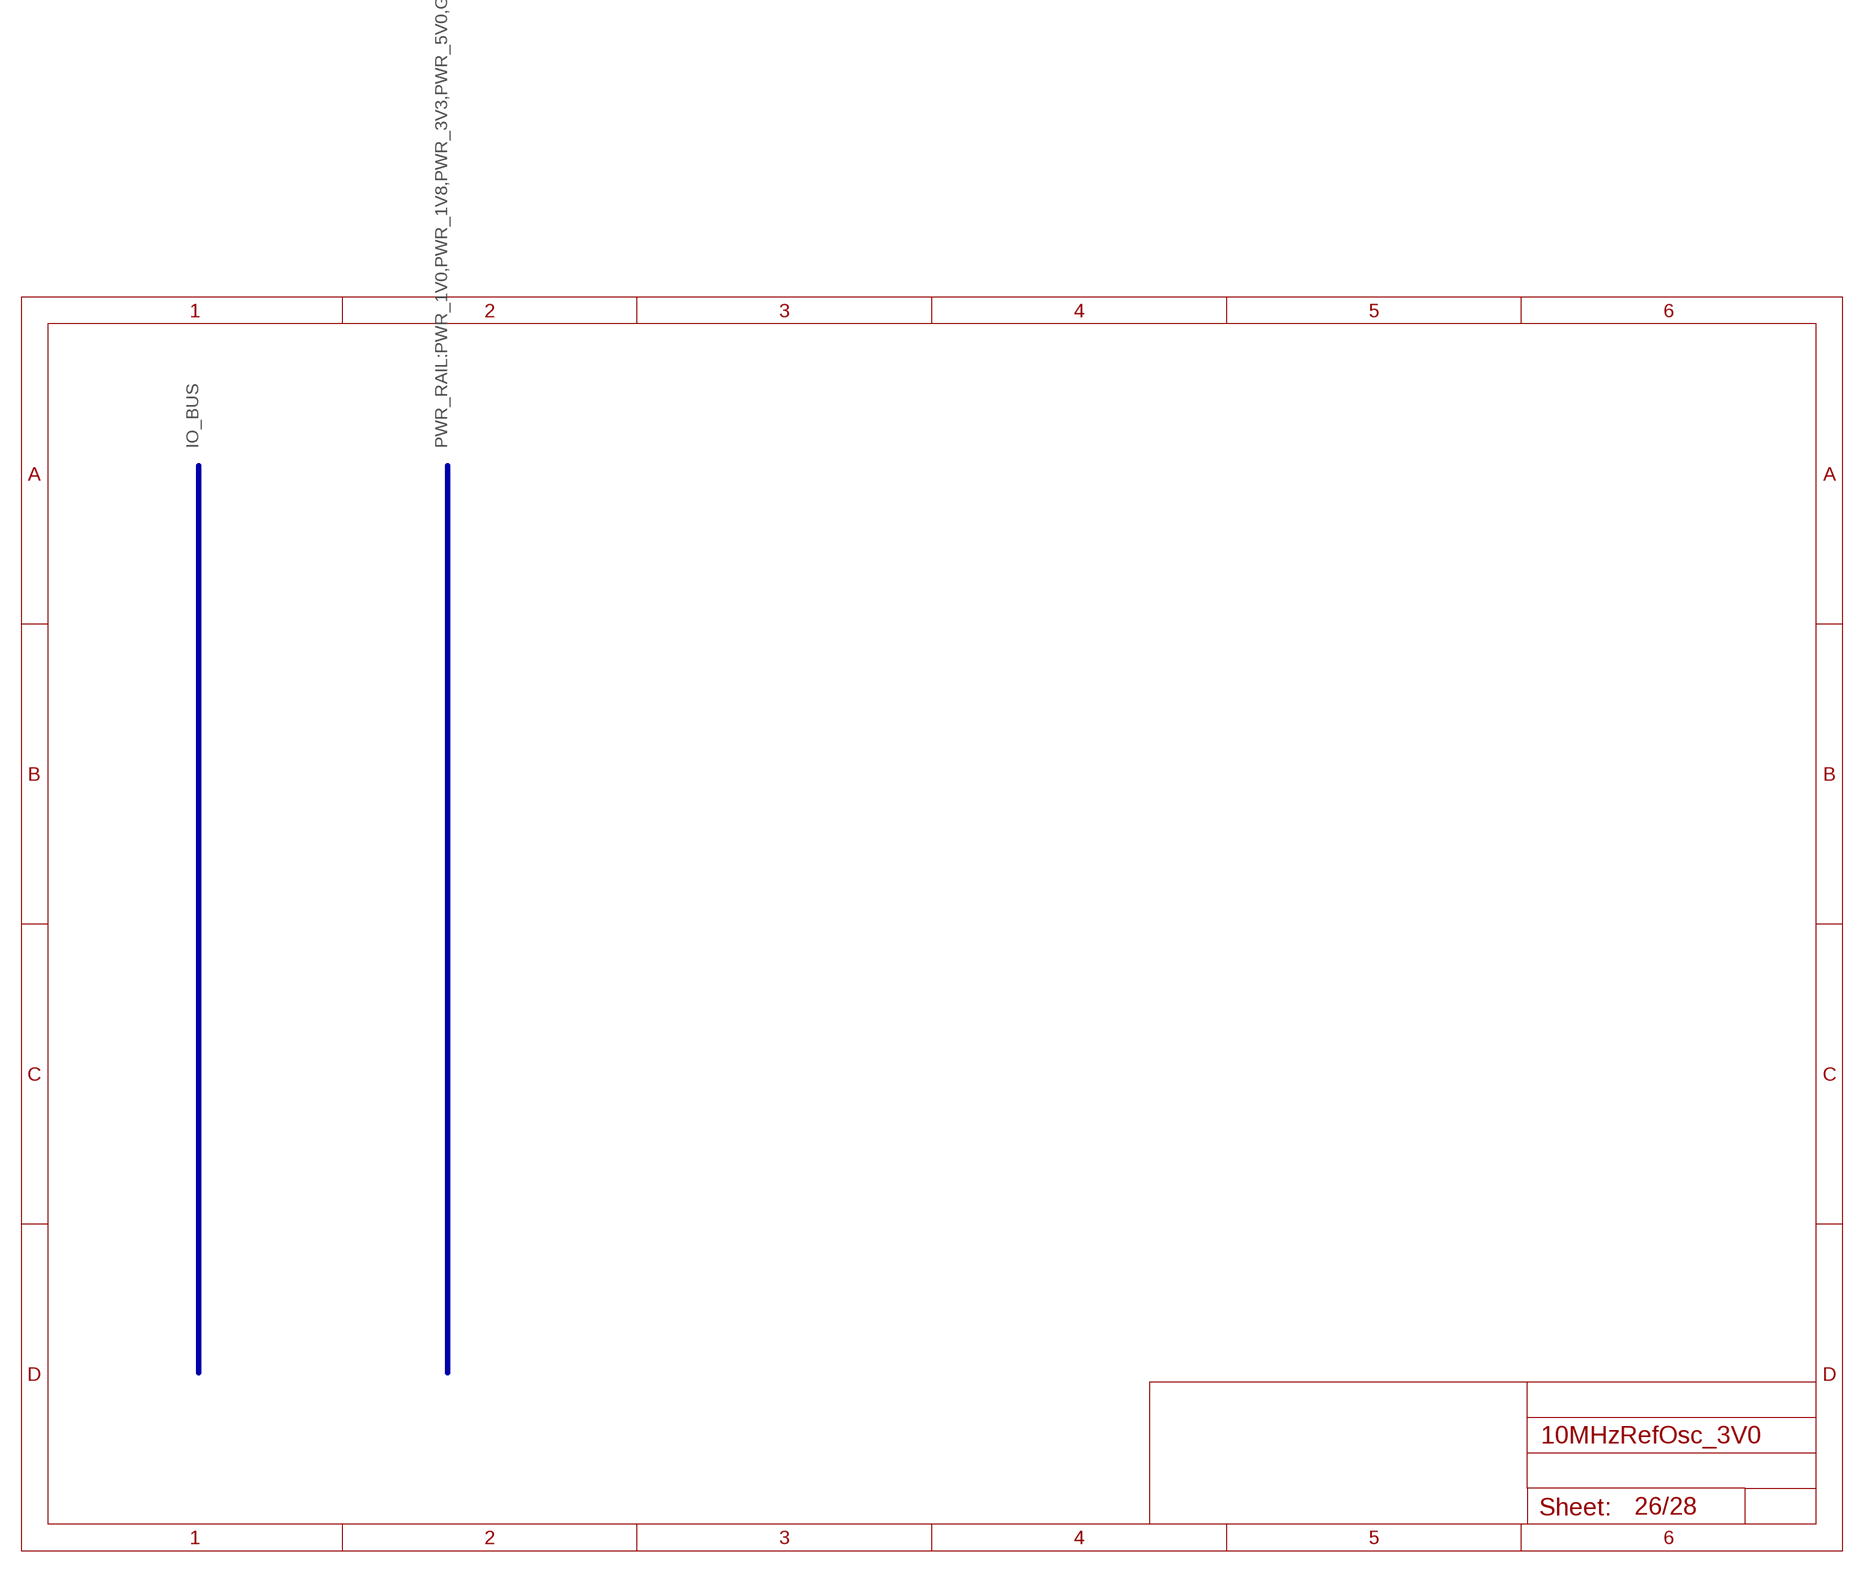
[diagram p25: schematic, sheet 26]
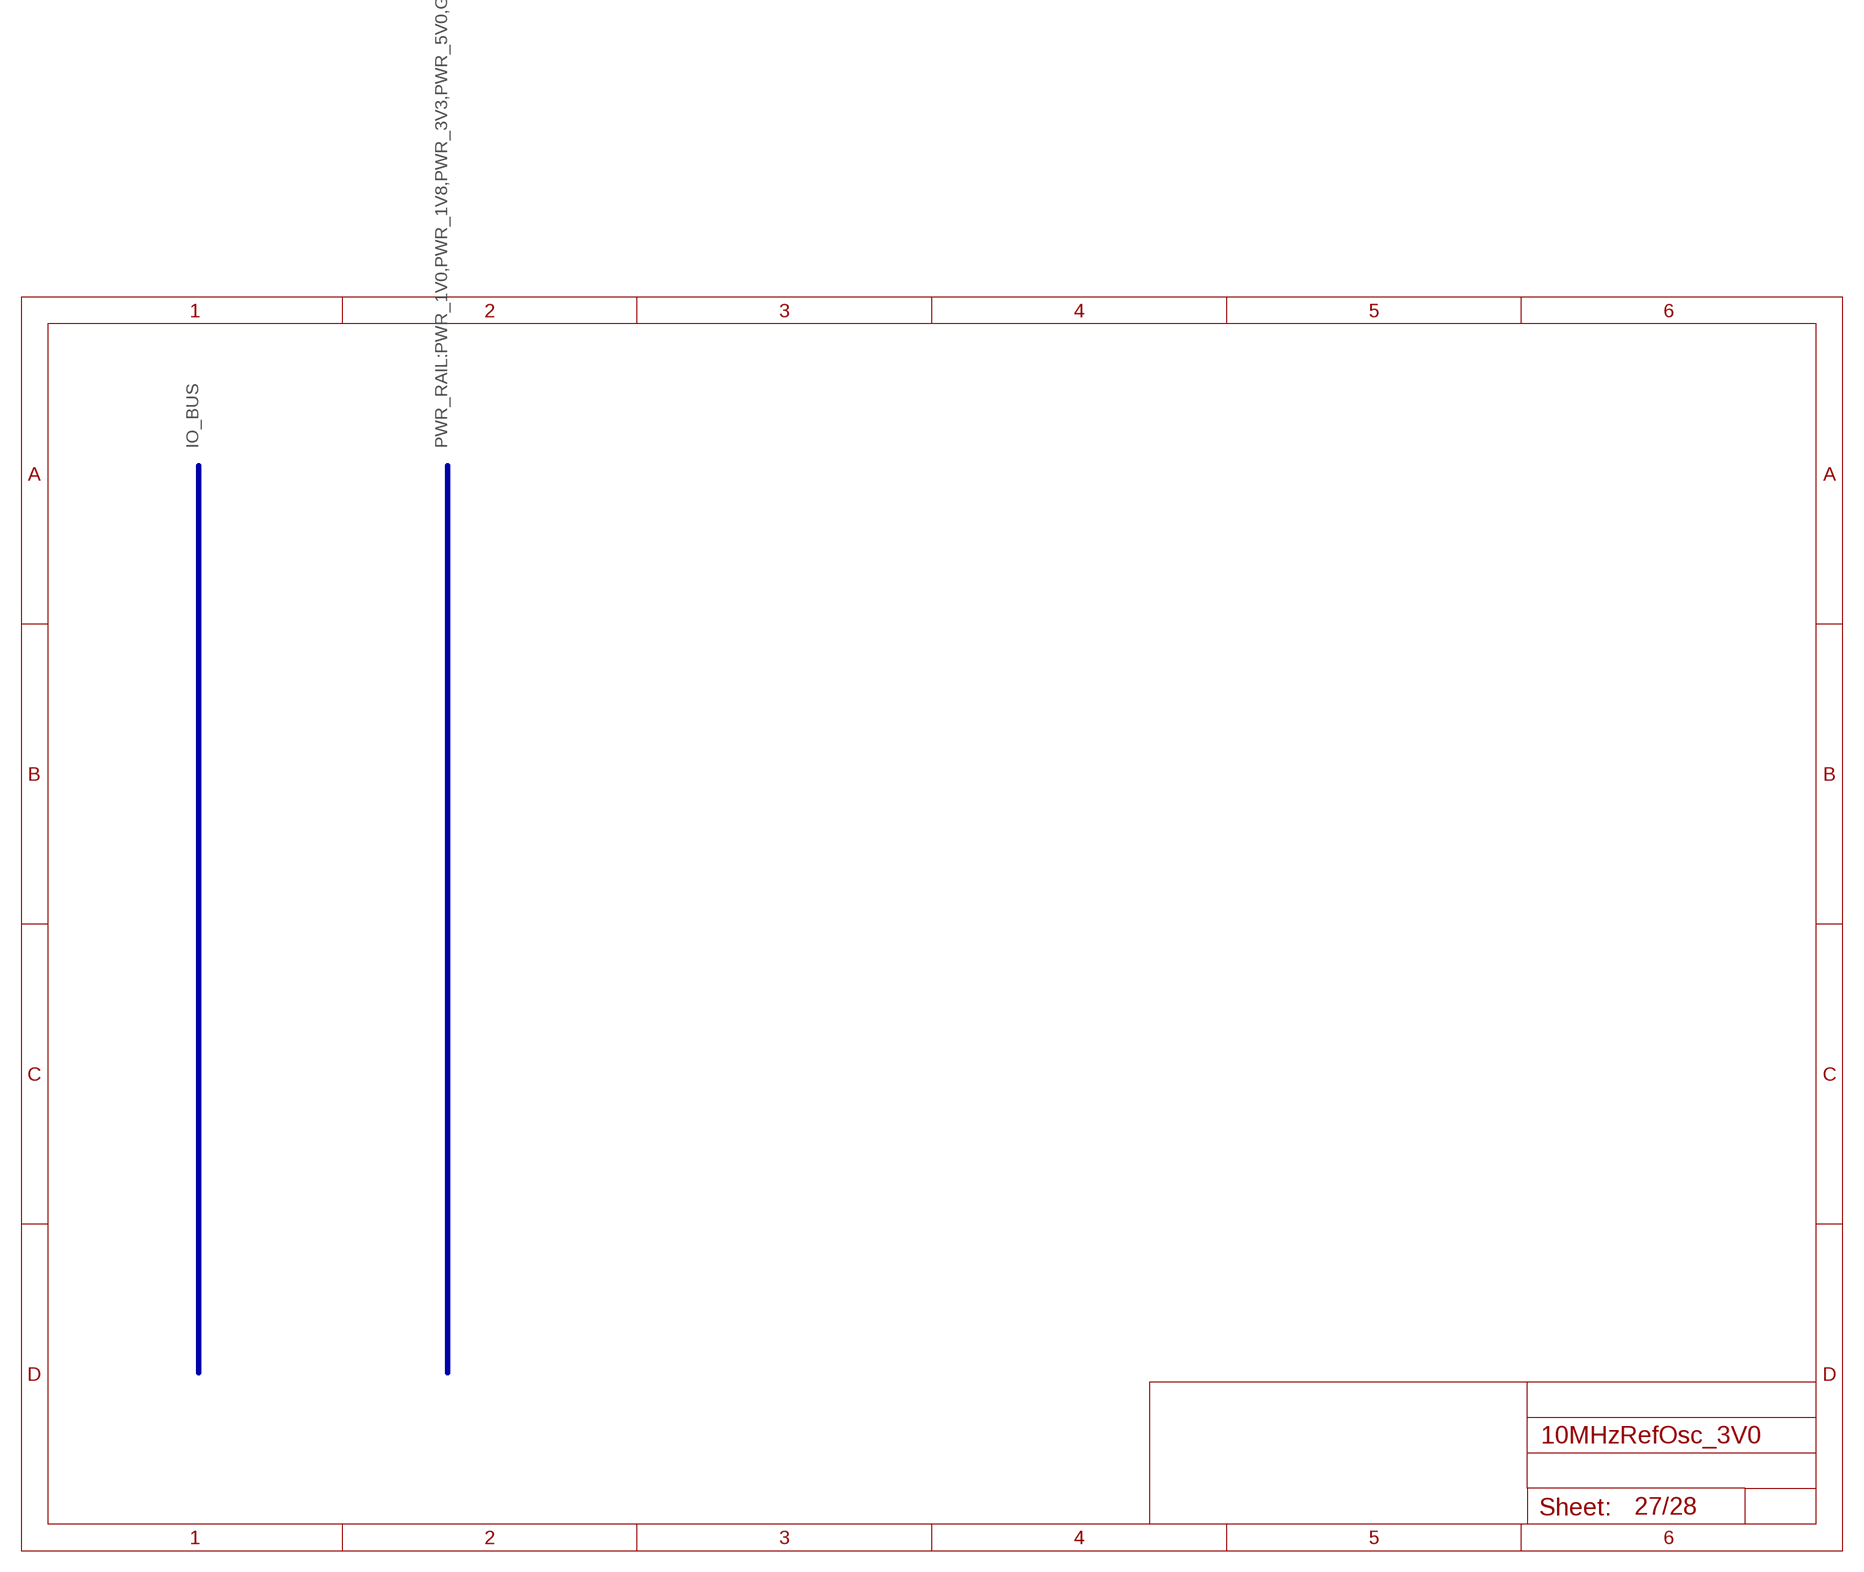
[diagram p26: schematic, sheet 27]
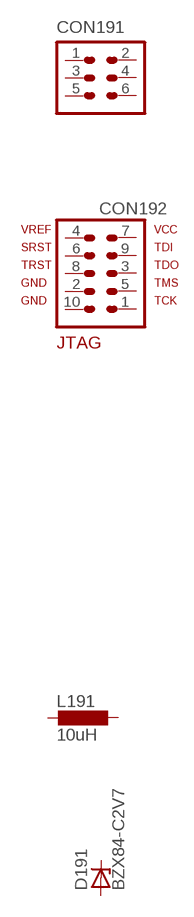
[diagram p27: schematic, sheet 28]

(export (version "E")
  (design (tool "Eeschema 10.0.6"))
  (components
    (comp (ref "C151")
      (value "0.22F")
      (footprint "eagle-import:PANASONIC_C")
      (libsource (lib "eagle-import") (part "CPOL-EUC"))
    )
    (comp (ref "C152")
      (value "100n")
      (footprint "eagle-import:C0805")
      (libsource (lib "eagle-import") (part "C-EUC0805"))
    )
    (comp (ref "CON151")
      (value "HEADER-2X5SMD")
      (footprint "eagle-import:2X5SMD")
      (libsource (lib "eagle-import") (part "HEADER-2X5SMD"))
    )
    (comp (ref "D151")
      (value "CRS08")
      (footprint "eagle-import:SOT23")
      (libsource (lib "eagle-import") (part "ZENER-DIODESOT23"))
    )
    (comp (ref "R151")
      (value "10k")
      (footprint "eagle-import:R0805")
      (libsource (lib "eagle-import") (part "R-EU_R0805"))
    )
    (comp (ref "R152")
      (value "10k")
      (footprint "eagle-import:R0805")
      (libsource (lib "eagle-import") (part "R-EU_R0805"))
    )
    (comp (ref "RP151")
      (value "1206L012WR_0.1A")
      (footprint "eagle-import:M1206")
      (libsource (lib "eagle-import") (part "R-EU_M1206"))
    )
    (comp (ref "U151")
      (value "GLOBALTOP-FIREFLY1-GMM-G3")
      (footprint "eagle-import:GLOBALTOP-FIREFLY1-GMM-G3")
      (libsource (lib "eagle-import") (part "GLOBALTOP-FIREFLY1-GMM-G3"))
    )
    (comp (ref "C031")
      (value "100n")
      (footprint "eagle-import:C0805")
      (libsource (lib "eagle-import") (part "rcl_C-EUC0805"))
    )
    (comp (ref "D031")
      (value "BZX84-C3V0")
      (footprint "eagle-import:TO236")
      (libsource (lib "eagle-import") (part "BZX84CSMD"))
    )
    (comp (ref "R031")
      (value "56")
      (footprint "eagle-import:R0805")
      (libsource (lib "eagle-import") (part "R-EU_R0805"))
    )
    (comp (ref "U031")
      (value "CFPT-141")
      (footprint "eagle-import:CFPT-141")
      (fields (field (name "MF") "IQD-FREQUENCY-PRODUCTS") (field (name "MPN") "LFTVXO022175"))
      (libsource (lib "eagle-import") (part "CFPT-141"))
    )
    (comp (ref "R021")
      (value "0")
      (footprint "eagle-import:R0805")
      (libsource (lib "eagle-import") (part "R-EU_R0805"))
    )
    (comp (ref "C141")
      (value "47uF")
      (footprint "eagle-import:PANASONIC_C")
      (libsource (lib "eagle-import") (part "CPOL-EUC"))
    )
    (comp (ref "C142")
      (value "100n")
      (footprint "eagle-import:C0805")
      (libsource (lib "eagle-import") (part "rcl_C-EUC0805"))
    )
    (comp (ref "CON141")
      (value "TYCO-AMP_USBUSB-B_SMT")
      (footprint "eagle-import:TYCO-AMP_USB-B_SMT")
      (fields (field (name "MF") "TYCO-AMP") (field (name "MPN") "1734346"))
      (libsource (lib "eagle-import") (part "TYCO-AMP_USBUSB-B_SMT"))
    )
    (comp (ref "D141")
      (value "BZX84-C3V6")
      (footprint "eagle-import:TO236")
      (libsource (lib "eagle-import") (part "BZX84CSMD"))
    )
    (comp (ref "D142")
      (value "BZX84-C3V6")
      (footprint "eagle-import:TO236")
      (libsource (lib "eagle-import") (part "BZX84CSMD"))
    )
    (comp (ref "R141")
      (value "68")
      (footprint "eagle-import:R0805")
      (libsource (lib "eagle-import") (part "R-EU_R0805"))
    )
    (comp (ref "R142")
      (value "68")
      (footprint "eagle-import:R0805")
      (libsource (lib "eagle-import") (part "R-EU_R0805"))
    )
    (comp (ref "R143")
      (value "1M")
      (footprint "eagle-import:R0805")
      (libsource (lib "eagle-import") (part "R-EU_R0805"))
    )
    (comp (ref "R144")
      (value "1.5k")
      (footprint "eagle-import:R0805")
      (libsource (lib "eagle-import") (part "R-EU_R0805"))
    )
    (comp (ref "RP141")
      (value "1206L025YR_0.5A")
      (footprint "eagle-import:M1206")
      (libsource (lib "eagle-import") (part "R-EU_M1206"))
    )
    (comp (ref "C051")
      (value "100uF")
      (footprint "eagle-import:C1206")
      (libsource (lib "eagle-import") (part "rcl_C-EUC1206"))
    )
    (comp (ref "C052")
      (value "4.7uF")
      (footprint "eagle-import:C0402")
      (libsource (lib "eagle-import") (part "rcl_C-EUC0402"))
    )
    (comp (ref "C053")
      (value "4.7uF")
      (footprint "eagle-import:C0402")
      (libsource (lib "eagle-import") (part "rcl_C-EUC0402"))
    )
    (comp (ref "C054")
      (value "0.47uF")
      (footprint "eagle-import:C0402")
      (libsource (lib "eagle-import") (part "rcl_C-EUC0402"))
    )
    (comp (ref "C055")
      (value "0.47uF")
      (footprint "eagle-import:C0402")
      (libsource (lib "eagle-import") (part "rcl_C-EUC0402"))
    )
    (comp (ref "C056")
      (value "0.47uF")
      (footprint "eagle-import:C0402")
      (libsource (lib "eagle-import") (part "rcl_C-EUC0402"))
    )
    (comp (ref "C057")
      (value "0.47uF")
      (footprint "eagle-import:C0402")
      (libsource (lib "eagle-import") (part "rcl_C-EUC0402"))
    )
    (comp (ref "R051")
      (value "0")
      (footprint "eagle-import:R0402")
      (libsource (lib "eagle-import") (part "R-EU_R0402"))
    )
    (comp (ref "U1")
      (value "XC7A35TFTG256")
      (footprint "eagle-import:FTG256_0MM4")
      (libsource (lib "eagle-import") (part "XC7A35TFTG256"))
    )
    (comp (ref "C1001")
      (value "100uF")
      (footprint "eagle-import:C1206")
      (libsource (lib "eagle-import") (part "rcl_C-EUC1206"))
    )
    (comp (ref "C1002")
      (value "4.7uF")
      (footprint "eagle-import:C0402")
      (libsource (lib "eagle-import") (part "rcl_C-EUC0402"))
    )
    (comp (ref "C1003")
      (value "4.7uF")
      (footprint "eagle-import:C0402")
      (libsource (lib "eagle-import") (part "rcl_C-EUC0402"))
    )
    (comp (ref "C1004")
      (value "0.47uF")
      (footprint "eagle-import:C0402")
      (libsource (lib "eagle-import") (part "rcl_C-EUC0402"))
    )
    (comp (ref "C1005")
      (value "0.47uF")
      (footprint "eagle-import:C0402")
      (libsource (lib "eagle-import") (part "rcl_C-EUC0402"))
    )
    (comp (ref "C1006")
      (value "0.47uF")
      (footprint "eagle-import:C0402")
      (libsource (lib "eagle-import") (part "rcl_C-EUC0402"))
    )
    (comp (ref "C1011")
      (value "47uF")
      (footprint "eagle-import:C0805")
      (libsource (lib "eagle-import") (part "rcl_C-EUC0805"))
    )
    (comp (ref "C1012")
      (value "0.47uF")
      (footprint "eagle-import:C0402")
      (libsource (lib "eagle-import") (part "rcl_C-EUC0402"))
    )
    (comp (ref "C1021")
      (value "47uF")
      (footprint "eagle-import:C0805")
      (libsource (lib "eagle-import") (part "rcl_C-EUC0805"))
    )
    (comp (ref "C1022")
      (value "4.7uF")
      (footprint "eagle-import:C0402")
      (libsource (lib "eagle-import") (part "rcl_C-EUC0402"))
    )
    (comp (ref "C1023")
      (value "4.7uF")
      (footprint "eagle-import:C0402")
      (libsource (lib "eagle-import") (part "rcl_C-EUC0402"))
    )
    (comp (ref "C1024")
      (value "0.47uF")
      (footprint "eagle-import:C0402")
      (libsource (lib "eagle-import") (part "rcl_C-EUC0402"))
    )
    (comp (ref "C1025")
      (value "0.47uF")
      (footprint "eagle-import:C0402")
      (libsource (lib "eagle-import") (part "rcl_C-EUC0402"))
    )
    (comp (ref "C1026")
      (value "0.47uF")
      (footprint "eagle-import:C0402")
      (libsource (lib "eagle-import") (part "rcl_C-EUC0402"))
    )
    (comp (ref "R101")
      (value "0")
      (footprint "eagle-import:R0402")
      (libsource (lib "eagle-import") (part "R-EU_R0402"))
    )
    (comp (ref "R102")
      (value "0")
      (footprint "eagle-import:R0402")
      (libsource (lib "eagle-import") (part "R-EU_R0402"))
    )
    (comp (ref "R103")
      (value "0")
      (footprint "eagle-import:R0402")
      (libsource (lib "eagle-import") (part "R-EU_R0402"))
    )
    (comp (ref "R104")
      (value "0")
      (footprint "eagle-import:R0402")
      (libsource (lib "eagle-import") (part "R-EU_R0402"))
    )
    (comp (ref "R105")
      (value "0")
      (footprint "eagle-import:R0402")
      (libsource (lib "eagle-import") (part "R-EU_R0402"))
    )
    (comp (ref "C091")
      (value "4.7uF")
      (footprint "eagle-import:C0402")
      (libsource (lib "eagle-import") (part "rcl_C-EUC0402"))
    )
    (comp (ref "C092")
      (value "0.47uF")
      (footprint "eagle-import:C0402")
      (libsource (lib "eagle-import") (part "rcl_C-EUC0402"))
    )
    (comp (ref "R091")
      (value "0")
      (footprint "eagle-import:R0402")
      (libsource (lib "eagle-import") (part "R-EU_R0402"))
    )
    (comp (ref "C062")
      (value "4.7uF")
      (footprint "eagle-import:C0402")
      (libsource (lib "eagle-import") (part "rcl_C-EUC0402"))
    )
    (comp (ref "C063")
      (value "4.7uF")
      (footprint "eagle-import:C0402")
      (libsource (lib "eagle-import") (part "rcl_C-EUC0402"))
    )
    (comp (ref "C064")
      (value "0.47uF")
      (footprint "eagle-import:C0402")
      (libsource (lib "eagle-import") (part "rcl_C-EUC0402"))
    )
    (comp (ref "C065")
      (value "0.47uF")
      (footprint "eagle-import:C0402")
      (libsource (lib "eagle-import") (part "rcl_C-EUC0402"))
    )
    (comp (ref "C066")
      (value "0.47uF")
      (footprint "eagle-import:C0402")
      (libsource (lib "eagle-import") (part "rcl_C-EUC0402"))
    )
    (comp (ref "C067")
      (value "0.47uF")
      (footprint "eagle-import:C0402")
      (libsource (lib "eagle-import") (part "rcl_C-EUC0402"))
    )
    (comp (ref "R061")
      (value "0")
      (footprint "eagle-import:R0402")
      (libsource (lib "eagle-import") (part "R-EU_R0402"))
    )
    (comp (ref "C041")
      (value "47uF")
      (footprint "eagle-import:C0805")
      (libsource (lib "eagle-import") (part "rcl_C-EUC0805"))
    )
    (comp (ref "R10")
      (value "51")
      (footprint "eagle-import:R0805")
      (libsource (lib "eagle-import") (part "R-EU_R0805"))
    )
    (comp (ref "R041")
      (value "0")
      (footprint "eagle-import:R0402")
      (libsource (lib "eagle-import") (part "R-EU_R0402"))
    )
    (comp (ref "R042")
      (value "0")
      (footprint "eagle-import:R0402")
      (libsource (lib "eagle-import") (part "R-EU_R0402"))
    )
    (comp (ref "C071")
      (value "4.7uF")
      (footprint "eagle-import:C0402")
      (libsource (lib "eagle-import") (part "rcl_C-EUC0402"))
    )
    (comp (ref "C072")
      (value "0.47uF")
      (footprint "eagle-import:C0402")
      (libsource (lib "eagle-import") (part "rcl_C-EUC0402"))
    )
    (comp (ref "C073")
      (value "0.47uF")
      (footprint "eagle-import:C0402")
      (libsource (lib "eagle-import") (part "rcl_C-EUC0402"))
    )
    (comp (ref "R071")
      (value "0")
      (footprint "eagle-import:R0402")
      (libsource (lib "eagle-import") (part "R-EU_R0402"))
    )
    (comp (ref "C082")
      (value "4.7uF")
      (footprint "eagle-import:C0402")
      (libsource (lib "eagle-import") (part "rcl_C-EUC0402"))
    )
    (comp (ref "C083")
      (value "4.7uF")
      (footprint "eagle-import:C0402")
      (libsource (lib "eagle-import") (part "rcl_C-EUC0402"))
    )
    (comp (ref "C084")
      (value "0.47uF")
      (footprint "eagle-import:C0402")
      (libsource (lib "eagle-import") (part "rcl_C-EUC0402"))
    )
    (comp (ref "C085")
      (value "0.47uF")
      (footprint "eagle-import:C0402")
      (libsource (lib "eagle-import") (part "rcl_C-EUC0402"))
    )
    (comp (ref "C086")
      (value "0.47uF")
      (footprint "eagle-import:C0402")
      (libsource (lib "eagle-import") (part "rcl_C-EUC0402"))
    )
    (comp (ref "C087")
      (value "0.47uF")
      (footprint "eagle-import:C0402")
      (libsource (lib "eagle-import") (part "rcl_C-EUC0402"))
    )
    (comp (ref "R081")
      (value "0")
      (footprint "eagle-import:R0402")
      (libsource (lib "eagle-import") (part "R-EU_R0402"))
    )
    (comp (ref "H191")
      (value "MOUNT-PAD-ROUND2.8")
      (footprint "eagle-import:2,8-PAD")
      (libsource (lib "eagle-import") (part "MOUNT-PAD-ROUND2.8"))
    )
    (comp (ref "H192")
      (value "MOUNT-PAD-ROUND2.8")
      (footprint "eagle-import:2,8-PAD")
      (libsource (lib "eagle-import") (part "MOUNT-PAD-ROUND2.8"))
    )
    (comp (ref "H193")
      (value "MOUNT-PAD-ROUND2.8")
      (footprint "eagle-import:2,8-PAD")
      (libsource (lib "eagle-import") (part "MOUNT-PAD-ROUND2.8"))
    )
    (comp (ref "H194")
      (value "MOUNT-PAD-ROUND2.8")
      (footprint "eagle-import:2,8-PAD")
      (libsource (lib "eagle-import") (part "MOUNT-PAD-ROUND2.8"))
    )
    (comp (ref "CON181")
      (value "MCX-J-P-X-RA-SM1")
      (footprint "eagle-import:MCX-J-P-X-RA-SM1")
      (libsource (lib "eagle-import") (part "MCX-J-P-X-RA-SM1"))
    )
    (comp (ref "CON182")
      (value "SD-73100-0105")
      (footprint "eagle-import:MOLEX_BNC-JACK-50R_SD-73100-0105")
      (fields (field (name "MF") "MOLEX"))
      (libsource (lib "eagle-import") (part "MOLEX_BNC-JACK-50R_SD-73100-0105"))
    )
    (comp (ref "CON183")
      (value "MCX-J-P-X-RA-SM1")
      (footprint "eagle-import:MCX-J-P-X-RA-SM1")
      (libsource (lib "eagle-import") (part "MCX-J-P-X-RA-SM1"))
    )
    (comp (ref "CON184")
      (value "MCX-J-P-X-RA-SM1")
      (footprint "eagle-import:MCX-J-P-X-RA-SM1")
      (libsource (lib "eagle-import") (part "MCX-J-P-X-RA-SM1"))
    )
    (comp (ref "CON185")
      (value "MCX-J-P-X-RA-SM1")
      (footprint "eagle-import:MCX-J-P-X-RA-SM1")
      (libsource (lib "eagle-import") (part "MCX-J-P-X-RA-SM1"))
    )
    (comp (ref "CON186")
      (value "MCX-J-P-X-RA-SM1")
      (footprint "eagle-import:MCX-J-P-X-RA-SM1")
      (libsource (lib "eagle-import") (part "MCX-J-P-X-RA-SM1"))
    )
    (comp (ref "CON191")
      (value "HEADER-2X3SMD")
      (footprint "eagle-import:2X03SMD")
      (libsource (lib "eagle-import") (part "HEADER-2X3SMD"))
    )
    (comp (ref "CON192")
      (value "AVR-JTAG-10SMD")
      (footprint "eagle-import:2X5SMD")
      (libsource (lib "eagle-import") (part "AVR-JTAG-10SMD"))
    )
    (comp (ref "D191")
      (value "BZX84-C2V7")
      (footprint "eagle-import:TO236")
      (libsource (lib "eagle-import") (part "BZX84CSMD"))
    )
    (comp (ref "L191")
      (value "10uH")
      (footprint "eagle-import:L1812")
      (libsource (lib "eagle-import") (part "L-EUL1812"))
    )
  )
  (nets
    (net (code "114") (name "AGND") (class "Default")
      (node (ref "R021") (pin "1") (pinfunction "1_1") (pintype "passive"))
      (node (ref "U1") (pin "G7") (pinfunction "GNDADC_0_G7") (pintype "bidirectional"))
      (node (ref "U1") (pin "H7") (pinfunction "VREFN_0_H7") (pintype "bidirectional"))
      (node (ref "U1") (pin "J7") (pinfunction "VN_0_J7") (pintype "bidirectional"))
    )
    (net (code "115") (name "FPGA_ADC_VP_0") (class "Default")
      (node (ref "U1") (pin "H8") (pinfunction "VP_0_H8") (pintype "bidirectional"))
    )
    (net (code "116") (name "FPGA_VCCO_35") (class "Default")
      (node (ref "C082") (pin "1") (pinfunction "1_1") (pintype "passive"))
      (node (ref "C083") (pin "1") (pinfunction "1_1") (pintype "passive"))
      (node (ref "C084") (pin "1") (pinfunction "1_1") (pintype "passive"))
      (node (ref "C085") (pin "1") (pinfunction "1_1") (pintype "passive"))
      (node (ref "C086") (pin "1") (pinfunction "1_1") (pintype "passive"))
      (node (ref "C087") (pin "1") (pinfunction "1_1") (pintype "passive"))
      (node (ref "R081") (pin "1") (pinfunction "1_1") (pintype "passive"))
      (node (ref "U1") (pin "A6") (pinfunction "VCCO_35_A6") (pintype "input"))
      (node (ref "U1") (pin "B3") (pinfunction "VCCO_35_B3") (pintype "input"))
      (node (ref "U1") (pin "D7") (pinfunction "VCCO_35_D7") (pintype "input"))
      (node (ref "U1") (pin "E4") (pinfunction "VCCO_35_E4") (pintype "input"))
      (node (ref "U1") (pin "F1") (pinfunction "VCCO_35_F1") (pintype "input"))
      (node (ref "U1") (pin "J2") (pinfunction "VCCO_35_J2") (pintype "input"))
    )
    (net (code "117") (name "GND") (class "Default")
      (node (ref "C031") (pin "2") (pinfunction "2_2") (pintype "passive"))
      (node (ref "C041") (pin "2") (pinfunction "2_2") (pintype "passive"))
      (node (ref "C051") (pin "2") (pinfunction "2_2") (pintype "passive"))
      (node (ref "C052") (pin "2") (pinfunction "2_2") (pintype "passive"))
      (node (ref "C053") (pin "2") (pinfunction "2_2") (pintype "passive"))
      (node (ref "C054") (pin "2") (pinfunction "2_2") (pintype "passive"))
      (node (ref "C055") (pin "2") (pinfunction "2_2") (pintype "passive"))
      (node (ref "C056") (pin "2") (pinfunction "2_2") (pintype "passive"))
      (node (ref "C057") (pin "2") (pinfunction "2_2") (pintype "passive"))
      (node (ref "C062") (pin "2") (pinfunction "2_2") (pintype "passive"))
      (node (ref "C063") (pin "2") (pinfunction "2_2") (pintype "passive"))
      (node (ref "C064") (pin "2") (pinfunction "2_2") (pintype "passive"))
      (node (ref "C065") (pin "2") (pinfunction "2_2") (pintype "passive"))
      (node (ref "C066") (pin "2") (pinfunction "2_2") (pintype "passive"))
      (node (ref "C067") (pin "2") (pinfunction "2_2") (pintype "passive"))
      (node (ref "C071") (pin "2") (pinfunction "2_2") (pintype "passive"))
      (node (ref "C072") (pin "2") (pinfunction "2_2") (pintype "passive"))
      (node (ref "C073") (pin "2") (pinfunction "2_2") (pintype "passive"))
      (node (ref "C082") (pin "2") (pinfunction "2_2") (pintype "passive"))
      (node (ref "C083") (pin "2") (pinfunction "2_2") (pintype "passive"))
      (node (ref "C084") (pin "2") (pinfunction "2_2") (pintype "passive"))
      (node (ref "C085") (pin "2") (pinfunction "2_2") (pintype "passive"))
      (node (ref "C086") (pin "2") (pinfunction "2_2") (pintype "passive"))
      (node (ref "C087") (pin "2") (pinfunction "2_2") (pintype "passive"))
      (node (ref "C091") (pin "2") (pinfunction "2_2") (pintype "passive"))
      (node (ref "C092") (pin "2") (pinfunction "2_2") (pintype "passive"))
      (node (ref "C1001") (pin "2") (pinfunction "2_2") (pintype "passive"))
      (node (ref "C1002") (pin "2") (pinfunction "2_2") (pintype "passive"))
      (node (ref "C1003") (pin "2") (pinfunction "2_2") (pintype "passive"))
      (node (ref "C1004") (pin "2") (pinfunction "2_2") (pintype "passive"))
      (node (ref "C1005") (pin "2") (pinfunction "2_2") (pintype "passive"))
      (node (ref "C1006") (pin "2") (pinfunction "2_2") (pintype "passive"))
      (node (ref "C1011") (pin "2") (pinfunction "2_2") (pintype "passive"))
      (node (ref "C1012") (pin "2") (pinfunction "2_2") (pintype "passive"))
      (node (ref "C1021") (pin "2") (pinfunction "2_2") (pintype "passive"))
      (node (ref "C1022") (pin "2") (pinfunction "2_2") (pintype "passive"))
      (node (ref "C1023") (pin "2") (pinfunction "2_2") (pintype "passive"))
      (node (ref "C1024") (pin "2") (pinfunction "2_2") (pintype "passive"))
      (node (ref "C1025") (pin "2") (pinfunction "2_2") (pintype "passive"))
      (node (ref "C1026") (pin "2") (pinfunction "2_2") (pintype "passive"))
      (node (ref "C141") (pin "-") (pinfunction "-_-") (pintype "passive"))
      (node (ref "C142") (pin "2") (pinfunction "2_2") (pintype "passive"))
      (node (ref "C151") (pin "-") (pinfunction "-_-") (pintype "passive"))
      (node (ref "C152") (pin "2") (pinfunction "2_2") (pintype "passive"))
      (node (ref "CON141") (pin "4") (pinfunction "GND_4") (pintype "bidirectional"))
      (node (ref "CON151") (pin "1") (pinfunction "1_1") (pintype "passive"))
      (node (ref "CON151") (pin "10") (pinfunction "10_10") (pintype "passive"))
      (node (ref "CON151") (pin "9") (pinfunction "9_9") (pintype "passive"))
      (node (ref "CON181") (pin "2") (pinfunction "2_2") (pintype "passive"))
      (node (ref "CON181") (pin "3") (pinfunction "3_3") (pintype "passive"))
      (node (ref "CON181") (pin "4") (pinfunction "4_4") (pintype "passive"))
      (node (ref "CON181") (pin "5") (pinfunction "5_5") (pintype "passive"))
      (node (ref "CON182") (pin "2") (pinfunction "2_2") (pintype "passive"))
      (node (ref "CON182") (pin "3") (pinfunction "3_3") (pintype "passive"))
      (node (ref "CON183") (pin "2") (pinfunction "2_2") (pintype "passive"))
      (node (ref "CON183") (pin "3") (pinfunction "3_3") (pintype "passive"))
      (node (ref "CON183") (pin "4") (pinfunction "4_4") (pintype "passive"))
      (node (ref "CON183") (pin "5") (pinfunction "5_5") (pintype "passive"))
      (node (ref "CON184") (pin "2") (pinfunction "2_2") (pintype "passive"))
      (node (ref "CON184") (pin "3") (pinfunction "3_3") (pintype "passive"))
      (node (ref "CON184") (pin "4") (pinfunction "4_4") (pintype "passive"))
      (node (ref "CON184") (pin "5") (pinfunction "5_5") (pintype "passive"))
      (node (ref "CON185") (pin "2") (pinfunction "2_2") (pintype "passive"))
      (node (ref "CON185") (pin "3") (pinfunction "3_3") (pintype "passive"))
      (node (ref "CON185") (pin "4") (pinfunction "4_4") (pintype "passive"))
      (node (ref "CON185") (pin "5") (pinfunction "5_5") (pintype "passive"))
      (node (ref "CON186") (pin "2") (pinfunction "2_2") (pintype "passive"))
      (node (ref "CON186") (pin "3") (pinfunction "3_3") (pintype "passive"))
      (node (ref "CON186") (pin "4") (pinfunction "4_4") (pintype "passive"))
      (node (ref "CON186") (pin "5") (pinfunction "5_5") (pintype "passive"))
      (node (ref "D031") (pin "A") (pinfunction "A_A") (pintype "passive"))
      (node (ref "D141") (pin "A") (pinfunction "A_A") (pintype "passive"))
      (node (ref "D142") (pin "A") (pinfunction "A_A") (pintype "passive"))
      (node (ref "H191") (pin "B2,8") (pinfunction "MOUNT_B2,8") (pintype "passive"))
      (node (ref "H192") (pin "B2,8") (pinfunction "MOUNT_B2,8") (pintype "passive"))
      (node (ref "H193") (pin "B2,8") (pinfunction "MOUNT_B2,8") (pintype "passive"))
      (node (ref "H194") (pin "B2,8") (pinfunction "MOUNT_B2,8") (pintype "passive"))
      (node (ref "R021") (pin "2") (pinfunction "2_2") (pintype "passive"))
      (node (ref "R104") (pin "2") (pinfunction "2_2") (pintype "passive"))
      (node (ref "R105") (pin "2") (pinfunction "2_2") (pintype "passive"))
      (node (ref "R143") (pin "1") (pinfunction "1_1") (pintype "passive"))
      (node (ref "U031") (pin "2") (pinfunction "GND_2") (pintype "power_in"))
      (node (ref "U1") (pin "A1") (pinfunction "GND_A1") (pintype "power_in"))
      (node (ref "U1") (pin "A11") (pinfunction "GND_A11") (pintype "power_in"))
      (node (ref "U1") (pin "B8") (pinfunction "GND_B8") (pintype "power_in"))
      (node (ref "U1") (pin "C15") (pinfunction "GND_C15") (pintype "power_in"))
      (node (ref "U1") (pin "C5") (pinfunction "GND_C5") (pintype "power_in"))
      (node (ref "U1") (pin "D12") (pinfunction "GND_D12") (pintype "power_in"))
      (node (ref "U1") (pin "D2") (pinfunction "GND_D2") (pintype "power_in"))
      (node (ref "U1") (pin "E9") (pinfunction "GND_E9") (pintype "power_in"))
      (node (ref "U1") (pin "F10") (pinfunction "GND_F10") (pintype "power_in"))
      (node (ref "U1") (pin "F16") (pinfunction "GND_F16") (pintype "power_in"))
      (node (ref "U1") (pin "F6") (pinfunction "GND_F6") (pintype "power_in"))
      (node (ref "U1") (pin "G13") (pinfunction "GND_G13") (pintype "power_in"))
      (node (ref "U1") (pin "G3") (pinfunction "GND_G3") (pintype "power_in"))
      (node (ref "U1") (pin "G9") (pinfunction "GND_G9") (pintype "power_in"))
      (node (ref "U1") (pin "H6") (pinfunction "GND_H6") (pintype "power_in"))
      (node (ref "U1") (pin "J11") (pinfunction "GND_J11") (pintype "power_in"))
      (node (ref "U1") (pin "J9") (pinfunction "GND_J9") (pintype "power_in"))
      (node (ref "U1") (pin "K14") (pinfunction "GND_K14") (pintype "power_in"))
      (node (ref "U1") (pin "K4") (pinfunction "GND_K4") (pintype "power_in"))
      (node (ref "U1") (pin "K6") (pinfunction "GND_K6") (pintype "power_in"))
      (node (ref "U1") (pin "L1") (pinfunction "GND_L1") (pintype "power_in"))
      (node (ref "U1") (pin "L11") (pinfunction "GND_L11") (pintype "power_in"))
      (node (ref "U1") (pin "M8") (pinfunction "GND_M8") (pintype "power_in"))
      (node (ref "U1") (pin "N15") (pinfunction "GND_N15") (pintype "power_in"))
      (node (ref "U1") (pin "N5") (pinfunction "GND_N5") (pintype "power_in"))
      (node (ref "U1") (pin "P12") (pinfunction "GND_P12") (pintype "power_in"))
      (node (ref "U1") (pin "P2") (pinfunction "GND_P2") (pintype "power_in"))
      (node (ref "U1") (pin "R9") (pinfunction "GND_R9") (pintype "power_in"))
      (node (ref "U1") (pin "T16") (pinfunction "GND_T16") (pintype "power_in"))
      (node (ref "U1") (pin "T6") (pinfunction "GND_T6") (pintype "power_in"))
      (node (ref "U151") (pin "10") (pinfunction "GND_10") (pintype "power_in"))
      (node (ref "U151") (pin "15") (pinfunction "GND_15") (pintype "power_in"))
      (node (ref "U151") (pin "2") (pinfunction "GND_2") (pintype "power_in"))
      (node (ref "U151") (pin "4") (pinfunction "GND_4") (pintype "power_in"))
      (node (ref "U151") (pin "8") (pinfunction "GND_8") (pintype "power_in"))
    )
    (net (code "118") (name "GPS_2ND_RX") (class "Default")
      (node (ref "R152") (pin "1") (pinfunction "1_1") (pintype "passive"))
      (node (ref "U151") (pin "6") (pinfunction "RXDB_6") (pintype "input"))
    )
    (net (code "119") (name "GPS_2ND_TX") (class "Default")
      (node (ref "U151") (pin "5") (pinfunction "TXDB_5") (pintype "output"))
    )
    (net (code "120") (name "GPS_3DFIX") (class "Default")
      (node (ref "U151") (pin "13") (pinfunction "3D_FIX_13") (pintype "output"))
    )
    (net (code "121") (name "GPS_ANT") (class "Default")
      (node (ref "CON181") (pin "1") (pinfunction "1_1") (pintype "passive"))
      (node (ref "U151") (pin "1") (pinfunction "ANTENNA_IN_1") (pintype "passive"))
    )
    (net (code "122") (name "GPS_ANT_PWR") (class "Default")
      (node (ref "CON151") (pin "4") (pinfunction "4_4") (pintype "passive"))
      (node (ref "RP151") (pin "1") (pinfunction "1_1") (pintype "passive"))
      (node (ref "U151") (pin "3") (pinfunction "VANT_3") (pintype "power_in"))
    )
    (net (code "123") (name "GPS_NMEA_RX") (class "Default")
      (node (ref "CON151") (pin "5") (pinfunction "5_5") (pintype "passive"))
      (node (ref "U151") (pin "12") (pinfunction "RXDA_12") (pintype "input"))
    )
    (net (code "124") (name "GPS_NMEA_TX") (class "Default")
      (node (ref "CON151") (pin "6") (pinfunction "6_6") (pintype "passive"))
      (node (ref "U151") (pin "11") (pinfunction "TXDA_11") (pintype "output"))
    )
    (net (code "125") (name "GPS_NRESET") (class "Default")
      (node (ref "R151") (pin "1") (pinfunction "1_1") (pintype "passive"))
      (node (ref "U151") (pin "7") (pinfunction "NRESET_7") (pintype "input"))
    )
    (net (code "126") (name "GPS_PPS") (class "Default")
      (node (ref "CON151") (pin "7") (pinfunction "7_7") (pintype "passive"))
      (node (ref "U151") (pin "9") (pinfunction "1PPS_9") (pintype "output"))
    )
    (net (code "127") (name "Net-(C051-Pad1)") (class "Default")
      (node (ref "C051") (pin "1") (pinfunction "1_1") (pintype "passive"))
      (node (ref "C052") (pin "1") (pinfunction "1_1") (pintype "passive"))
      (node (ref "C053") (pin "1") (pinfunction "1_1") (pintype "passive"))
      (node (ref "C054") (pin "1") (pinfunction "1_1") (pintype "passive"))
      (node (ref "C055") (pin "1") (pinfunction "1_1") (pintype "passive"))
      (node (ref "C056") (pin "1") (pinfunction "1_1") (pintype "passive"))
      (node (ref "C057") (pin "1") (pinfunction "1_1") (pintype "passive"))
      (node (ref "R051") (pin "1") (pinfunction "1_1") (pintype "passive"))
      (node (ref "U1") (pin "L16") (pinfunction "VCCO_14_L16") (pintype "input"))
      (node (ref "U1") (pin "M13") (pinfunction "VCCO_14_M13") (pintype "input"))
      (node (ref "U1") (pin "N10") (pinfunction "VCCO_14_N10") (pintype "input"))
      (node (ref "U1") (pin "P7") (pinfunction "VCCO_14_P7") (pintype "input"))
      (node (ref "U1") (pin "R14") (pinfunction "VCCO_14_R14") (pintype "input"))
      (node (ref "U1") (pin "T11") (pinfunction "VCCO_14_T11") (pintype "input"))
    )
    (net (code "128") (name "Net-(C062-Pad1)") (class "Default")
      (node (ref "C062") (pin "1") (pinfunction "1_1") (pintype "passive"))
      (node (ref "C063") (pin "1") (pinfunction "1_1") (pintype "passive"))
      (node (ref "C064") (pin "1") (pinfunction "1_1") (pintype "passive"))
      (node (ref "C065") (pin "1") (pinfunction "1_1") (pintype "passive"))
      (node (ref "C066") (pin "1") (pinfunction "1_1") (pintype "passive"))
      (node (ref "C067") (pin "1") (pinfunction "1_1") (pintype "passive"))
      (node (ref "R061") (pin "1") (pinfunction "1_1") (pintype "passive"))
      (node (ref "U1") (pin "A16") (pinfunction "VCCO_15_A16") (pintype "input"))
      (node (ref "U1") (pin "B13") (pinfunction "VCCO_15_B13") (pintype "input"))
      (node (ref "U1") (pin "C10") (pinfunction "VCCO_15_C10") (pintype "input"))
      (node (ref "U1") (pin "E14") (pinfunction "VCCO_15_E14") (pintype "input"))
      (node (ref "U1") (pin "H15") (pinfunction "VCCO_15_H15") (pintype "input"))
      (node (ref "U1") (pin "J12") (pinfunction "VCCO_15_J12") (pintype "input"))
    )
    (net (code "129") (name "Net-(C071-Pad1)") (class "Default")
      (node (ref "C071") (pin "1") (pinfunction "1_1") (pintype "passive"))
      (node (ref "C072") (pin "1") (pinfunction "1_1") (pintype "passive"))
      (node (ref "C073") (pin "1") (pinfunction "1_1") (pintype "passive"))
      (node (ref "R071") (pin "1") (pinfunction "1_1") (pintype "passive"))
      (node (ref "U1") (pin "M3") (pinfunction "VCCO_34_M3") (pintype "input"))
      (node (ref "U1") (pin "R4") (pinfunction "VCCO_34_R4") (pintype "input"))
      (node (ref "U1") (pin "T1") (pinfunction "VCCO_34_T1") (pintype "input"))
    )
    (net (code "130") (name "Net-(C1001-Pad1)") (class "Default")
      (node (ref "C1001") (pin "1") (pinfunction "1_1") (pintype "passive"))
      (node (ref "C1002") (pin "1") (pinfunction "1_1") (pintype "passive"))
      (node (ref "C1003") (pin "1") (pinfunction "1_1") (pintype "passive"))
      (node (ref "C1004") (pin "1") (pinfunction "1_1") (pintype "passive"))
      (node (ref "C1005") (pin "1") (pinfunction "1_1") (pintype "passive"))
      (node (ref "C1006") (pin "1") (pinfunction "1_1") (pintype "passive"))
      (node (ref "R101") (pin "1") (pinfunction "1_1") (pintype "passive"))
      (node (ref "U1") (pin "F7") (pinfunction "VCCINT_F7") (pintype "input"))
      (node (ref "U1") (pin "F9") (pinfunction "VCCINT_F9") (pintype "input"))
      (node (ref "U1") (pin "G6") (pinfunction "VCCINT_G6") (pintype "input"))
      (node (ref "U1") (pin "H9") (pinfunction "VCCINT_H9") (pintype "input"))
      (node (ref "U1") (pin "J6") (pinfunction "VCCINT_J6") (pintype "input"))
      (node (ref "U1") (pin "K9") (pinfunction "VCCINT_K9") (pintype "input"))
      (node (ref "U1") (pin "L8") (pinfunction "VCCINT_L8") (pintype "input"))
    )
    (net (code "131") (name "Net-(C1011-Pad1)") (class "Default")
      (node (ref "C1011") (pin "1") (pinfunction "1_1") (pintype "passive"))
      (node (ref "C1012") (pin "1") (pinfunction "1_1") (pintype "passive"))
      (node (ref "R102") (pin "1") (pinfunction "1_1") (pintype "passive"))
      (node (ref "U1") (pin "E10") (pinfunction "VCCBRAM_E10") (pintype "input"))
      (node (ref "U1") (pin "F11") (pinfunction "VCCBRAM_F11") (pintype "input"))
    )
    (net (code "132") (name "Net-(C1021-Pad1)") (class "Default")
      (node (ref "C1021") (pin "1") (pinfunction "1_1") (pintype "passive"))
      (node (ref "C1022") (pin "1") (pinfunction "1_1") (pintype "passive"))
      (node (ref "C1023") (pin "1") (pinfunction "1_1") (pintype "passive"))
      (node (ref "C1024") (pin "1") (pinfunction "1_1") (pintype "passive"))
      (node (ref "C1025") (pin "1") (pinfunction "1_1") (pintype "passive"))
      (node (ref "C1026") (pin "1") (pinfunction "1_1") (pintype "passive"))
      (node (ref "R103") (pin "1") (pinfunction "1_1") (pintype "passive"))
      (node (ref "U1") (pin "G10") (pinfunction "VCCAUX_G10") (pintype "input"))
      (node (ref "U1") (pin "J10") (pinfunction "VCCAUX_J10") (pintype "input"))
      (node (ref "U1") (pin "K11") (pinfunction "VCCAUX_K11") (pintype "input"))
      (node (ref "U1") (pin "L10") (pinfunction "VCCAUX_L10") (pintype "input"))
    )
    (net (code "133") (name "Net-(CON141-D+)") (class "Default")
      (node (ref "CON141") (pin "3") (pinfunction "D+_3") (pintype "bidirectional"))
      (node (ref "D141") (pin "C") (pinfunction "C_C") (pintype "passive"))
      (node (ref "R141") (pin "1") (pinfunction "1_1") (pintype "passive"))
      (node (ref "R143") (pin "2") (pinfunction "2_2") (pintype "passive"))
    )
    (net (code "134") (name "Net-(CON141-D-)") (class "Default")
      (node (ref "CON141") (pin "2") (pinfunction "D-_2") (pintype "bidirectional"))
      (node (ref "D142") (pin "C") (pinfunction "C_C") (pintype "passive"))
      (node (ref "R142") (pin "1") (pinfunction "1_1") (pintype "passive"))
      (node (ref "R144") (pin "1") (pinfunction "1_1") (pintype "passive"))
    )
    (net (code "135") (name "Net-(CON141-VBUS)") (class "Default")
      (node (ref "CON141") (pin "1") (pinfunction "VBUS_1") (pintype "bidirectional"))
      (node (ref "RP141") (pin "1") (pinfunction "1_1") (pintype "passive"))
    )
    (net (code "136") (name "Net-(U1A-CFGBVS_0)") (class "Default")
      (node (ref "C041") (pin "1") (pinfunction "1_1") (pintype "passive"))
      (node (ref "R042") (pin "1") (pinfunction "1_1") (pintype "passive"))
      (node (ref "U1") (pin "E7") (pinfunction "CFGBVS_0_E7") (pintype "input"))
      (node (ref "U1") (pin "L6") (pinfunction "VCCO_0_L6") (pintype "input"))
    )
    (net (code "137") (name "Net-(U1A-VCCBATT_0)") (class "Default")
      (node (ref "R041") (pin "1") (pinfunction "1_1") (pintype "passive"))
      (node (ref "U1") (pin "F8") (pinfunction "VCCBATT_0_F8") (pintype "input"))
    )
    (net (code "138") (name "Net-(U1G-DXN_0)") (class "Default")
      (node (ref "R105") (pin "1") (pinfunction "1_1") (pintype "passive"))
      (node (ref "U1") (pin "K7") (pinfunction "DXN_0_K7") (pintype "bidirectional"))
    )
    (net (code "139") (name "Net-(U1G-DXP_0)") (class "Default")
      (node (ref "R104") (pin "1") (pinfunction "1_1") (pintype "passive"))
      (node (ref "U1") (pin "K8") (pinfunction "DXP_0_K8") (pintype "bidirectional"))
    )
    (net (code "140") (name "Net-(U1K-VCCADC_0)") (class "Default")
      (node (ref "C091") (pin "1") (pinfunction "1_1") (pintype "passive"))
      (node (ref "C092") (pin "1") (pinfunction "1_1") (pintype "passive"))
      (node (ref "R091") (pin "1") (pinfunction "1_1") (pintype "passive"))
      (node (ref "U1") (pin "G8") (pinfunction "VCCADC_0_G8") (pintype "input"))
    )
    (net (code "141") (name "PWR_1V0") (class "Default")
      (node (ref "R101") (pin "2") (pinfunction "2_2") (pintype "passive"))
      (node (ref "R102") (pin "2") (pinfunction "2_2") (pintype "passive"))
    )
    (net (code "142") (name "PWR_1V8") (class "Default")
      (node (ref "R041") (pin "2") (pinfunction "2_2") (pintype "passive"))
      (node (ref "R091") (pin "2") (pinfunction "2_2") (pintype "passive"))
      (node (ref "R103") (pin "2") (pinfunction "2_2") (pintype "passive"))
    )
    (net (code "143") (name "PWR_1V25_PREC") (class "Default")
      (node (ref "U1") (pin "J8") (pinfunction "VREFP_0_J8") (pintype "bidirectional"))
    )
    (net (code "144") (name "PWR_3V3") (class "Default")
      (node (ref "C152") (pin "1") (pinfunction "1_1") (pintype "passive"))
      (node (ref "D151") (pin "1") (pinfunction "A_1") (pintype "passive"))
      (node (ref "R031") (pin "1") (pinfunction "1_1") (pintype "passive"))
      (node (ref "R042") (pin "2") (pinfunction "2_2") (pintype "passive"))
      (node (ref "R051") (pin "2") (pinfunction "2_2") (pintype "passive"))
      (node (ref "R061") (pin "2") (pinfunction "2_2") (pintype "passive"))
      (node (ref "R071") (pin "2") (pinfunction "2_2") (pintype "passive"))
      (node (ref "R081") (pin "2") (pinfunction "2_2") (pintype "passive"))
      (node (ref "R151") (pin "2") (pinfunction "2_2") (pintype "passive"))
      (node (ref "R152") (pin "2") (pinfunction "2_2") (pintype "passive"))
      (node (ref "RP151") (pin "2") (pinfunction "2_2") (pintype "passive"))
      (node (ref "U151") (pin "16") (pinfunction "VCC_3V3_16") (pintype "power_in"))
    )
    (net (code "145") (name "PWR_5V0") (class "Default")
      (node (ref "CON151") (pin "3") (pinfunction "3_3") (pintype "passive"))
    )
    (net (code "146") (name "PWR_BACKUP_GPS") (class "Default")
      (node (ref "C151") (pin "+") (pinfunction "+_+") (pintype "passive"))
      (node (ref "CON151") (pin "2") (pinfunction "2_2") (pintype "passive"))
      (node (ref "D151") (pin "3") (pinfunction "C_3") (pintype "passive"))
      (node (ref "U151") (pin "14") (pinfunction "VBACKUP_14") (pintype "power_in"))
    )
    (net (code "147") (name "PWR_VCTCXO_3V0") (class "Default")
      (node (ref "C031") (pin "1") (pinfunction "1_1") (pintype "passive"))
      (node (ref "D031") (pin "C") (pinfunction "C_C") (pintype "passive"))
      (node (ref "R031") (pin "2") (pinfunction "2_2") (pintype "passive"))
      (node (ref "U031") (pin "4") (pinfunction "VCC_3V0_4") (pintype "power_in"))
    )
    (net (code "148") (name "REFC_10MHZ") (class "Default")
      (node (ref "CON182") (pin "1") (pinfunction "1_1") (pintype "passive"))
    )
    (net (code "149") (name "REFC_20MHZ") (class "Default")
      (node (ref "U031") (pin "3") (pinfunction "OUT_3") (pintype "output"))
    )
    (net (code "150") (name "SIG_CH0_I") (class "Default")
      (node (ref "CON183") (pin "1") (pinfunction "1_1") (pintype "passive"))
    )
    (net (code "151") (name "SIG_CH0_Q") (class "Default")
      (node (ref "CON184") (pin "1") (pinfunction "1_1") (pintype "passive"))
    )
    (net (code "152") (name "SIG_CH1_I") (class "Default")
      (node (ref "CON185") (pin "1") (pinfunction "1_1") (pintype "passive"))
    )
    (net (code "153") (name "SIG_CH1_Q") (class "Default")
      (node (ref "CON186") (pin "1") (pinfunction "1_1") (pintype "passive"))
    )
    (net (code "154") (name "USB_5V") (class "Default")
      (node (ref "C141") (pin "+") (pinfunction "+_+") (pintype "passive"))
      (node (ref "C142") (pin "1") (pinfunction "1_1") (pintype "passive"))
      (node (ref "RP141") (pin "2") (pinfunction "2_2") (pintype "passive"))
    )
    (net (code "155") (name "USB_DISC") (class "Default")
      (node (ref "R144") (pin "2") (pinfunction "2_2") (pintype "passive"))
    )
    (net (code "156") (name "USB_D_MNS") (class "Default")
      (node (ref "R142") (pin "2") (pinfunction "2_2") (pintype "passive"))
    )
    (net (code "157") (name "USB_D_PLS") (class "Default")
      (node (ref "R141") (pin "2") (pinfunction "2_2") (pintype "passive"))
    )
    (net (code "158") (name "VCTCXO_VC") (class "Default")
      (node (ref "U031") (pin "1") (pinfunction "VC_1") (pintype "input"))
    )
    (net (code "159") (name "unconnected-(CON151-Pad8)") (class "Default")
      (node (ref "CON151") (pin "8") (pinfunction "8_8") (pintype "passive"))
    )
    (net (code "160") (name "unconnected-(CON191-Pad1)") (class "Default")
      (node (ref "CON191") (pin "1") (pinfunction "1_1") (pintype "passive"))
    )
    (net (code "161") (name "unconnected-(CON191-Pad2)") (class "Default")
      (node (ref "CON191") (pin "2") (pinfunction "2_2") (pintype "passive"))
    )
    (net (code "162") (name "unconnected-(CON191-Pad3)") (class "Default")
      (node (ref "CON191") (pin "3") (pinfunction "3_3") (pintype "passive"))
    )
    (net (code "163") (name "unconnected-(CON191-Pad4)") (class "Default")
      (node (ref "CON191") (pin "4") (pinfunction "4_4") (pintype "passive"))
    )
    (net (code "164") (name "unconnected-(CON191-Pad5)") (class "Default")
      (node (ref "CON191") (pin "5") (pinfunction "5_5") (pintype "passive"))
    )
    (net (code "165") (name "unconnected-(CON191-Pad6)") (class "Default")
      (node (ref "CON191") (pin "6") (pinfunction "6_6") (pintype "passive"))
    )
    (net (code "166") (name "unconnected-(CON192-Pad1)") (class "Default")
      (node (ref "CON192") (pin "1") (pinfunction "1_1") (pintype "passive"))
    )
    (net (code "167") (name "unconnected-(CON192-Pad2)") (class "Default")
      (node (ref "CON192") (pin "2") (pinfunction "2_2") (pintype "passive"))
    )
    (net (code "168") (name "unconnected-(CON192-Pad3)") (class "Default")
      (node (ref "CON192") (pin "3") (pinfunction "3_3") (pintype "passive"))
    )
    (net (code "169") (name "unconnected-(CON192-Pad4)") (class "Default")
      (node (ref "CON192") (pin "4") (pinfunction "4_4") (pintype "passive"))
    )
    (net (code "170") (name "unconnected-(CON192-Pad5)") (class "Default")
      (node (ref "CON192") (pin "5") (pinfunction "5_5") (pintype "passive"))
    )
    (net (code "171") (name "unconnected-(CON192-Pad6)") (class "Default")
      (node (ref "CON192") (pin "6") (pinfunction "6_6") (pintype "passive"))
    )
    (net (code "172") (name "unconnected-(CON192-Pad7)") (class "Default")
      (node (ref "CON192") (pin "7") (pinfunction "7_7") (pintype "passive"))
    )
    (net (code "173") (name "unconnected-(CON192-Pad8)") (class "Default")
      (node (ref "CON192") (pin "8") (pinfunction "8_8") (pintype "passive"))
    )
    (net (code "174") (name "unconnected-(CON192-Pad9)") (class "Default")
      (node (ref "CON192") (pin "9") (pinfunction "9_9") (pintype "passive"))
    )
    (net (code "175") (name "unconnected-(CON192-Pad10)") (class "Default")
      (node (ref "CON192") (pin "10") (pinfunction "10_10") (pintype "passive"))
    )
    (net (code "176") (name "unconnected-(D191-PadA)") (class "Default")
      (node (ref "D191") (pin "A") (pinfunction "A_A") (pintype "passive"))
    )
    (net (code "177") (name "unconnected-(D191-PadC)") (class "Default")
      (node (ref "D191") (pin "C") (pinfunction "C_C") (pintype "passive"))
    )
    (net (code "178") (name "unconnected-(L191-Pad1)") (class "Default")
      (node (ref "L191") (pin "1") (pinfunction "1_1") (pintype "passive"))
    )
    (net (code "179") (name "unconnected-(L191-Pad2)") (class "Default")
      (node (ref "L191") (pin "2") (pinfunction "2_2") (pintype "passive"))
    )
    (net (code "180") (name "unconnected-(R10-Pad1)") (class "Default")
      (node (ref "R10") (pin "1") (pinfunction "1_1") (pintype "passive"))
    )
    (net (code "181") (name "unconnected-(R10-Pad2)") (class "Default")
      (node (ref "R10") (pin "2") (pinfunction "2_2") (pintype "passive"))
    )
    (net (code "182") (name "unconnected-(U1A-CCLK_0-PadE8)") (class "Default")
      (node (ref "U1") (pin "E8") (pinfunction "CCLK_0_E8") (pintype "bidirectional"))
    )
    (net (code "183") (name "unconnected-(U1A-DONE_0-PadH10)") (class "Default")
      (node (ref "U1") (pin "H10") (pinfunction "DONE_0_H10") (pintype "bidirectional"))
    )
    (net (code "184") (name "unconnected-(U1A-INIT_B_0-PadK10)") (class "Default")
      (node (ref "U1") (pin "K10") (pinfunction "INIT_B_0_K10") (pintype "open_collector"))
    )
    (net (code "185") (name "unconnected-(U1A-M0_0-PadM9)") (class "Default")
      (node (ref "U1") (pin "M9") (pinfunction "M0_0_M9") (pintype "input"))
    )
    (net (code "186") (name "unconnected-(U1A-M1_0-PadM10)") (class "Default")
      (node (ref "U1") (pin "M10") (pinfunction "M1_0_M10") (pintype "input"))
    )
    (net (code "187") (name "unconnected-(U1A-M2_0-PadM11)") (class "Default")
      (node (ref "U1") (pin "M11") (pinfunction "M2_0_M11") (pintype "input"))
    )
    (net (code "188") (name "unconnected-(U1A-PROGRAM_B_0-PadL9)") (class "Default")
      (node (ref "U1") (pin "L9") (pinfunction "PROGRAM_B_0_L9") (pintype "input"))
    )
    (net (code "189") (name "unconnected-(U1A-TCK_0-PadL7)") (class "Default")
      (node (ref "U1") (pin "L7") (pinfunction "TCK_0_L7") (pintype "input"))
    )
    (net (code "190") (name "unconnected-(U1A-TDI_0-PadN7)") (class "Default")
      (node (ref "U1") (pin "N7") (pinfunction "TDI_0_N7") (pintype "input"))
    )
    (net (code "191") (name "unconnected-(U1A-TDO_0-PadN8)") (class "Default")
      (node (ref "U1") (pin "N8") (pinfunction "TDO_0_N8") (pintype "output"))
    )
    (net (code "192") (name "unconnected-(U1A-TMS_0-PadM7)") (class "Default")
      (node (ref "U1") (pin "M7") (pinfunction "TMS_0_M7") (pintype "input"))
    )
    (net (code "193") (name "unconnected-(U1B-IO_0_14-PadK12)") (class "Default")
      (node (ref "U1") (pin "K12") (pinfunction "IO_0_14_K12") (pintype "bidirectional"))
    )
    (net (code "194") (name "unconnected-(U1B-IO_25_14-PadP6)") (class "Default")
      (node (ref "U1") (pin "P6") (pinfunction "IO_25_14_P6") (pintype "bidirectional"))
    )
    (net (code "195") (name "unconnected-(U1B-IO_L1N_T0_D01_DIN_14-PadJ14)") (class "Default")
      (node (ref "U1") (pin "J14") (pinfunction "IO_L1N_T0_D01_DIN_14_J14") (pintype "bidirectional"))
    )
    (net (code "196") (name "unconnected-(U1B-IO_L1P_T0_D00_MOSI_14-PadJ13)") (class "Default")
      (node (ref "U1") (pin "J13") (pinfunction "IO_L1P_T0_D00_MOSI_14_J13") (pintype "bidirectional"))
    )
    (net (code "197") (name "unconnected-(U1B-IO_L2N_T0_D03_14-PadK16)") (class "Default")
      (node (ref "U1") (pin "K16") (pinfunction "IO_L2N_T0_D03_14_K16") (pintype "bidirectional"))
    )
    (net (code "198") (name "unconnected-(U1B-IO_L2P_T0_D02_14-PadK15)") (class "Default")
      (node (ref "U1") (pin "K15") (pinfunction "IO_L2P_T0_D02_14_K15") (pintype "bidirectional"))
    )
    (net (code "199") (name "unconnected-(U1B-IO_L3N_T0_DQS_EMCCLK_14-PadM15)") (class "Default")
      (node (ref "U1") (pin "M15") (pinfunction "IO_L3N_T0_DQS_EMCCLK_14_M15") (pintype "bidirectional"))
    )
    (net (code "200") (name "unconnected-(U1B-IO_L3P_T0_DQS_PUDC_B_14-PadL15)") (class "Default")
      (node (ref "U1") (pin "L15") (pinfunction "IO_L3P_T0_DQS_PUDC_B_14_L15") (pintype "bidirectional"))
    )
    (net (code "201") (name "unconnected-(U1B-IO_L4N_T0_D05_14-PadM14)") (class "Default")
      (node (ref "U1") (pin "M14") (pinfunction "IO_L4N_T0_D05_14_M14") (pintype "bidirectional"))
    )
    (net (code "202") (name "unconnected-(U1B-IO_L4P_T0_D04_14-PadL14)") (class "Default")
      (node (ref "U1") (pin "L14") (pinfunction "IO_L4P_T0_D04_14_L14") (pintype "bidirectional"))
    )
    (net (code "203") (name "unconnected-(U1B-IO_L5N_T0_D07_14-PadL13)") (class "Default")
      (node (ref "U1") (pin "L13") (pinfunction "IO_L5N_T0_D07_14_L13") (pintype "bidirectional"))
    )
    (net (code "204") (name "unconnected-(U1B-IO_L5P_T0_D06_14-PadK13)") (class "Default")
      (node (ref "U1") (pin "K13") (pinfunction "IO_L5P_T0_D06_14_K13") (pintype "bidirectional"))
    )
    (net (code "205") (name "unconnected-(U1B-IO_L6N_T0_D08_VREF_14-PadM12)") (class "Default")
      (node (ref "U1") (pin "M12") (pinfunction "IO_L6N_T0_D08_VREF_14_M12") (pintype "bidirectional"))
    )
    (net (code "206") (name "unconnected-(U1B-IO_L6P_T0_FCS_B_14-PadL12)") (class "Default")
      (node (ref "U1") (pin "L12") (pinfunction "IO_L6P_T0_FCS_B_14_L12") (pintype "bidirectional"))
    )
    (net (code "207") (name "unconnected-(U1B-IO_L7N_T1_D10_14-PadN16)") (class "Default")
      (node (ref "U1") (pin "N16") (pinfunction "IO_L7N_T1_D10_14_N16") (pintype "bidirectional"))
    )
    (net (code "208") (name "unconnected-(U1B-IO_L7P_T1_D09_14-PadM16)") (class "Default")
      (node (ref "U1") (pin "M16") (pinfunction "IO_L7P_T1_D09_14_M16") (pintype "bidirectional"))
    )
    (net (code "209") (name "unconnected-(U1B-IO_L8N_T1_D12_14-PadP16)") (class "Default")
      (node (ref "U1") (pin "P16") (pinfunction "IO_L8N_T1_D12_14_P16") (pintype "bidirectional"))
    )
    (net (code "210") (name "unconnected-(U1B-IO_L8P_T1_D11_14-PadP15)") (class "Default")
      (node (ref "U1") (pin "P15") (pinfunction "IO_L8P_T1_D11_14_P15") (pintype "bidirectional"))
    )
    (net (code "211") (name "unconnected-(U1B-IO_L9N_T1_DQS_D13_14-PadR16)") (class "Default")
      (node (ref "U1") (pin "R16") (pinfunction "IO_L9N_T1_DQS_D13_14_R16") (pintype "bidirectional"))
    )
    (net (code "212") (name "unconnected-(U1B-IO_L9P_T1_DQS_14-PadR15)") (class "Default")
      (node (ref "U1") (pin "R15") (pinfunction "IO_L9P_T1_DQS_14_R15") (pintype "bidirectional"))
    )
    (net (code "213") (name "unconnected-(U1B-IO_L10N_T1_D15_14-PadT15)") (class "Default")
      (node (ref "U1") (pin "T15") (pinfunction "IO_L10N_T1_D15_14_T15") (pintype "bidirectional"))
    )
    (net (code "214") (name "unconnected-(U1B-IO_L10P_T1_D14_14-PadT14)") (class "Default")
      (node (ref "U1") (pin "T14") (pinfunction "IO_L10P_T1_D14_14_T14") (pintype "bidirectional"))
    )
    (net (code "215") (name "unconnected-(U1B-IO_L11N_T1_SRCC_14-PadP13)") (class "Default")
      (node (ref "U1") (pin "P13") (pinfunction "IO_L11N_T1_SRCC_14_P13") (pintype "bidirectional"))
    )
    (net (code "216") (name "unconnected-(U1B-IO_L11P_T1_SRCC_14-PadN13)") (class "Default")
      (node (ref "U1") (pin "N13") (pinfunction "IO_L11P_T1_SRCC_14_N13") (pintype "bidirectional"))
    )
    (net (code "217") (name "unconnected-(U1B-IO_L12N_T1_MRCC_14-PadP14)") (class "Default")
      (node (ref "U1") (pin "P14") (pinfunction "IO_L12N_T1_MRCC_14_P14") (pintype "bidirectional"))
    )
    (net (code "218") (name "unconnected-(U1B-IO_L12P_T1_MRCC_14-PadN14)") (class "Default")
      (node (ref "U1") (pin "N14") (pinfunction "IO_L12P_T1_MRCC_14_N14") (pintype "bidirectional"))
    )
    (net (code "219") (name "unconnected-(U1B-IO_L13N_T2_MRCC_14-PadN12)") (class "Default")
      (node (ref "U1") (pin "N12") (pinfunction "IO_L13N_T2_MRCC_14_N12") (pintype "bidirectional"))
    )
    (net (code "220") (name "unconnected-(U1B-IO_L13P_T2_MRCC_14-PadN11)") (class "Default")
      (node (ref "U1") (pin "N11") (pinfunction "IO_L13P_T2_MRCC_14_N11") (pintype "bidirectional"))
    )
    (net (code "221") (name "unconnected-(U1B-IO_L14N_T2_SRCC_14-PadP11)") (class "Default")
      (node (ref "U1") (pin "P11") (pinfunction "IO_L14N_T2_SRCC_14_P11") (pintype "bidirectional"))
    )
    (net (code "222") (name "unconnected-(U1B-IO_L14P_T2_SRCC_14-PadP10)") (class "Default")
      (node (ref "U1") (pin "P10") (pinfunction "IO_L14P_T2_SRCC_14_P10") (pintype "bidirectional"))
    )
    (net (code "223") (name "unconnected-(U1B-IO_L15N_T2_DQS_DOUT_CSO_B_14-PadT12)") (class "Default")
      (node (ref "U1") (pin "T12") (pinfunction "IO_L15N_T2_DQS_DOUT_CSO_B_14_T12") (pintype "bidirectional"))
    )
    (net (code "224") (name "unconnected-(U1B-IO_L15P_T2_DQS_RDWR_B_14-PadR12)") (class "Default")
      (node (ref "U1") (pin "R12") (pinfunction "IO_L15P_T2_DQS_RDWR_B_14_R12") (pintype "bidirectional"))
    )
    (net (code "225") (name "unconnected-(U1B-IO_L16N_T2_A15_D31_14-PadT13)") (class "Default")
      (node (ref "U1") (pin "T13") (pinfunction "IO_L16N_T2_A15_D31_14_T13") (pintype "bidirectional"))
    )
    (net (code "226") (name "unconnected-(U1B-IO_L16P_T2_CSI_B_14-PadR13)") (class "Default")
      (node (ref "U1") (pin "R13") (pinfunction "IO_L16P_T2_CSI_B_14_R13") (pintype "bidirectional"))
    )
    (net (code "227") (name "unconnected-(U1B-IO_L17N_T2_A13_D29_14-PadR11)") (class "Default")
      (node (ref "U1") (pin "R11") (pinfunction "IO_L17N_T2_A13_D29_14_R11") (pintype "bidirectional"))
    )
    (net (code "228") (name "unconnected-(U1B-IO_L17P_T2_A14_D30_14-PadR10)") (class "Default")
      (node (ref "U1") (pin "R10") (pinfunction "IO_L17P_T2_A14_D30_14_R10") (pintype "bidirectional"))
    )
    (net (code "229") (name "unconnected-(U1B-IO_L18N_T2_A11_D27_14-PadP9)") (class "Default")
      (node (ref "U1") (pin "P9") (pinfunction "IO_L18N_T2_A11_D27_14_P9") (pintype "bidirectional"))
    )
    (net (code "230") (name "unconnected-(U1B-IO_L18P_T2_A12_D28_14-PadN9)") (class "Default")
      (node (ref "U1") (pin "N9") (pinfunction "IO_L18P_T2_A12_D28_14_N9") (pintype "bidirectional"))
    )
    (net (code "231") (name "unconnected-(U1B-IO_L19N_T3_A09_D25_VREF_14-PadN6)") (class "Default")
      (node (ref "U1") (pin "N6") (pinfunction "IO_L19N_T3_A09_D25_VREF_14_N6") (pintype "bidirectional"))
    )
    (net (code "232") (name "unconnected-(U1B-IO_L19P_T3_A10_D26_14-PadM6)") (class "Default")
      (node (ref "U1") (pin "M6") (pinfunction "IO_L19P_T3_A10_D26_14_M6") (pintype "bidirectional"))
    )
    (net (code "233") (name "unconnected-(U1B-IO_L20N_T3_A07_D23_14-PadR8)") (class "Default")
      (node (ref "U1") (pin "R8") (pinfunction "IO_L20N_T3_A07_D23_14_R8") (pintype "bidirectional"))
    )
    (net (code "234") (name "unconnected-(U1B-IO_L20P_T3_A08_D24_14-PadP8)") (class "Default")
      (node (ref "U1") (pin "P8") (pinfunction "IO_L20P_T3_A08_D24_14_P8") (pintype "bidirectional"))
    )
    (net (code "235") (name "unconnected-(U1B-IO_L21N_T3_DQS_A06_D22_14-PadT8)") (class "Default")
      (node (ref "U1") (pin "T8") (pinfunction "IO_L21N_T3_DQS_A06_D22_14_T8") (pintype "bidirectional"))
    )
    (net (code "236") (name "unconnected-(U1B-IO_L21P_T3_DQS_14-PadT7)") (class "Default")
      (node (ref "U1") (pin "T7") (pinfunction "IO_L21P_T3_DQS_14_T7") (pintype "bidirectional"))
    )
    (net (code "237") (name "unconnected-(U1B-IO_L22N_T3_A04_D20_14-PadT10)") (class "Default")
      (node (ref "U1") (pin "T10") (pinfunction "IO_L22N_T3_A04_D20_14_T10") (pintype "bidirectional"))
    )
    (net (code "238") (name "unconnected-(U1B-IO_L22P_T3_A05_D21_14-PadT9)") (class "Default")
      (node (ref "U1") (pin "T9") (pinfunction "IO_L22P_T3_A05_D21_14_T9") (pintype "bidirectional"))
    )
    (net (code "239") (name "unconnected-(U1B-IO_L23N_T3_A02_D18_14-PadT5)") (class "Default")
      (node (ref "U1") (pin "T5") (pinfunction "IO_L23N_T3_A02_D18_14_T5") (pintype "bidirectional"))
    )
    (net (code "240") (name "unconnected-(U1B-IO_L23P_T3_A03_D19_14-PadR5)") (class "Default")
      (node (ref "U1") (pin "R5") (pinfunction "IO_L23P_T3_A03_D19_14_R5") (pintype "bidirectional"))
    )
    (net (code "241") (name "unconnected-(U1B-IO_L24N_T3_A00_D16_14-PadR7)") (class "Default")
      (node (ref "U1") (pin "R7") (pinfunction "IO_L24N_T3_A00_D16_14_R7") (pintype "bidirectional"))
    )
    (net (code "242") (name "unconnected-(U1B-IO_L24P_T3_A01_D17_14-PadR6)") (class "Default")
      (node (ref "U1") (pin "R6") (pinfunction "IO_L24P_T3_A01_D17_14_R6") (pintype "bidirectional"))
    )
    (net (code "243") (name "unconnected-(U1C-IO_0_15-PadD10)") (class "Default")
      (node (ref "U1") (pin "D10") (pinfunction "IO_0_15_D10") (pintype "bidirectional"))
    )
    (net (code "244") (name "unconnected-(U1C-IO_25_15-PadG11)") (class "Default")
      (node (ref "U1") (pin "G11") (pinfunction "IO_25_15_G11") (pintype "bidirectional"))
    )
    (net (code "245") (name "unconnected-(U1C-IO_L1N_T0_AD0N_15-PadC9)") (class "Default")
      (node (ref "U1") (pin "C9") (pinfunction "IO_L1N_T0_AD0N_15_C9") (pintype "bidirectional"))
    )
    (net (code "246") (name "unconnected-(U1C-IO_L1P_T0_AD0P_15-PadC8)") (class "Default")
      (node (ref "U1") (pin "C8") (pinfunction "IO_L1P_T0_AD0P_15_C8") (pintype "bidirectional"))
    )
    (net (code "247") (name "unconnected-(U1C-IO_L2N_T0_AD8N_15-PadA9)") (class "Default")
      (node (ref "U1") (pin "A9") (pinfunction "IO_L2N_T0_AD8N_15_A9") (pintype "bidirectional"))
    )
    (net (code "248") (name "unconnected-(U1C-IO_L2P_T0_AD8P_15-PadA8)") (class "Default")
      (node (ref "U1") (pin "A8") (pinfunction "IO_L2P_T0_AD8P_15_A8") (pintype "bidirectional"))
    )
    (net (code "249") (name "unconnected-(U1C-IO_L3N_T0_DQS_AD1N_15-PadA10)") (class "Default")
      (node (ref "U1") (pin "A10") (pinfunction "IO_L3N_T0_DQS_AD1N_15_A10") (pintype "bidirectional"))
    )
    (net (code "250") (name "unconnected-(U1C-IO_L3P_T0_DQS_AD1P_15-PadB9)") (class "Default")
      (node (ref "U1") (pin "B9") (pinfunction "IO_L3P_T0_DQS_AD1P_15_B9") (pintype "bidirectional"))
    )
    (net (code "251") (name "unconnected-(U1C-IO_L4N_T0_15-PadB11)") (class "Default")
      (node (ref "U1") (pin "B11") (pinfunction "IO_L4N_T0_15_B11") (pintype "bidirectional"))
    )
    (net (code "252") (name "unconnected-(U1C-IO_L4P_T0_15-PadB10)") (class "Default")
      (node (ref "U1") (pin "B10") (pinfunction "IO_L4P_T0_15_B10") (pintype "bidirectional"))
    )
    (net (code "253") (name "unconnected-(U1C-IO_L5N_T0_AD9N_15-PadA12)") (class "Default")
      (node (ref "U1") (pin "A12") (pinfunction "IO_L5N_T0_AD9N_15_A12") (pintype "bidirectional"))
    )
    (net (code "254") (name "unconnected-(U1C-IO_L5P_T0_AD9P_15-PadB12)") (class "Default")
      (node (ref "U1") (pin "B12") (pinfunction "IO_L5P_T0_AD9P_15_B12") (pintype "bidirectional"))
    )
    (net (code "255") (name "unconnected-(U1C-IO_L6N_T0_VREF_15-PadD9)") (class "Default")
      (node (ref "U1") (pin "D9") (pinfunction "IO_L6N_T0_VREF_15_D9") (pintype "bidirectional"))
    )
    (net (code "256") (name "unconnected-(U1C-IO_L6P_T0_15-PadD8)") (class "Default")
      (node (ref "U1") (pin "D8") (pinfunction "IO_L6P_T0_15_D8") (pintype "bidirectional"))
    )
    (net (code "257") (name "unconnected-(U1C-IO_L7N_T1_AD2N_15-PadA14)") (class "Default")
      (node (ref "U1") (pin "A14") (pinfunction "IO_L7N_T1_AD2N_15_A14") (pintype "bidirectional"))
    )
    (net (code "258") (name "unconnected-(U1C-IO_L7P_T1_AD2P_15-PadA13)") (class "Default")
      (node (ref "U1") (pin "A13") (pinfunction "IO_L7P_T1_AD2P_15_A13") (pintype "bidirectional"))
    )
    (net (code "259") (name "unconnected-(U1C-IO_L8N_T1_AD10N_15-PadB14)") (class "Default")
      (node (ref "U1") (pin "B14") (pinfunction "IO_L8N_T1_AD10N_15_B14") (pintype "bidirectional"))
    )
    (net (code "260") (name "unconnected-(U1C-IO_L8P_T1_AD10P_15-PadC14)") (class "Default")
      (node (ref "U1") (pin "C14") (pinfunction "IO_L8P_T1_AD10P_15_C14") (pintype "bidirectional"))
    )
    (net (code "261") (name "unconnected-(U1C-IO_L9N_T1_DQS_AD3N_15-PadA15)") (class "Default")
      (node (ref "U1") (pin "A15") (pinfunction "IO_L9N_T1_DQS_AD3N_15_A15") (pintype "bidirectional"))
    )
    (net (code "262") (name "unconnected-(U1C-IO_L9P_T1_DQS_AD3P_15-PadB15)") (class "Default")
      (node (ref "U1") (pin "B15") (pinfunction "IO_L9P_T1_DQS_AD3P_15_B15") (pintype "bidirectional"))
    )
    (net (code "263") (name "unconnected-(U1C-IO_L10N_T1_AD11N_15-PadB16)") (class "Default")
      (node (ref "U1") (pin "B16") (pinfunction "IO_L10N_T1_AD11N_15_B16") (pintype "bidirectional"))
    )
    (net (code "264") (name "unconnected-(U1C-IO_L10P_T1_AD11P_15-PadC16)") (class "Default")
      (node (ref "U1") (pin "C16") (pinfunction "IO_L10P_T1_AD11P_15_C16") (pintype "bidirectional"))
    )
    (net (code "265") (name "unconnected-(U1C-IO_L11N_T1_SRCC_15-PadC12)") (class "Default")
      (node (ref "U1") (pin "C12") (pinfunction "IO_L11N_T1_SRCC_15_C12") (pintype "bidirectional"))
    )
    (net (code "266") (name "unconnected-(U1C-IO_L11P_T1_SRCC_15-PadC11)") (class "Default")
      (node (ref "U1") (pin "C11") (pinfunction "IO_L11P_T1_SRCC_15_C11") (pintype "bidirectional"))
    )
    (net (code "267") (name "unconnected-(U1C-IO_L12N_T1_MRCC_15-PadC13)") (class "Default")
      (node (ref "U1") (pin "C13") (pinfunction "IO_L12N_T1_MRCC_15_C13") (pintype "bidirectional"))
    )
    (net (code "268") (name "unconnected-(U1C-IO_L12P_T1_MRCC_15-PadD13)") (class "Default")
      (node (ref "U1") (pin "D13") (pinfunction "IO_L12P_T1_MRCC_15_D13") (pintype "bidirectional"))
    )
    (net (code "269") (name "unconnected-(U1C-IO_L13N_T2_MRCC_15-PadE13)") (class "Default")
      (node (ref "U1") (pin "E13") (pinfunction "IO_L13N_T2_MRCC_15_E13") (pintype "bidirectional"))
    )
    (net (code "270") (name "unconnected-(U1C-IO_L13P_T2_MRCC_15-PadE12)") (class "Default")
      (node (ref "U1") (pin "E12") (pinfunction "IO_L13P_T2_MRCC_15_E12") (pintype "bidirectional"))
    )
    (net (code "271") (name "unconnected-(U1C-IO_L14N_T2_SRCC_15-PadD11)") (class "Default")
      (node (ref "U1") (pin "D11") (pinfunction "IO_L14N_T2_SRCC_15_D11") (pintype "bidirectional"))
    )
    (net (code "272") (name "unconnected-(U1C-IO_L14P_T2_SRCC_15-PadE11)") (class "Default")
      (node (ref "U1") (pin "E11") (pinfunction "IO_L14P_T2_SRCC_15_E11") (pintype "bidirectional"))
    )
    (net (code "273") (name "unconnected-(U1C-IO_L15N_T2_DQS_ADV_B_15-PadD15)") (class "Default")
      (node (ref "U1") (pin "D15") (pinfunction "IO_L15N_T2_DQS_ADV_B_15_D15") (pintype "bidirectional"))
    )
    (net (code "274") (name "unconnected-(U1C-IO_L15P_T2_DQS_15-PadD14)") (class "Default")
      (node (ref "U1") (pin "D14") (pinfunction "IO_L15P_T2_DQS_15_D14") (pintype "bidirectional"))
    )
    (net (code "275") (name "unconnected-(U1C-IO_L16N_T2_A27_15-PadF13)") (class "Default")
      (node (ref "U1") (pin "F13") (pinfunction "IO_L16N_T2_A27_15_F13") (pintype "bidirectional"))
    )
    (net (code "276") (name "unconnected-(U1C-IO_L16P_T2_A28_15-PadF12)") (class "Default")
      (node (ref "U1") (pin "F12") (pinfunction "IO_L16P_T2_A28_15_F12") (pintype "bidirectional"))
    )
    (net (code "277") (name "unconnected-(U1C-IO_L17N_T2_A25_15-PadD16)") (class "Default")
      (node (ref "U1") (pin "D16") (pinfunction "IO_L17N_T2_A25_15_D16") (pintype "bidirectional"))
    )
    (net (code "278") (name "unconnected-(U1C-IO_L17P_T2_A26_15-PadE16)") (class "Default")
      (node (ref "U1") (pin "E16") (pinfunction "IO_L17P_T2_A26_15_E16") (pintype "bidirectional"))
    )
    (net (code "279") (name "unconnected-(U1C-IO_L18N_T2_A23_15-PadE15)") (class "Default")
      (node (ref "U1") (pin "E15") (pinfunction "IO_L18N_T2_A23_15_E15") (pintype "bidirectional"))
    )
    (net (code "280") (name "unconnected-(U1C-IO_L18P_T2_A24_15-PadF15)") (class "Default")
      (node (ref "U1") (pin "F15") (pinfunction "IO_L18P_T2_A24_15_F15") (pintype "bidirectional"))
    )
    (net (code "281") (name "unconnected-(U1C-IO_L19N_T3_A21_VREF_15-PadG12)") (class "Default")
      (node (ref "U1") (pin "G12") (pinfunction "IO_L19N_T3_A21_VREF_15_G12") (pintype "bidirectional"))
    )
    (net (code "282") (name "unconnected-(U1C-IO_L19P_T3_A22_15-PadH11)") (class "Default")
      (node (ref "U1") (pin "H11") (pinfunction "IO_L19P_T3_A22_15_H11") (pintype "bidirectional"))
    )
    (net (code "283") (name "unconnected-(U1C-IO_L20N_T3_A19_15-PadH13)") (class "Default")
      (node (ref "U1") (pin "H13") (pinfunction "IO_L20N_T3_A19_15_H13") (pintype "bidirectional"))
    )
    (net (code "284") (name "unconnected-(U1C-IO_L20P_T3_A20_15-PadH12)") (class "Default")
      (node (ref "U1") (pin "H12") (pinfunction "IO_L20P_T3_A20_15_H12") (pintype "bidirectional"))
    )
    (net (code "285") (name "unconnected-(U1C-IO_L21N_T3_DQS_A18_15-PadF14)") (class "Default")
      (node (ref "U1") (pin "F14") (pinfunction "IO_L21N_T3_DQS_A18_15_F14") (pintype "bidirectional"))
    )
    (net (code "286") (name "unconnected-(U1C-IO_L21P_T3_DQS_15-PadG14)") (class "Default")
      (node (ref "U1") (pin "G14") (pinfunction "IO_L21P_T3_DQS_15_G14") (pintype "bidirectional"))
    )
    (net (code "287") (name "unconnected-(U1C-IO_L22N_T3_A16_15-PadG16)") (class "Default")
      (node (ref "U1") (pin "G16") (pinfunction "IO_L22N_T3_A16_15_G16") (pintype "bidirectional"))
    )
    (net (code "288") (name "unconnected-(U1C-IO_L22P_T3_A17_15-PadH16)") (class "Default")
      (node (ref "U1") (pin "H16") (pinfunction "IO_L22P_T3_A17_15_H16") (pintype "bidirectional"))
    )
    (net (code "289") (name "unconnected-(U1C-IO_L23N_T3_FWE_B_15-PadJ16)") (class "Default")
      (node (ref "U1") (pin "J16") (pinfunction "IO_L23N_T3_FWE_B_15_J16") (pintype "bidirectional"))
    )
    (net (code "290") (name "unconnected-(U1C-IO_L23P_T3_FOE_B_15-PadJ15)") (class "Default")
      (node (ref "U1") (pin "J15") (pinfunction "IO_L23P_T3_FOE_B_15_J15") (pintype "bidirectional"))
    )
    (net (code "291") (name "unconnected-(U1C-IO_L24N_T3_RS0_15-PadG15)") (class "Default")
      (node (ref "U1") (pin "G15") (pinfunction "IO_L24N_T3_RS0_15_G15") (pintype "bidirectional"))
    )
    (net (code "292") (name "unconnected-(U1C-IO_L24P_T3_RS1_15-PadH14)") (class "Default")
      (node (ref "U1") (pin "H14") (pinfunction "IO_L24P_T3_RS1_15_H14") (pintype "bidirectional"))
    )
    (net (code "293") (name "unconnected-(U1D-IO_0_34-PadL5)") (class "Default")
      (node (ref "U1") (pin "L5") (pinfunction "IO_0_34_L5") (pintype "bidirectional"))
    )
    (net (code "294") (name "unconnected-(U1D-IO_L1N_T0_34-PadM4)") (class "Default")
      (node (ref "U1") (pin "M4") (pinfunction "IO_L1N_T0_34_M4") (pintype "bidirectional"))
    )
    (net (code "295") (name "unconnected-(U1D-IO_L1P_T0_34-PadL4)") (class "Default")
      (node (ref "U1") (pin "L4") (pinfunction "IO_L1P_T0_34_L4") (pintype "bidirectional"))
    )
    (net (code "296") (name "unconnected-(U1D-IO_L2N_T0_34-PadM1)") (class "Default")
      (node (ref "U1") (pin "M1") (pinfunction "IO_L2N_T0_34_M1") (pintype "bidirectional"))
    )
    (net (code "297") (name "unconnected-(U1D-IO_L2P_T0_34-PadM2)") (class "Default")
      (node (ref "U1") (pin "M2") (pinfunction "IO_L2P_T0_34_M2") (pintype "bidirectional"))
    )
    (net (code "298") (name "unconnected-(U1D-IO_L3N_T0_DQS_34-PadN2)") (class "Default")
      (node (ref "U1") (pin "N2") (pinfunction "IO_L3N_T0_DQS_34_N2") (pintype "bidirectional"))
    )
    (net (code "299") (name "unconnected-(U1D-IO_L3P_T0_DQS_34-PadN3)") (class "Default")
      (node (ref "U1") (pin "N3") (pinfunction "IO_L3P_T0_DQS_34_N3") (pintype "bidirectional"))
    )
    (net (code "300") (name "unconnected-(U1D-IO_L4N_T0_34-PadP1)") (class "Default")
      (node (ref "U1") (pin "P1") (pinfunction "IO_L4N_T0_34_P1") (pintype "bidirectional"))
    )
    (net (code "301") (name "unconnected-(U1D-IO_L4P_T0_34-PadN1)") (class "Default")
      (node (ref "U1") (pin "N1") (pinfunction "IO_L4P_T0_34_N1") (pintype "bidirectional"))
    )
    (net (code "302") (name "unconnected-(U1D-IO_L5N_T0_34-PadP3)") (class "Default")
      (node (ref "U1") (pin "P3") (pinfunction "IO_L5N_T0_34_P3") (pintype "bidirectional"))
    )
    (net (code "303") (name "unconnected-(U1D-IO_L5P_T0_34-PadP4)") (class "Default")
      (node (ref "U1") (pin "P4") (pinfunction "IO_L5P_T0_34_P4") (pintype "bidirectional"))
    )
    (net (code "304") (name "unconnected-(U1D-IO_L6N_T0_VREF_34-PadN4)") (class "Default")
      (node (ref "U1") (pin "N4") (pinfunction "IO_L6N_T0_VREF_34_N4") (pintype "bidirectional"))
    )
    (net (code "305") (name "unconnected-(U1D-IO_L6P_T0_34-PadM5)") (class "Default")
      (node (ref "U1") (pin "M5") (pinfunction "IO_L6P_T0_34_M5") (pintype "bidirectional"))
    )
    (net (code "306") (name "unconnected-(U1D-IO_L7N_T1_34-PadR1)") (class "Default")
      (node (ref "U1") (pin "R1") (pinfunction "IO_L7N_T1_34_R1") (pintype "bidirectional"))
    )
    (net (code "307") (name "unconnected-(U1D-IO_L7P_T1_34-PadR2)") (class "Default")
      (node (ref "U1") (pin "R2") (pinfunction "IO_L7P_T1_34_R2") (pintype "bidirectional"))
    )
    (net (code "308") (name "unconnected-(U1D-IO_L8N_T1_34-PadT2)") (class "Default")
      (node (ref "U1") (pin "T2") (pinfunction "IO_L8N_T1_34_T2") (pintype "bidirectional"))
    )
    (net (code "309") (name "unconnected-(U1D-IO_L8P_T1_34-PadR3)") (class "Default")
      (node (ref "U1") (pin "R3") (pinfunction "IO_L8P_T1_34_R3") (pintype "bidirectional"))
    )
    (net (code "310") (name "unconnected-(U1D-IO_L9N_T1_DQS_34-PadT3)") (class "Default")
      (node (ref "U1") (pin "T3") (pinfunction "IO_L9N_T1_DQS_34_T3") (pintype "bidirectional"))
    )
    (net (code "311") (name "unconnected-(U1D-IO_L9P_T1_DQS_34-PadT4)") (class "Default")
      (node (ref "U1") (pin "T4") (pinfunction "IO_L9P_T1_DQS_34_T4") (pintype "bidirectional"))
    )
    (net (code "312") (name "unconnected-(U1D-IO_L10P_T1_34-PadP5)") (class "Default")
      (node (ref "U1") (pin "P5") (pinfunction "IO_L10P_T1_34_P5") (pintype "bidirectional"))
    )
    (net (code "313") (name "unconnected-(U1E-IO_0_35-PadE6)") (class "Default")
      (node (ref "U1") (pin "E6") (pinfunction "IO_0_35_E6") (pintype "bidirectional"))
    )
    (net (code "314") (name "unconnected-(U1E-IO_25_35-PadK5)") (class "Default")
      (node (ref "U1") (pin "K5") (pinfunction "IO_25_35_K5") (pintype "bidirectional"))
    )
    (net (code "315") (name "unconnected-(U1E-IO_L1N_T0_AD4N_35-PadA7)") (class "Default")
      (node (ref "U1") (pin "A7") (pinfunction "IO_L1N_T0_AD4N_35_A7") (pintype "bidirectional"))
    )
    (net (code "316") (name "unconnected-(U1E-IO_L1P_T0_AD4P_35-PadB7)") (class "Default")
      (node (ref "U1") (pin "B7") (pinfunction "IO_L1P_T0_AD4P_35_B7") (pintype "bidirectional"))
    )
    (net (code "317") (name "unconnected-(U1E-IO_L2N_T0_AD12N_35-PadB5)") (class "Default")
      (node (ref "U1") (pin "B5") (pinfunction "IO_L2N_T0_AD12N_35_B5") (pintype "bidirectional"))
    )
    (net (code "318") (name "unconnected-(U1E-IO_L2P_T0_AD12P_35-PadB6)") (class "Default")
      (node (ref "U1") (pin "B6") (pinfunction "IO_L2P_T0_AD12P_35_B6") (pintype "bidirectional"))
    )
    (net (code "319") (name "unconnected-(U1E-IO_L3N_T0_DQS_AD5N_35-PadA4)") (class "Default")
      (node (ref "U1") (pin "A4") (pinfunction "IO_L3N_T0_DQS_AD5N_35_A4") (pintype "bidirectional"))
    )
    (net (code "320") (name "unconnected-(U1E-IO_L3P_T0_DQS_AD5P_35-PadA5)") (class "Default")
      (node (ref "U1") (pin "A5") (pinfunction "IO_L3P_T0_DQS_AD5P_35_A5") (pintype "bidirectional"))
    )
    (net (code "321") (name "unconnected-(U1E-IO_L4N_T0_35-PadA3)") (class "Default")
      (node (ref "U1") (pin "A3") (pinfunction "IO_L4N_T0_35_A3") (pintype "bidirectional"))
    )
    (net (code "322") (name "unconnected-(U1E-IO_L4P_T0_35-PadB4)") (class "Default")
      (node (ref "U1") (pin "B4") (pinfunction "IO_L4P_T0_35_B4") (pintype "bidirectional"))
    )
    (net (code "323") (name "unconnected-(U1E-IO_L5N_T0_AD13N_35-PadC6)") (class "Default")
      (node (ref "U1") (pin "C6") (pinfunction "IO_L5N_T0_AD13N_35_C6") (pintype "bidirectional"))
    )
    (net (code "324") (name "unconnected-(U1E-IO_L5P_T0_AD13P_35-PadC7)") (class "Default")
      (node (ref "U1") (pin "C7") (pinfunction "IO_L5P_T0_AD13P_35_C7") (pintype "bidirectional"))
    )
    (net (code "325") (name "unconnected-(U1E-IO_L6N_T0_VREF_35-PadD5)") (class "Default")
      (node (ref "U1") (pin "D5") (pinfunction "IO_L6N_T0_VREF_35_D5") (pintype "bidirectional"))
    )
    (net (code "326") (name "unconnected-(U1E-IO_L6P_T0_35-PadD6)") (class "Default")
      (node (ref "U1") (pin "D6") (pinfunction "IO_L6P_T0_35_D6") (pintype "bidirectional"))
    )
    (net (code "327") (name "unconnected-(U1E-IO_L7N_T1_AD6N_35-PadC2)") (class "Default")
      (node (ref "U1") (pin "C2") (pinfunction "IO_L7N_T1_AD6N_35_C2") (pintype "bidirectional"))
    )
    (net (code "328") (name "unconnected-(U1E-IO_L7P_T1_AD6P_35-PadC3)") (class "Default")
      (node (ref "U1") (pin "C3") (pinfunction "IO_L7P_T1_AD6P_35_C3") (pintype "bidirectional"))
    )
    (net (code "329") (name "unconnected-(U1E-IO_L8N_T1_AD14N_35-PadA2)") (class "Default")
      (node (ref "U1") (pin "A2") (pinfunction "IO_L8N_T1_AD14N_35_A2") (pintype "bidirectional"))
    )
    (net (code "330") (name "unconnected-(U1E-IO_L8P_T1_AD14P_35-PadB2)") (class "Default")
      (node (ref "U1") (pin "B2") (pinfunction "IO_L8P_T1_AD14P_35_B2") (pintype "bidirectional"))
    )
    (net (code "331") (name "unconnected-(U1E-IO_L9N_T1_DQS_AD7N_35-PadB1)") (class "Default")
      (node (ref "U1") (pin "B1") (pinfunction "IO_L9N_T1_DQS_AD7N_35_B1") (pintype "bidirectional"))
    )
    (net (code "332") (name "unconnected-(U1E-IO_L9P_T1_DQS_AD7P_35-PadC1)") (class "Default")
      (node (ref "U1") (pin "C1") (pinfunction "IO_L9P_T1_DQS_AD7P_35_C1") (pintype "bidirectional"))
    )
    (net (code "333") (name "unconnected-(U1E-IO_L10N_T1_AD15N_35-PadD1)") (class "Default")
      (node (ref "U1") (pin "D1") (pinfunction "IO_L10N_T1_AD15N_35_D1") (pintype "bidirectional"))
    )
    (net (code "334") (name "unconnected-(U1E-IO_L10P_T1_AD15P_35-PadE2)") (class "Default")
      (node (ref "U1") (pin "E2") (pinfunction "IO_L10P_T1_AD15P_35_E2") (pintype "bidirectional"))
    )
    (net (code "335") (name "unconnected-(U1E-IO_L11N_T1_SRCC_35-PadD3)") (class "Default")
      (node (ref "U1") (pin "D3") (pinfunction "IO_L11N_T1_SRCC_35_D3") (pintype "bidirectional"))
    )
    (net (code "336") (name "unconnected-(U1E-IO_L11P_T1_SRCC_35-PadE3)") (class "Default")
      (node (ref "U1") (pin "E3") (pinfunction "IO_L11P_T1_SRCC_35_E3") (pintype "bidirectional"))
    )
    (net (code "337") (name "unconnected-(U1E-IO_L12N_T1_MRCC_35-PadC4)") (class "Default")
      (node (ref "U1") (pin "C4") (pinfunction "IO_L12N_T1_MRCC_35_C4") (pintype "bidirectional"))
    )
    (net (code "338") (name "unconnected-(U1E-IO_L12P_T1_MRCC_35-PadD4)") (class "Default")
      (node (ref "U1") (pin "D4") (pinfunction "IO_L12P_T1_MRCC_35_D4") (pintype "bidirectional"))
    )
    (net (code "339") (name "unconnected-(U1E-IO_L13N_T2_MRCC_35-PadE5)") (class "Default")
      (node (ref "U1") (pin "E5") (pinfunction "IO_L13N_T2_MRCC_35_E5") (pintype "bidirectional"))
    )
    (net (code "340") (name "unconnected-(U1E-IO_L13P_T2_MRCC_35-PadF5)") (class "Default")
      (node (ref "U1") (pin "F5") (pinfunction "IO_L13P_T2_MRCC_35_F5") (pintype "bidirectional"))
    )
    (net (code "341") (name "unconnected-(U1E-IO_L14N_T2_SRCC_35-PadF3)") (class "Default")
      (node (ref "U1") (pin "F3") (pinfunction "IO_L14N_T2_SRCC_35_F3") (pintype "bidirectional"))
    )
    (net (code "342") (name "unconnected-(U1E-IO_L14P_T2_SRCC_35-PadF4)") (class "Default")
      (node (ref "U1") (pin "F4") (pinfunction "IO_L14P_T2_SRCC_35_F4") (pintype "bidirectional"))
    )
    (net (code "343") (name "unconnected-(U1E-IO_L15N_T2_DQS_35-PadE1)") (class "Default")
      (node (ref "U1") (pin "E1") (pinfunction "IO_L15N_T2_DQS_35_E1") (pintype "bidirectional"))
    )
    (net (code "344") (name "unconnected-(U1E-IO_L15P_T2_DQS_35-PadF2)") (class "Default")
      (node (ref "U1") (pin "F2") (pinfunction "IO_L15P_T2_DQS_35_F2") (pintype "bidirectional"))
    )
    (net (code "345") (name "unconnected-(U1E-IO_L16N_T2_35-PadG4)") (class "Default")
      (node (ref "U1") (pin "G4") (pinfunction "IO_L16N_T2_35_G4") (pintype "bidirectional"))
    )
    (net (code "346") (name "unconnected-(U1E-IO_L16P_T2_35-PadG5)") (class "Default")
      (node (ref "U1") (pin "G5") (pinfunction "IO_L16P_T2_35_G5") (pintype "bidirectional"))
    )
    (net (code "347") (name "unconnected-(U1E-IO_L17N_T2_35-PadG1)") (class "Default")
      (node (ref "U1") (pin "G1") (pinfunction "IO_L17N_T2_35_G1") (pintype "bidirectional"))
    )
    (net (code "348") (name "unconnected-(U1E-IO_L17P_T2_35-PadG2)") (class "Default")
      (node (ref "U1") (pin "G2") (pinfunction "IO_L17P_T2_35_G2") (pintype "bidirectional"))
    )
    (net (code "349") (name "unconnected-(U1E-IO_L18N_T2_35-PadH4)") (class "Default")
      (node (ref "U1") (pin "H4") (pinfunction "IO_L18N_T2_35_H4") (pintype "bidirectional"))
    )
    (net (code "350") (name "unconnected-(U1E-IO_L18P_T2_35-PadH5)") (class "Default")
      (node (ref "U1") (pin "H5") (pinfunction "IO_L18P_T2_35_H5") (pintype "bidirectional"))
    )
    (net (code "351") (name "unconnected-(U1E-IO_L19N_T3_VREF_35-PadJ4)") (class "Default")
      (node (ref "U1") (pin "J4") (pinfunction "IO_L19N_T3_VREF_35_J4") (pintype "bidirectional"))
    )
    (net (code "352") (name "unconnected-(U1E-IO_L19P_T3_35-PadJ5)") (class "Default")
      (node (ref "U1") (pin "J5") (pinfunction "IO_L19P_T3_35_J5") (pintype "bidirectional"))
    )
    (net (code "353") (name "unconnected-(U1E-IO_L20N_T3_35-PadH1)") (class "Default")
      (node (ref "U1") (pin "H1") (pinfunction "IO_L20N_T3_35_H1") (pintype "bidirectional"))
    )
    (net (code "354") (name "unconnected-(U1E-IO_L20P_T3_35-PadH2)") (class "Default")
      (node (ref "U1") (pin "H2") (pinfunction "IO_L20P_T3_35_H2") (pintype "bidirectional"))
    )
    (net (code "355") (name "unconnected-(U1E-IO_L21N_T3_DQS_35-PadH3)") (class "Default")
      (node (ref "U1") (pin "H3") (pinfunction "IO_L21N_T3_DQS_35_H3") (pintype "bidirectional"))
    )
    (net (code "356") (name "unconnected-(U1E-IO_L21P_T3_DQS_35-PadJ3)") (class "Default")
      (node (ref "U1") (pin "J3") (pinfunction "IO_L21P_T3_DQS_35_J3") (pintype "bidirectional"))
    )
    (net (code "357") (name "unconnected-(U1E-IO_L22N_T3_35-PadJ1)") (class "Default")
      (node (ref "U1") (pin "J1") (pinfunction "IO_L22N_T3_35_J1") (pintype "bidirectional"))
    )
    (net (code "358") (name "unconnected-(U1E-IO_L22P_T3_35-PadK1)") (class "Default")
      (node (ref "U1") (pin "K1") (pinfunction "IO_L22P_T3_35_K1") (pintype "bidirectional"))
    )
    (net (code "359") (name "unconnected-(U1E-IO_L23N_T3_35-PadL2)") (class "Default")
      (node (ref "U1") (pin "L2") (pinfunction "IO_L23N_T3_35_L2") (pintype "bidirectional"))
    )
    (net (code "360") (name "unconnected-(U1E-IO_L23P_T3_35-PadL3)") (class "Default")
      (node (ref "U1") (pin "L3") (pinfunction "IO_L23P_T3_35_L3") (pintype "bidirectional"))
    )
    (net (code "361") (name "unconnected-(U1E-IO_L24N_T3_35-PadK2)") (class "Default")
      (node (ref "U1") (pin "K2") (pinfunction "IO_L24N_T3_35_K2") (pintype "bidirectional"))
    )
    (net (code "362") (name "unconnected-(U1E-IO_L24P_T3_35-PadK3)") (class "Default")
      (node (ref "U1") (pin "K3") (pinfunction "IO_L24P_T3_35_K3") (pintype "bidirectional"))
    )
  )
)
